# rt1060.net
KiCad netlist of a schematic drawn in EAGLE
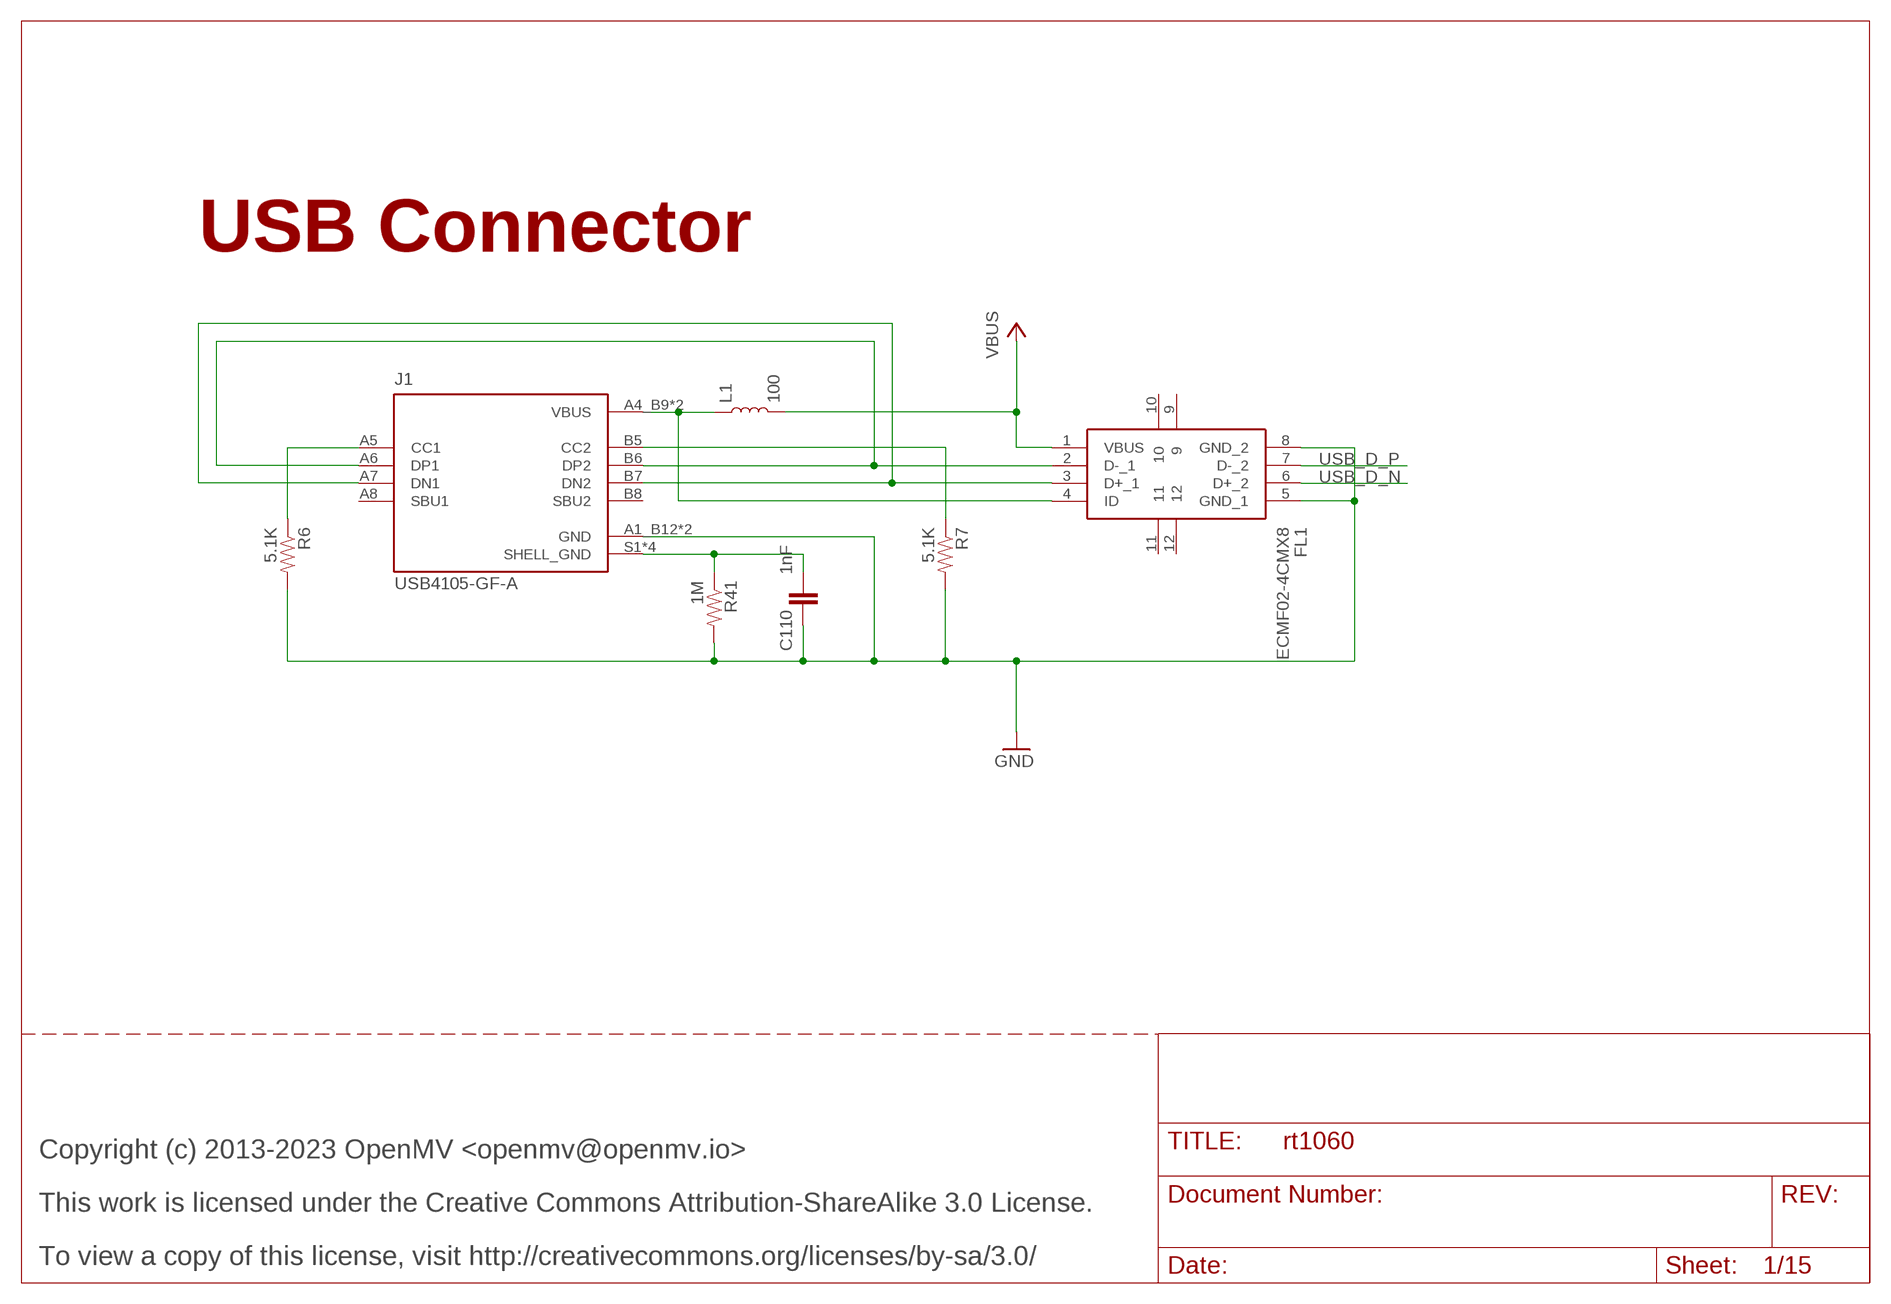
[diagram p0: schematic, sheet 1]
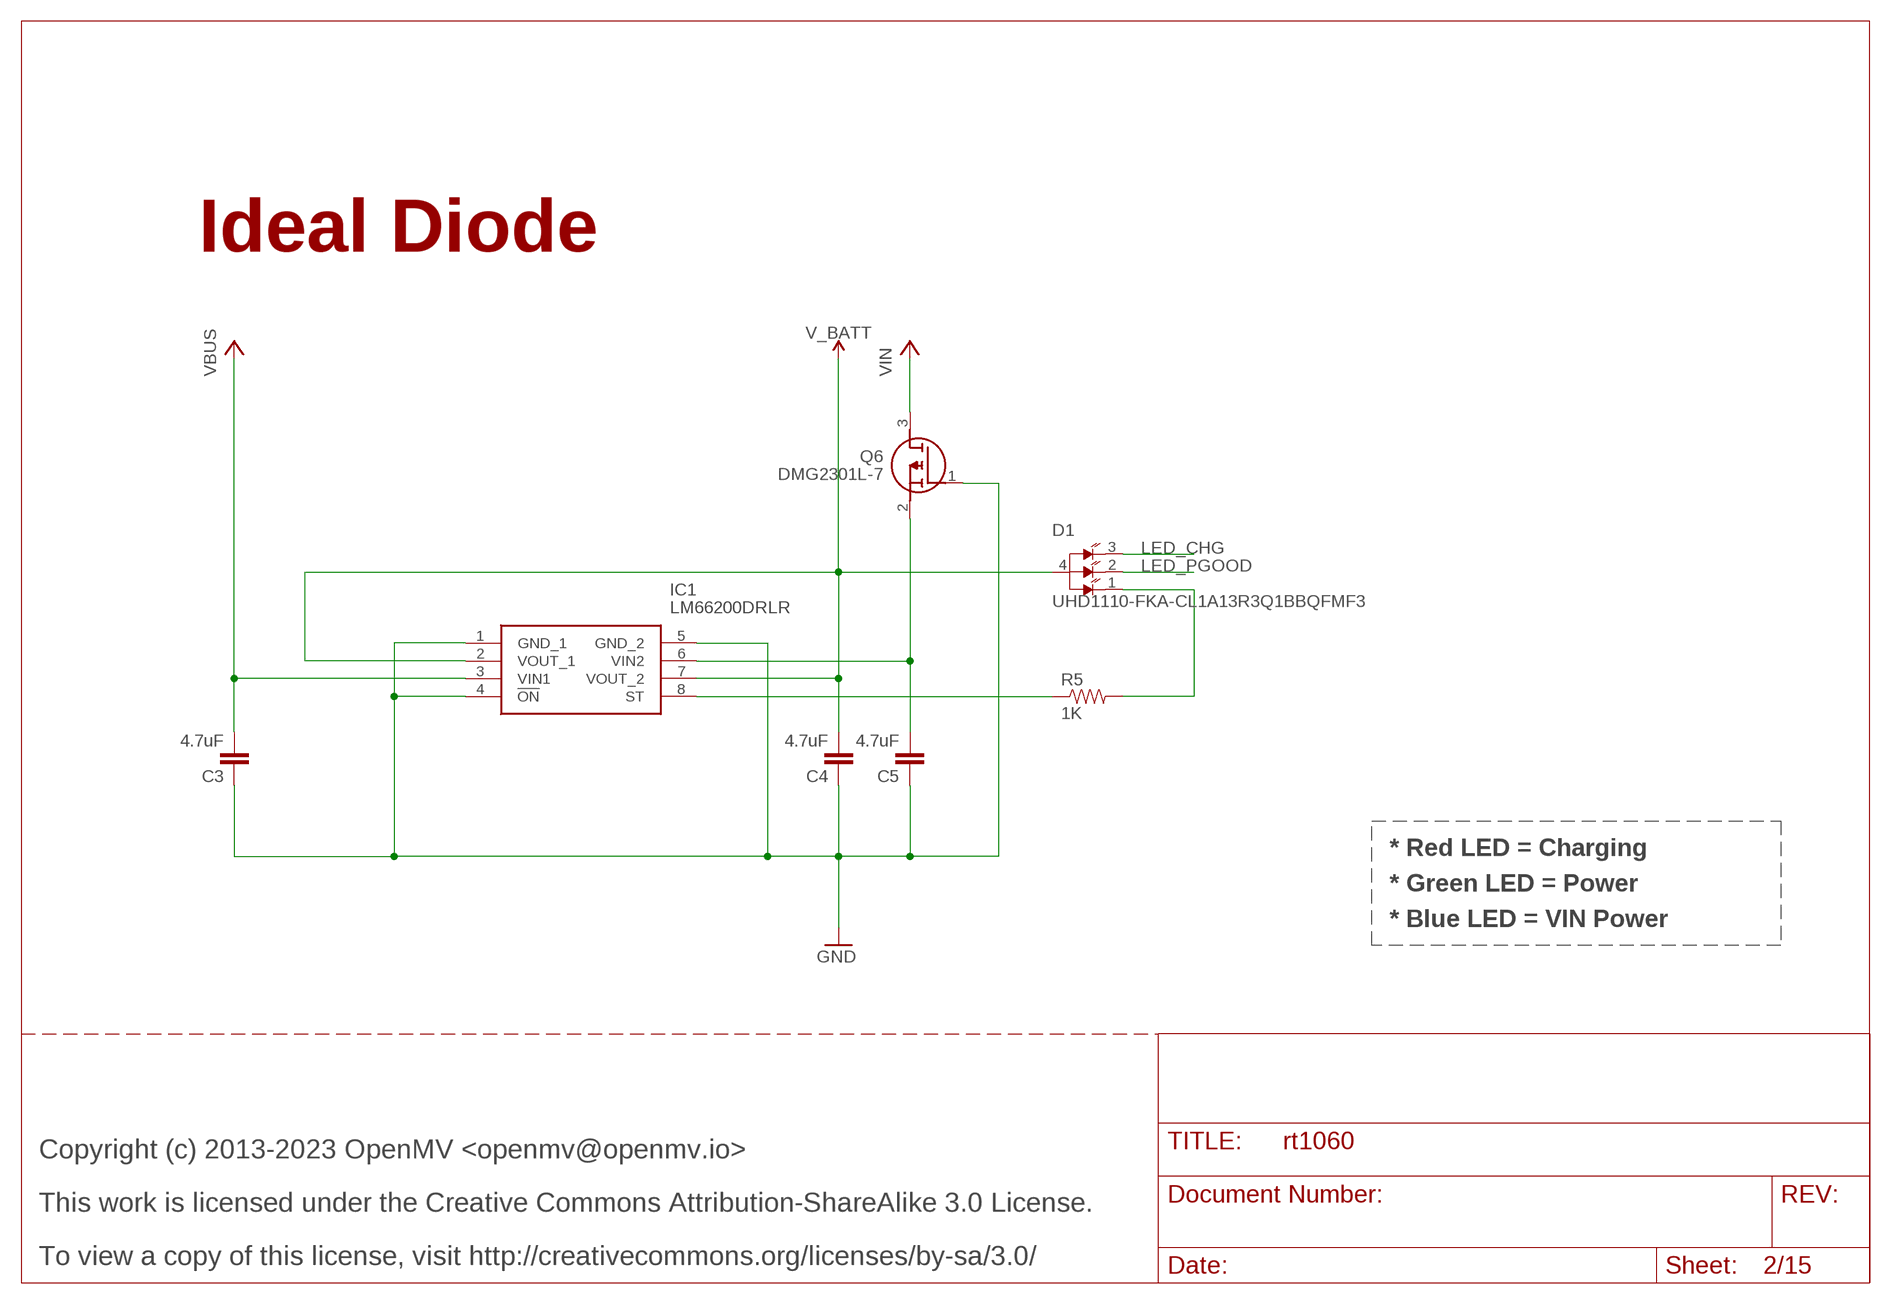
[diagram p1: schematic, sheet 2]
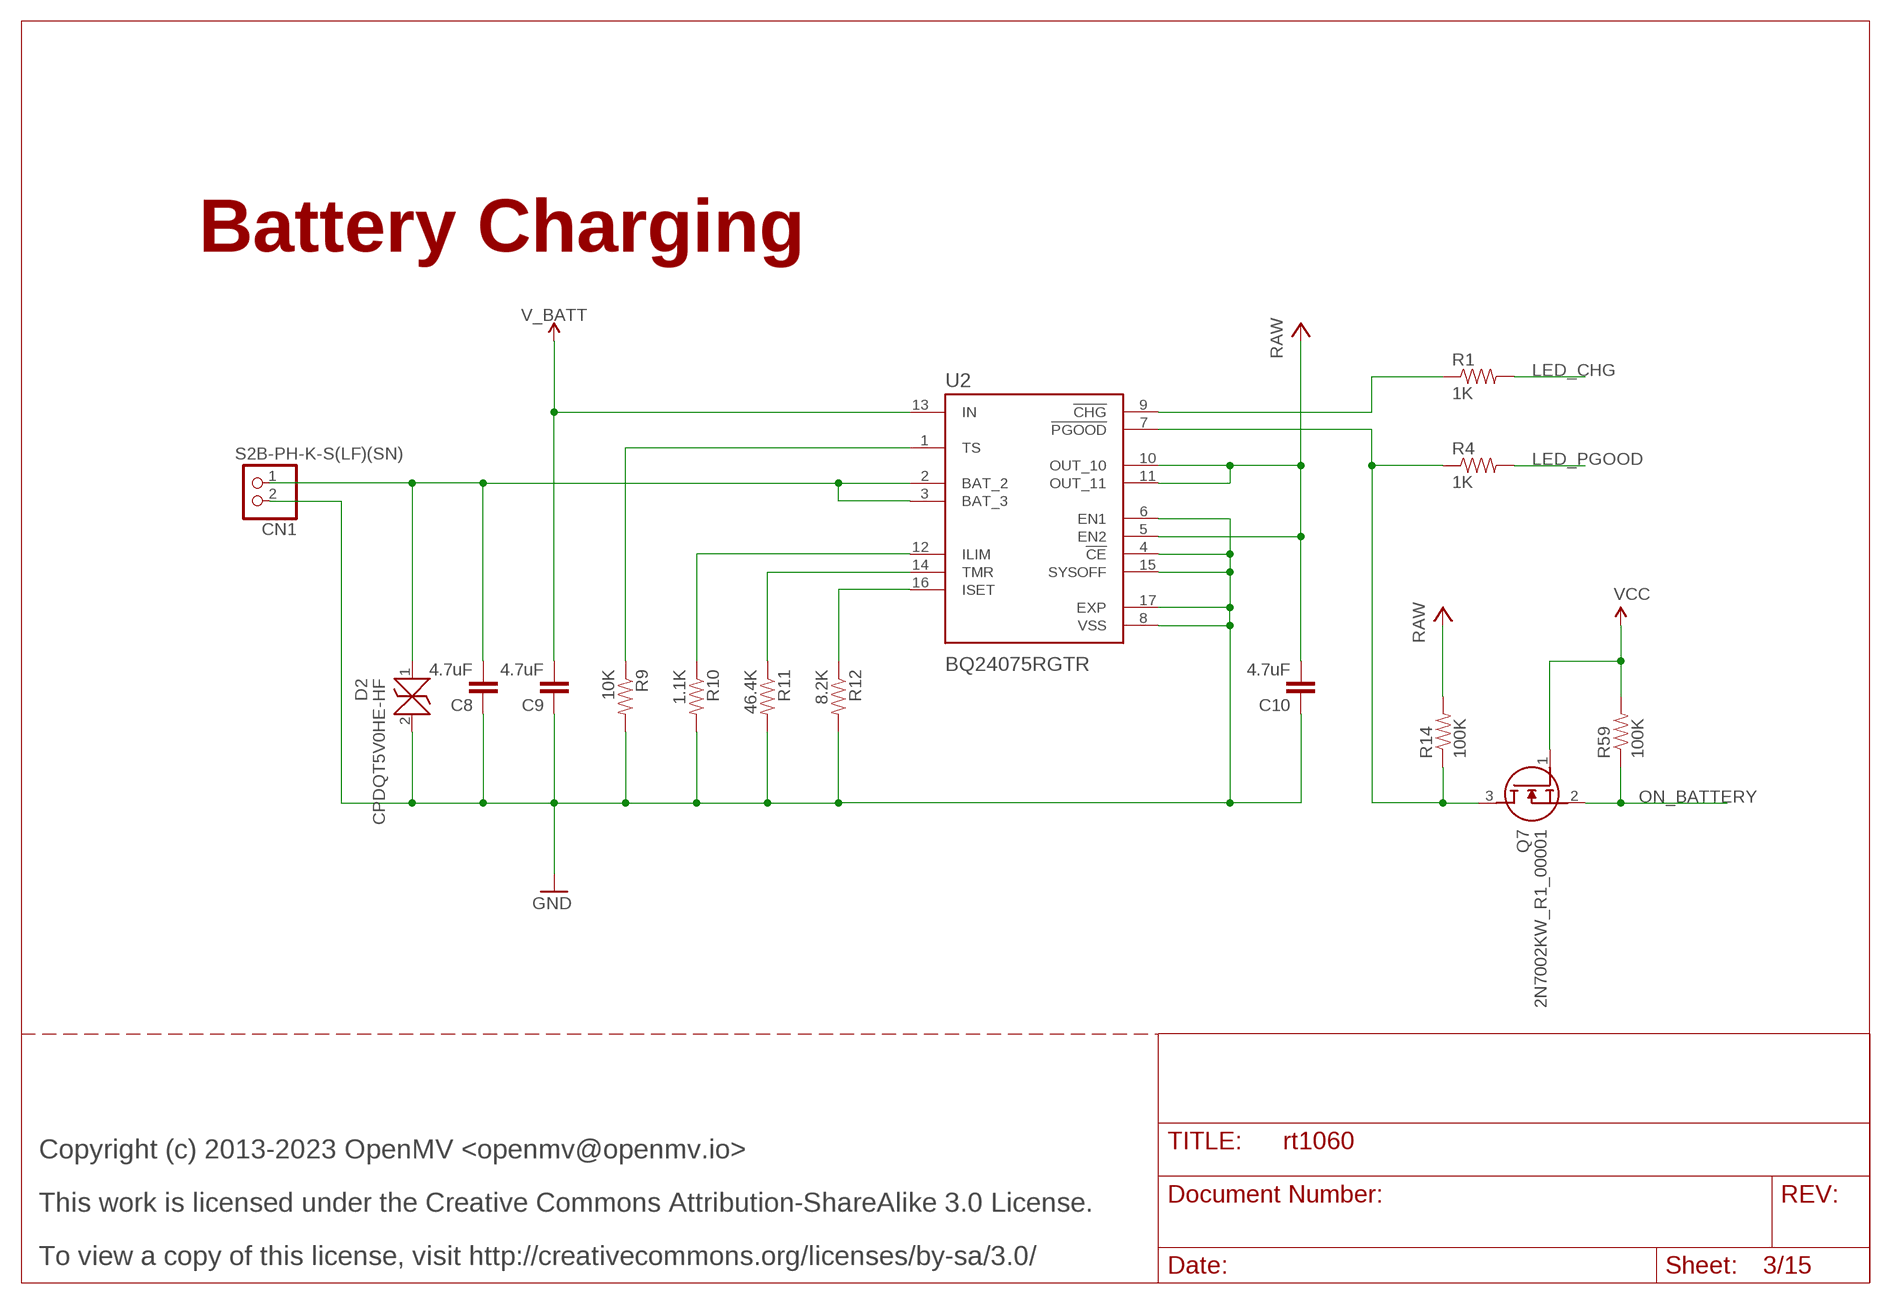
[diagram p2: schematic, sheet 3]
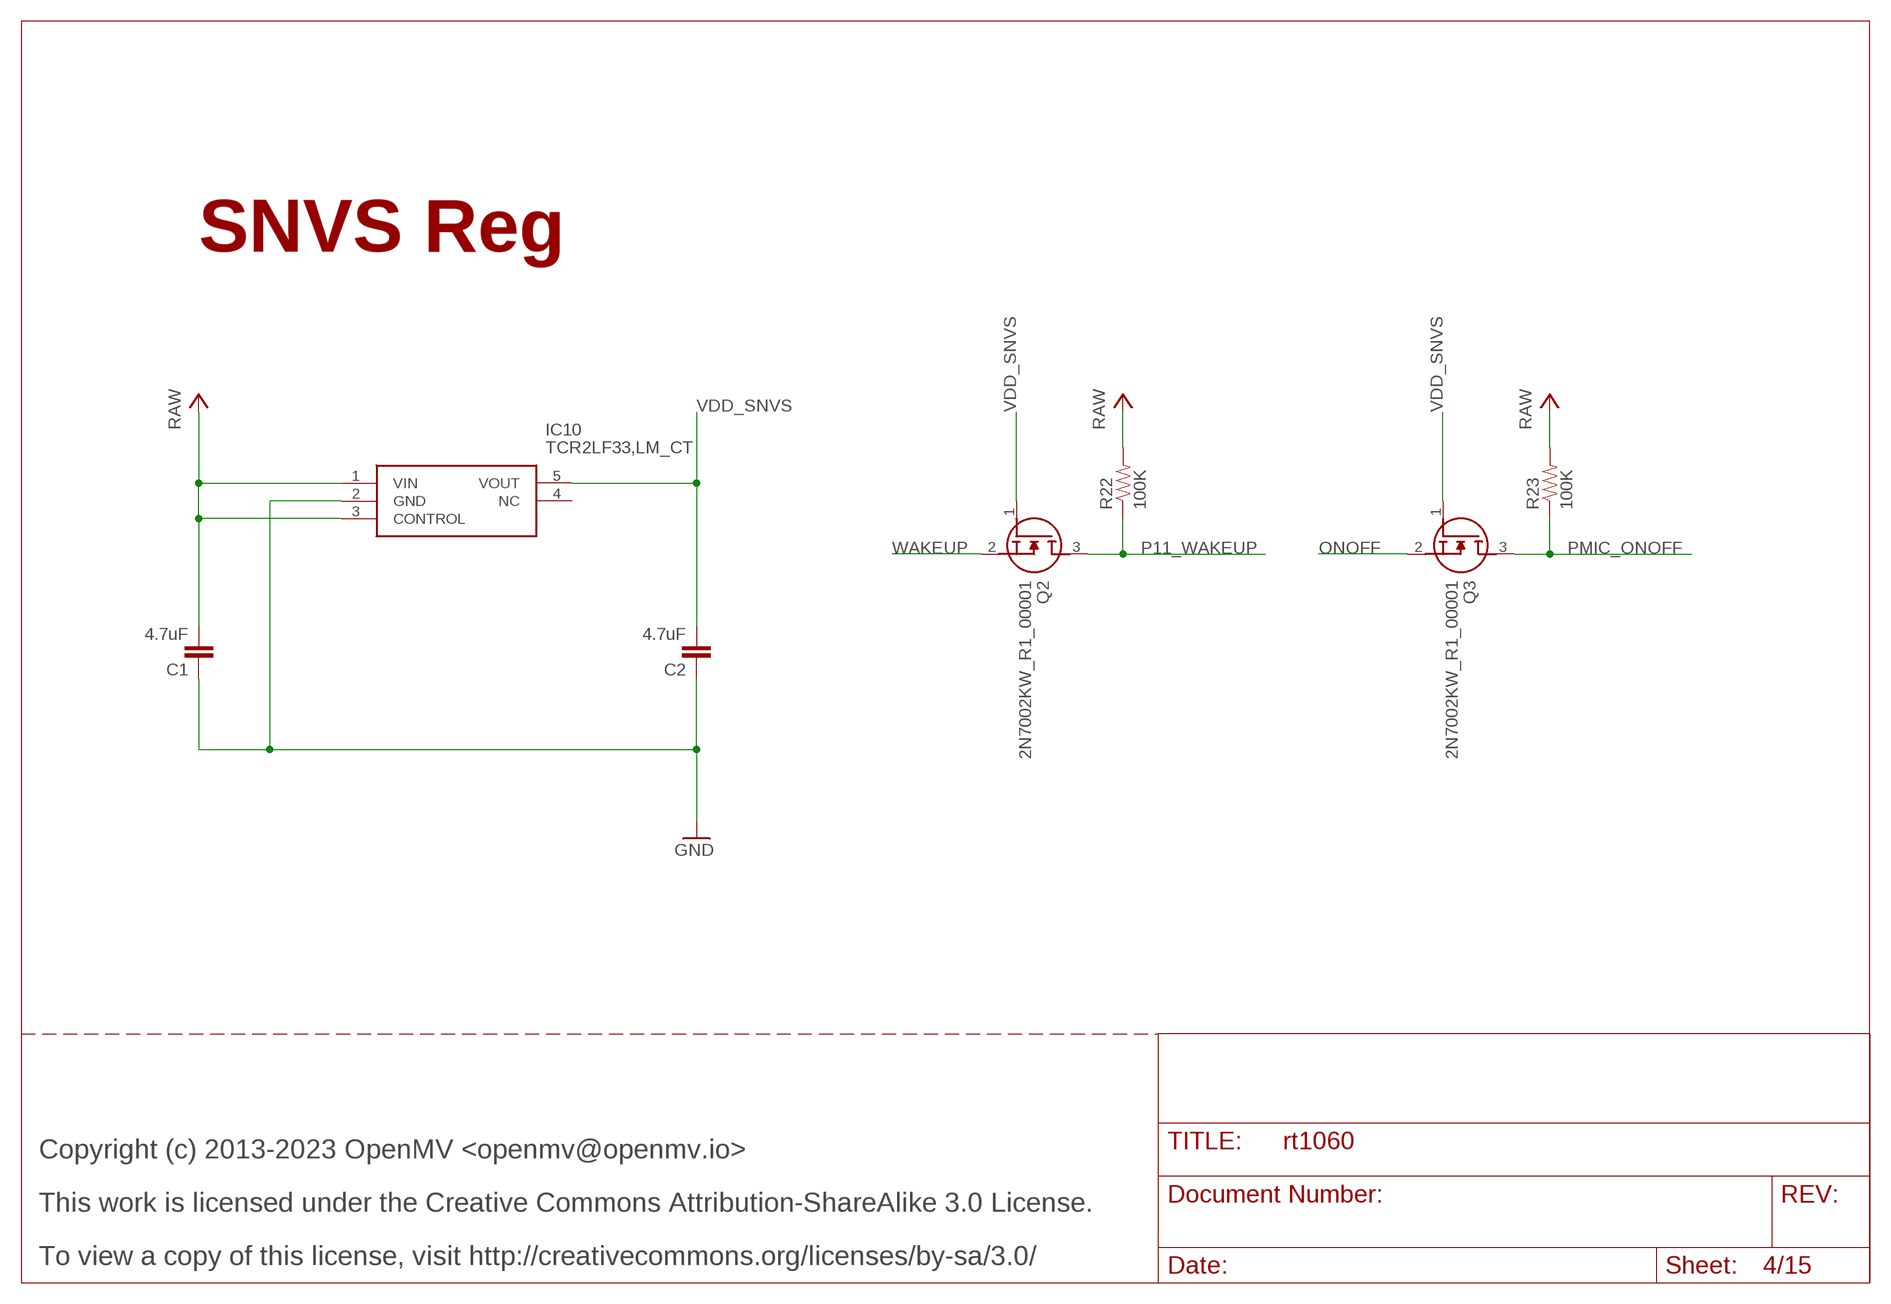
[diagram p3: schematic, sheet 4]
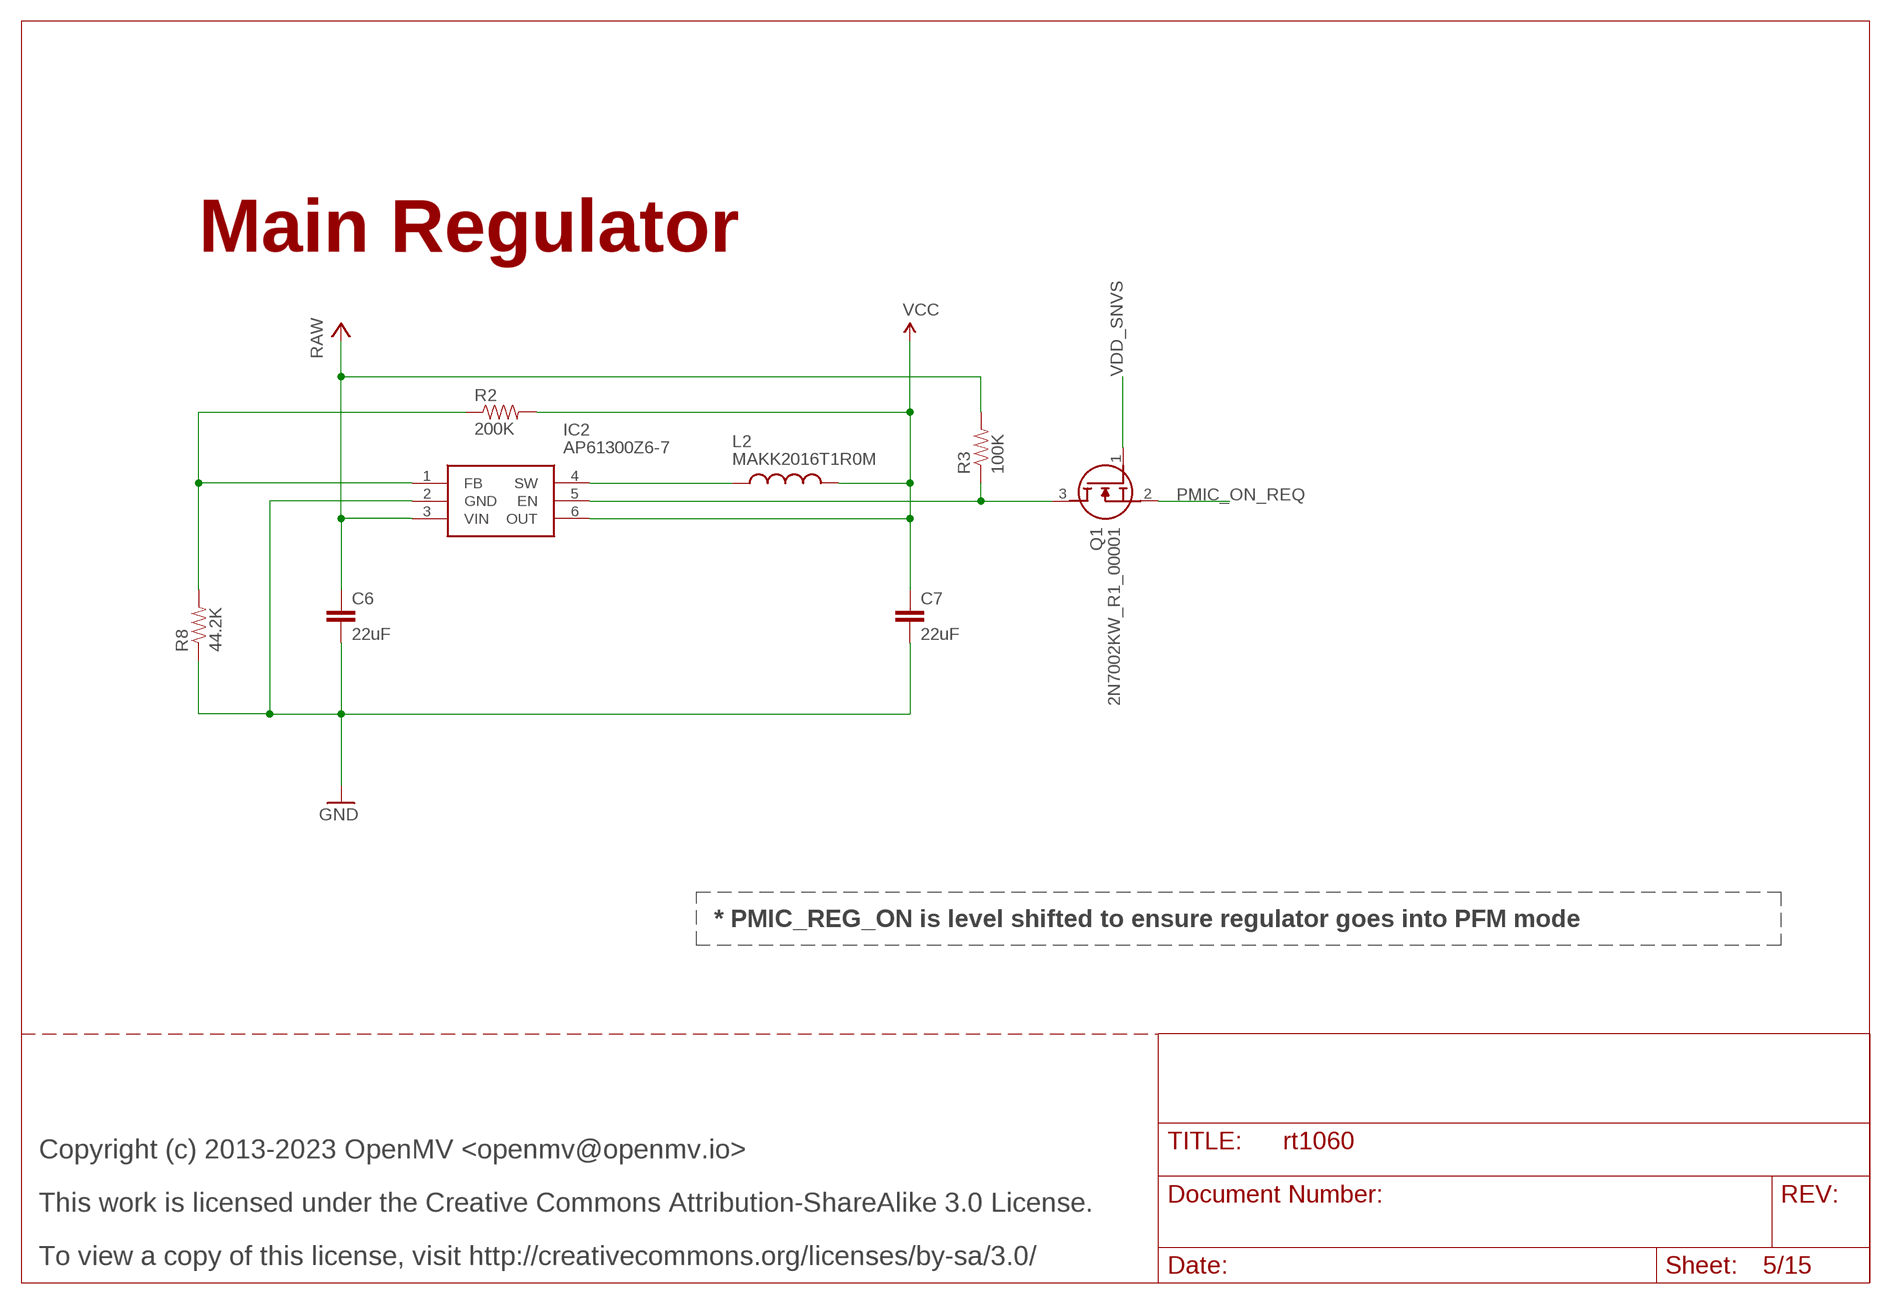
[diagram p4: schematic, sheet 5]
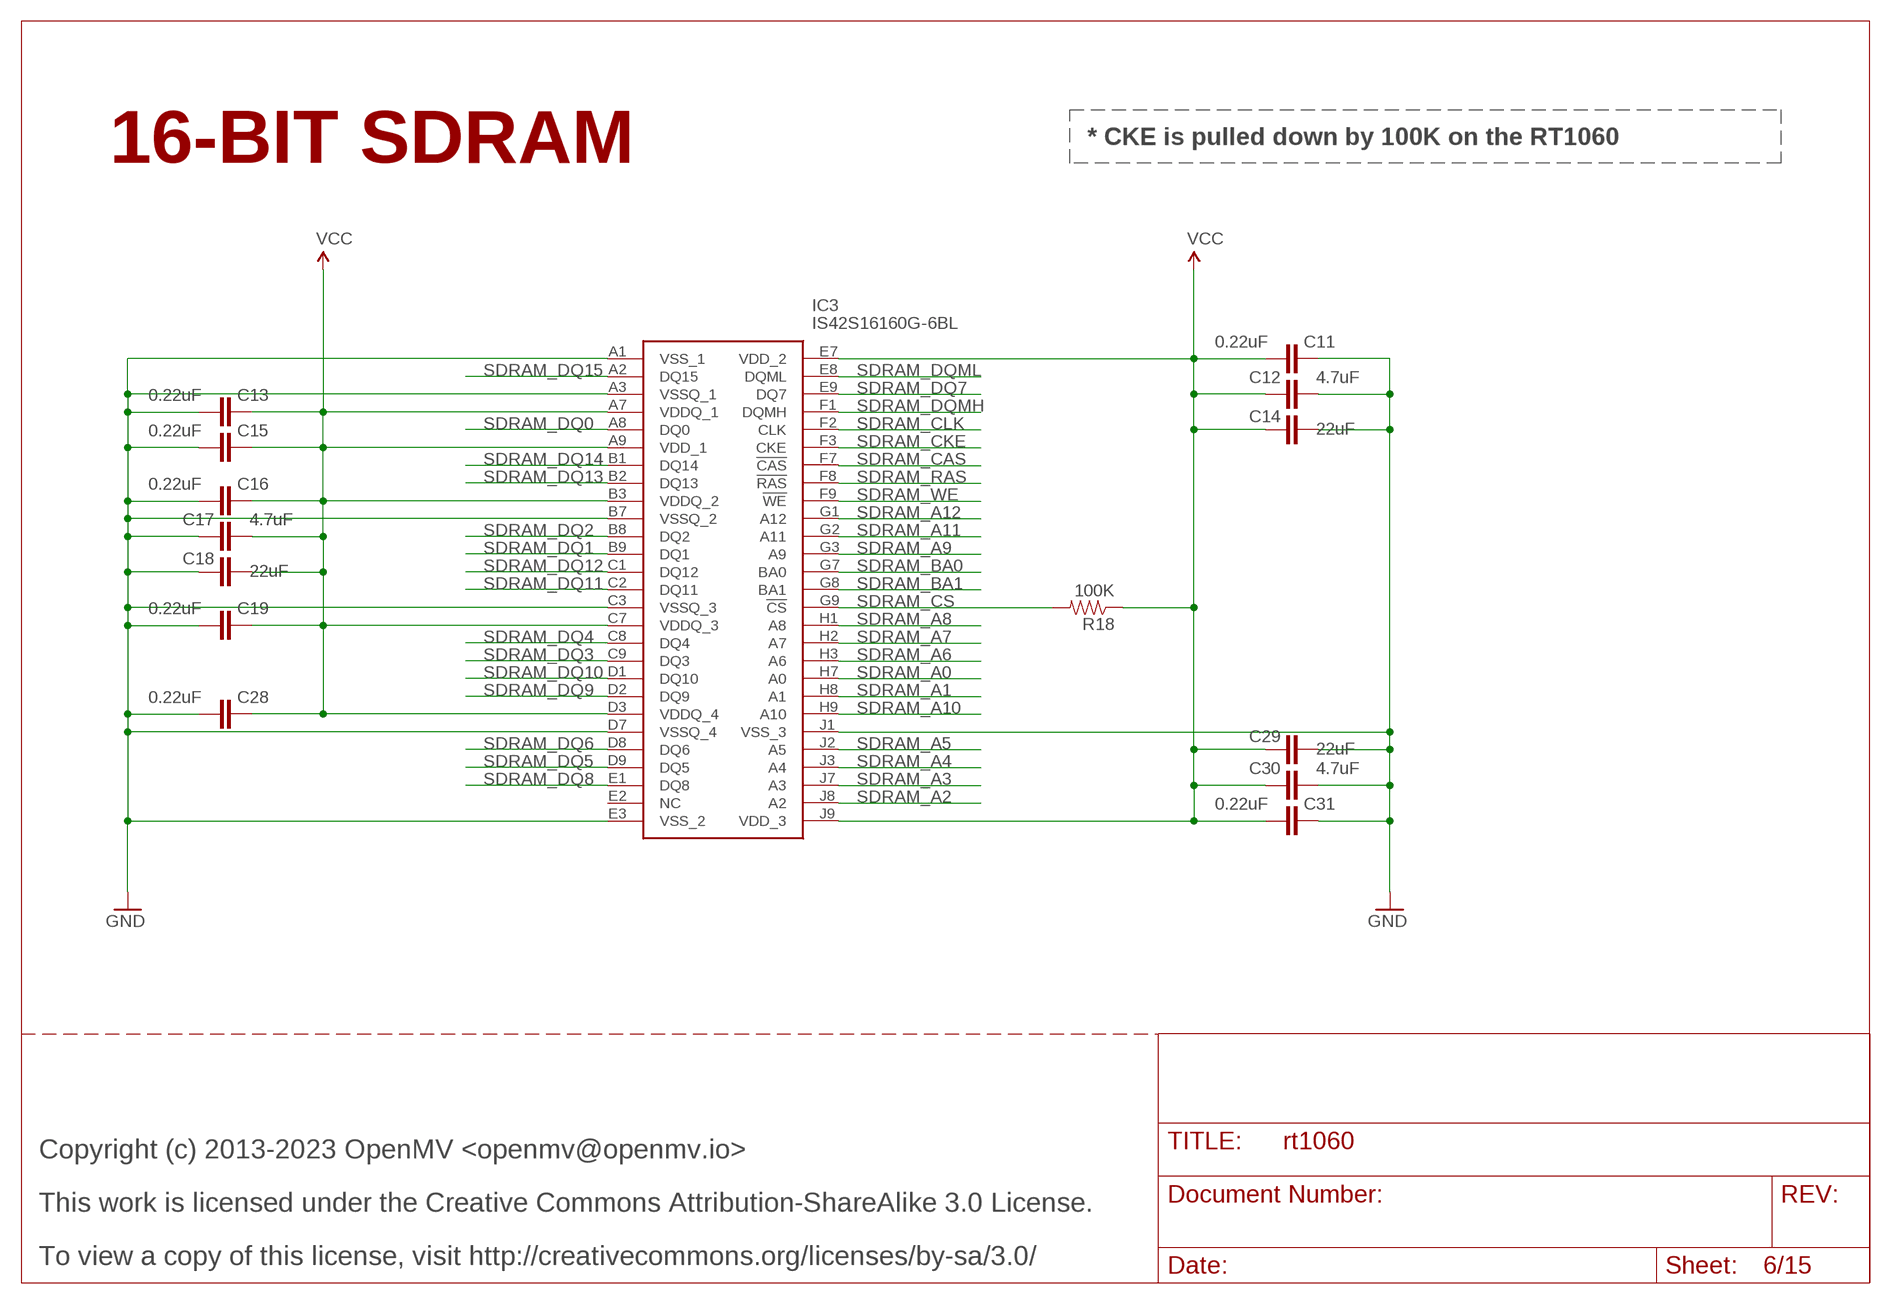
[diagram p5: schematic, sheet 6]
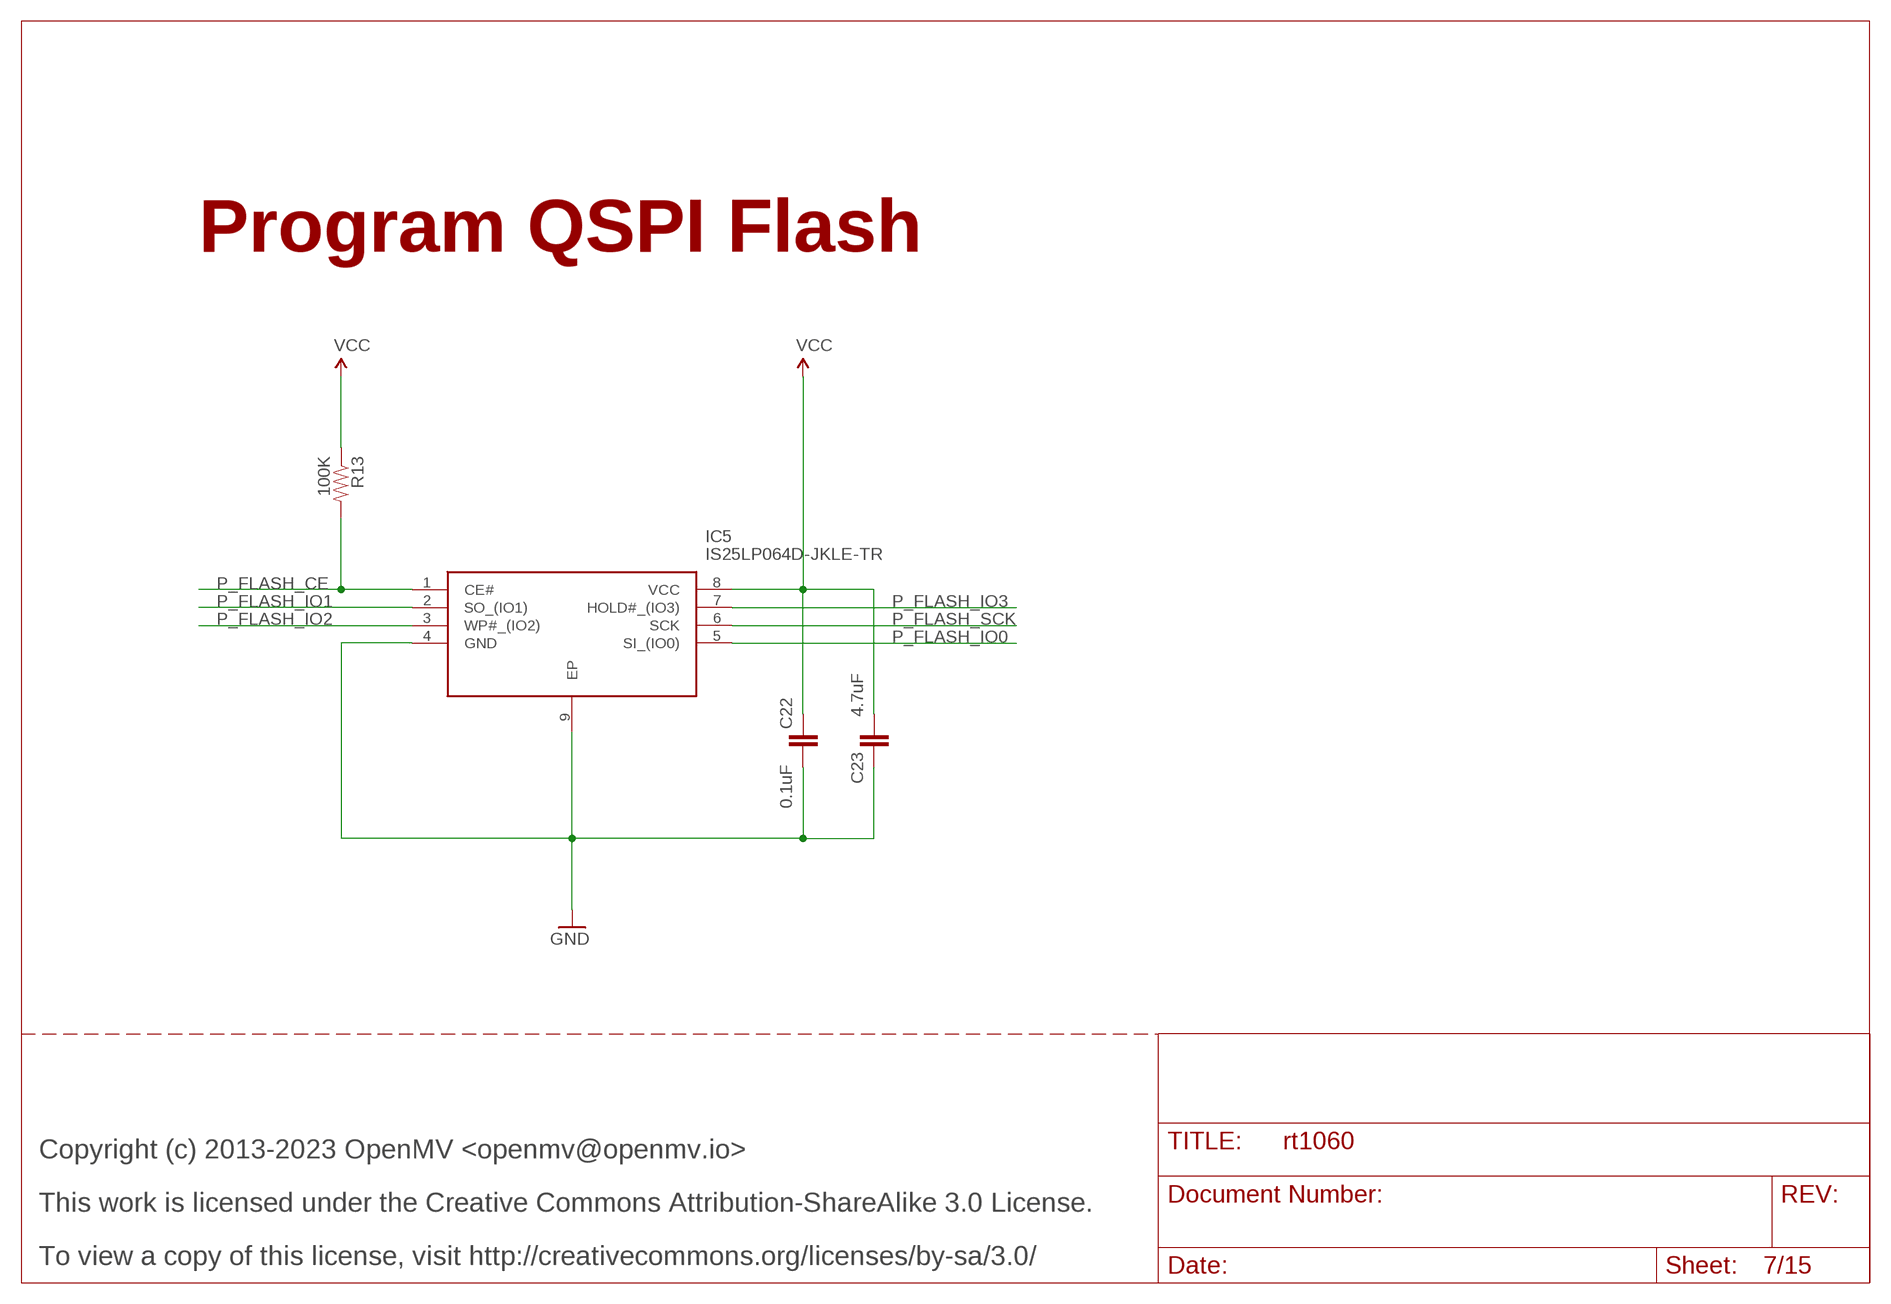
[diagram p6: schematic, sheet 7]
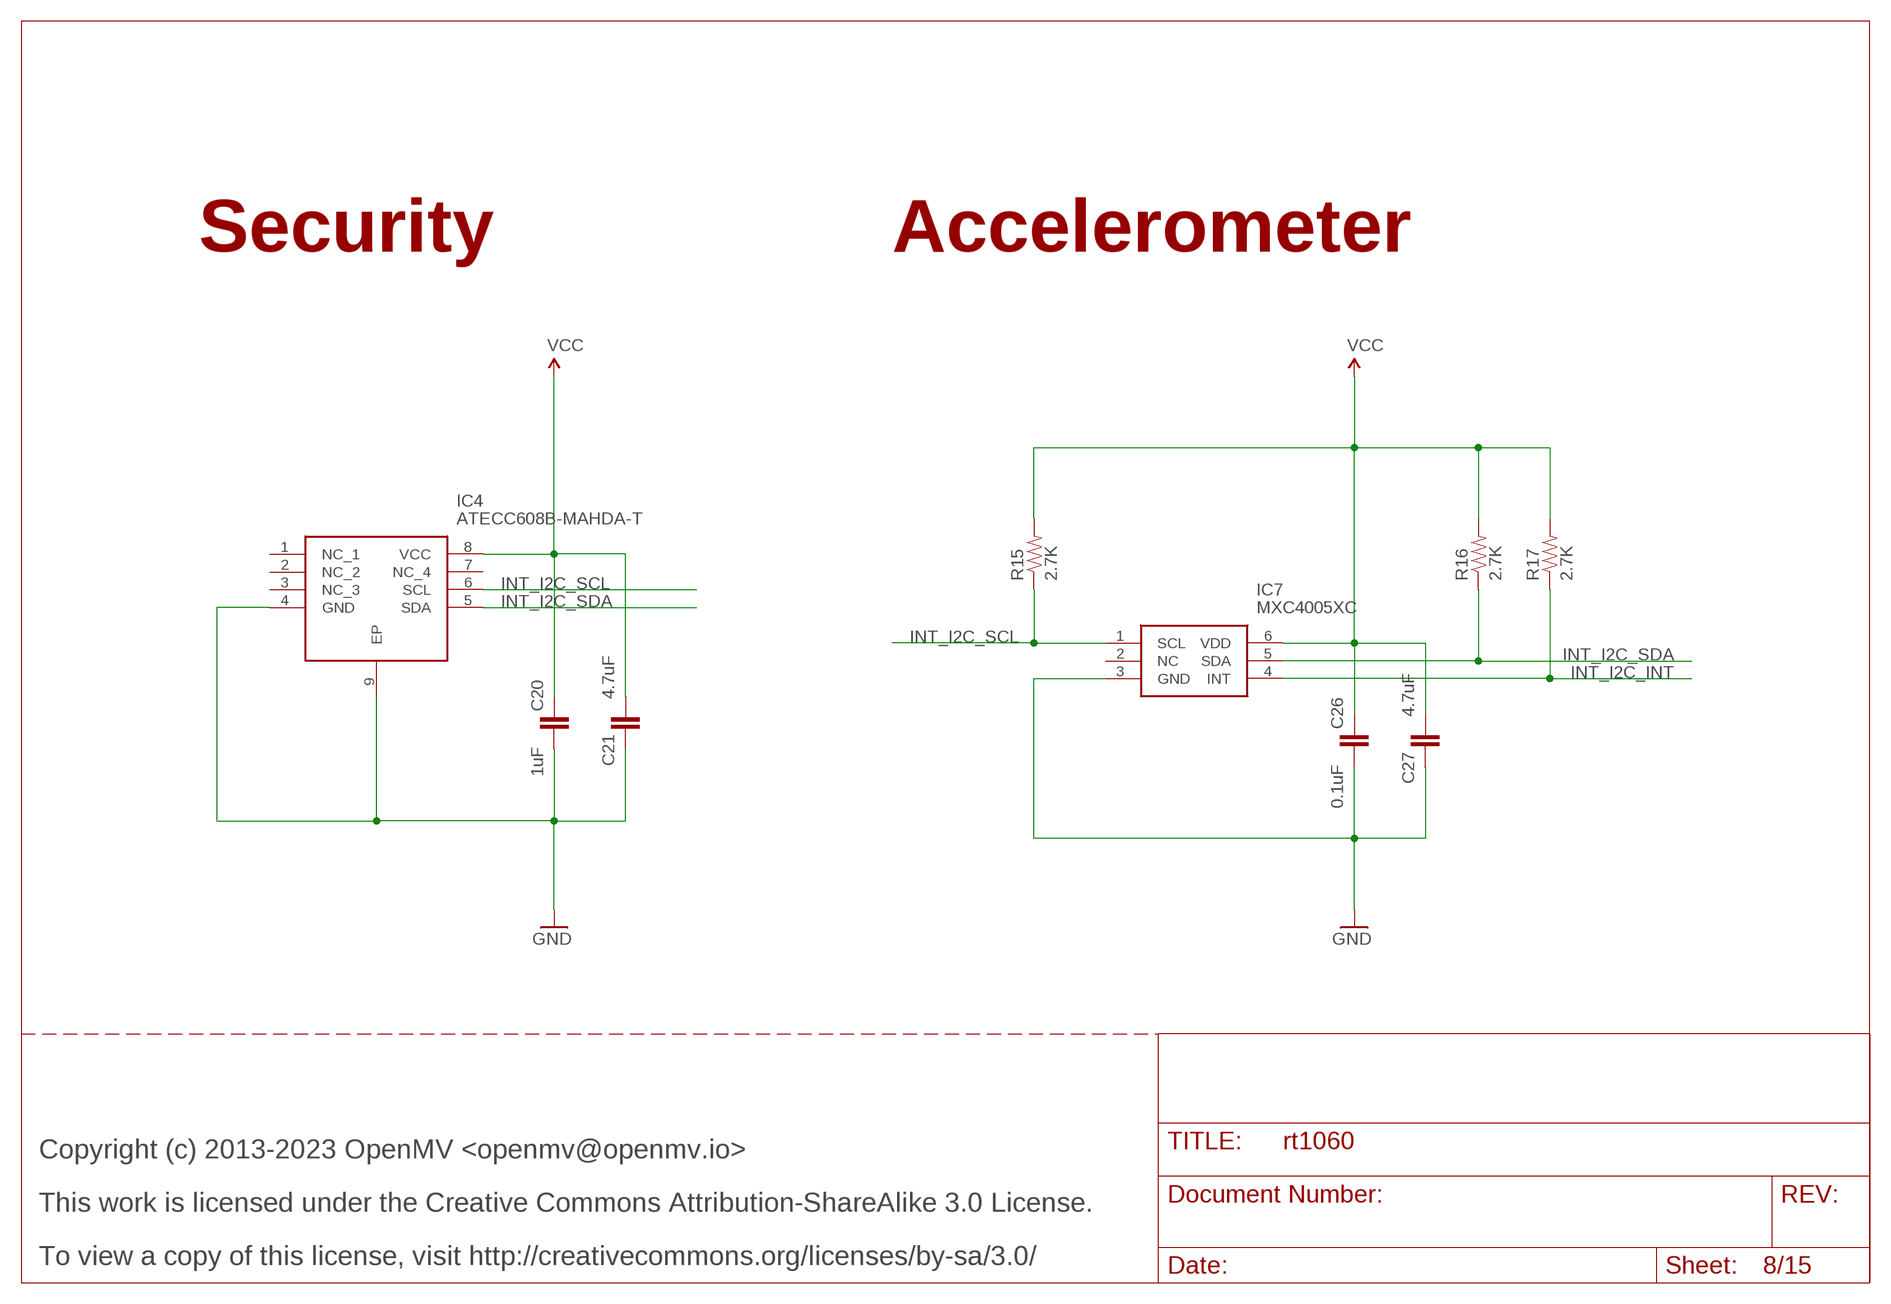
[diagram p7: schematic, sheet 8]
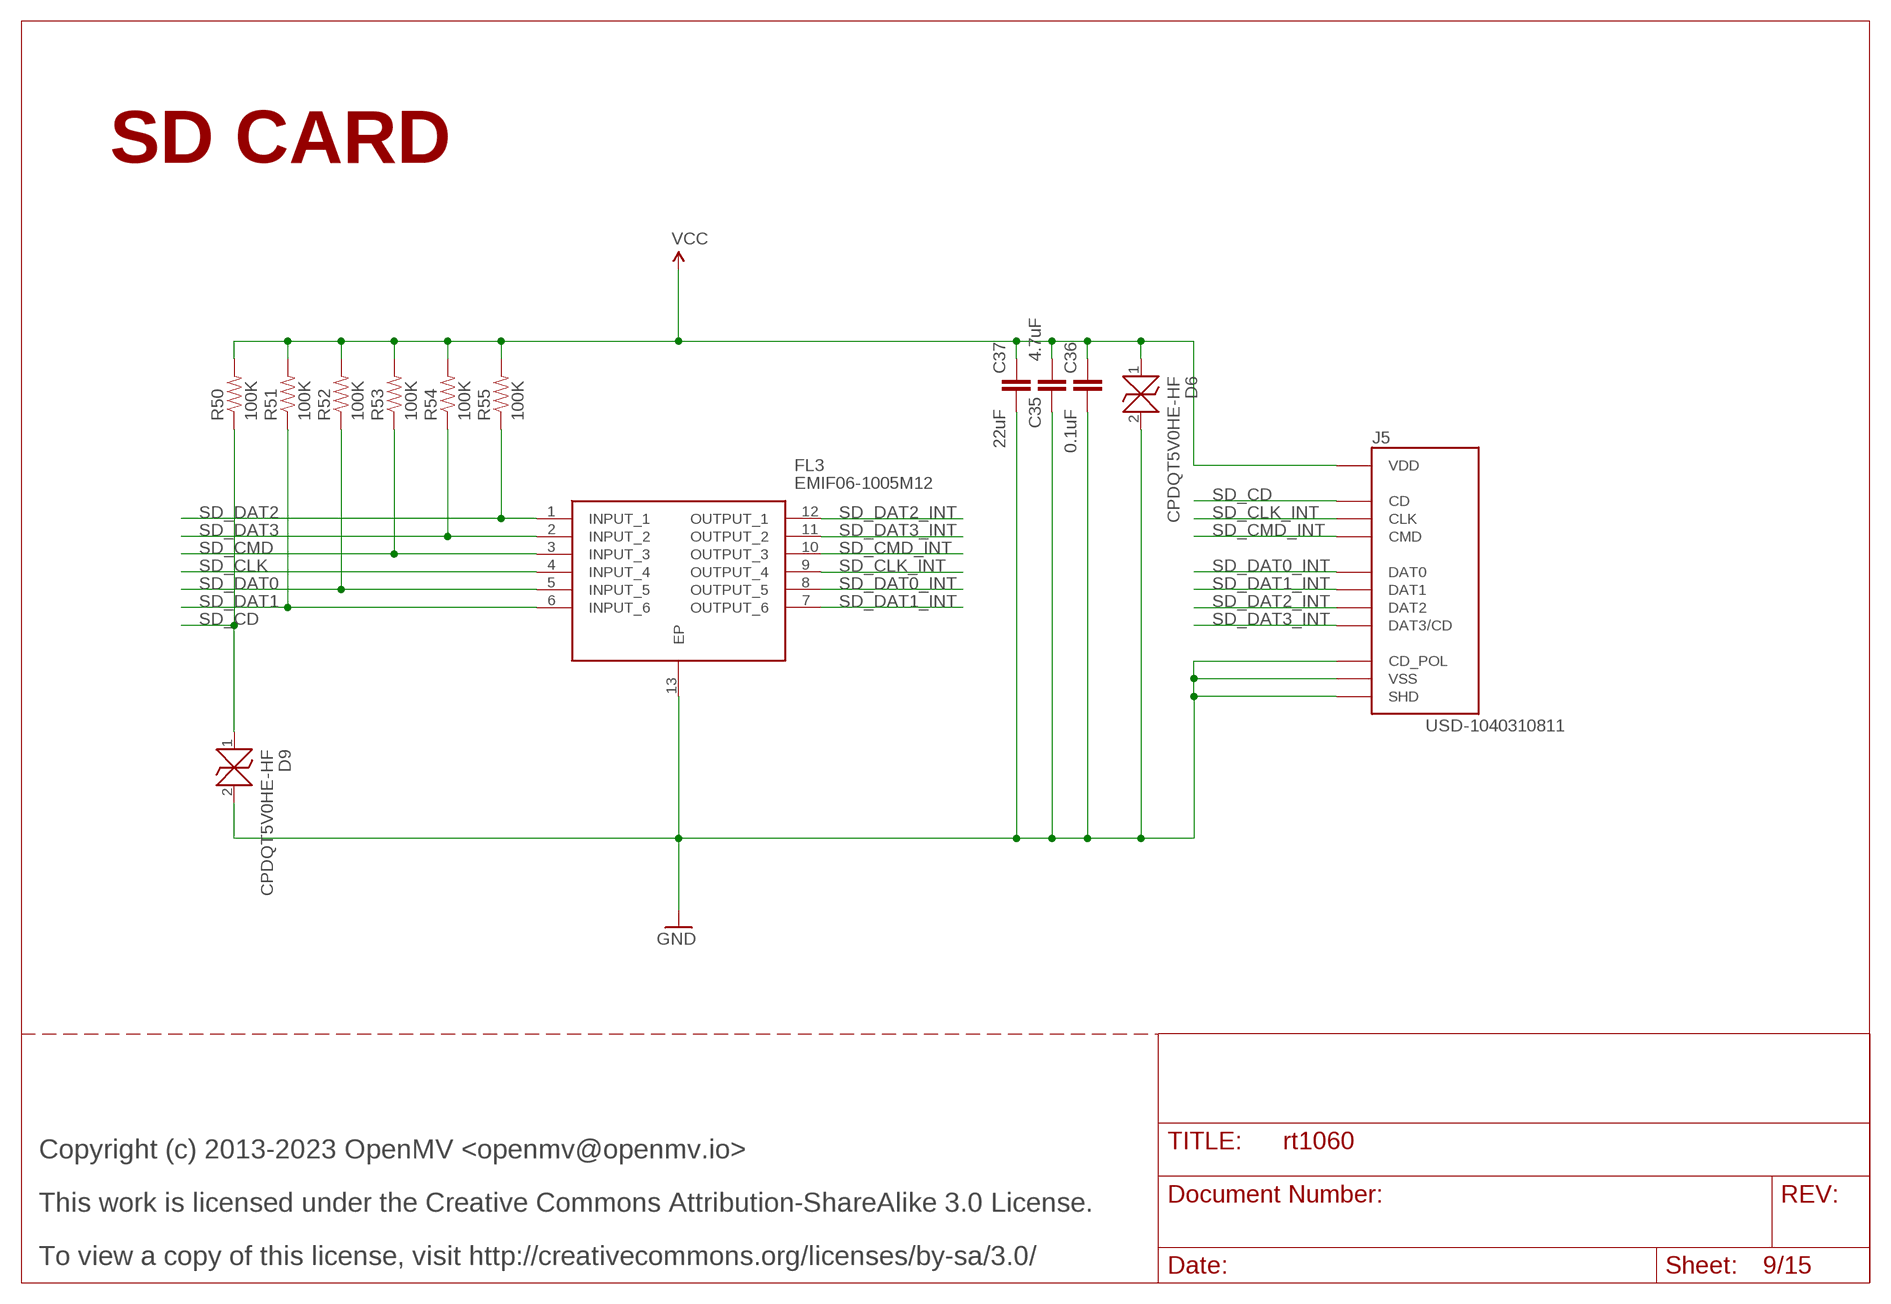
[diagram p8: schematic, sheet 9]
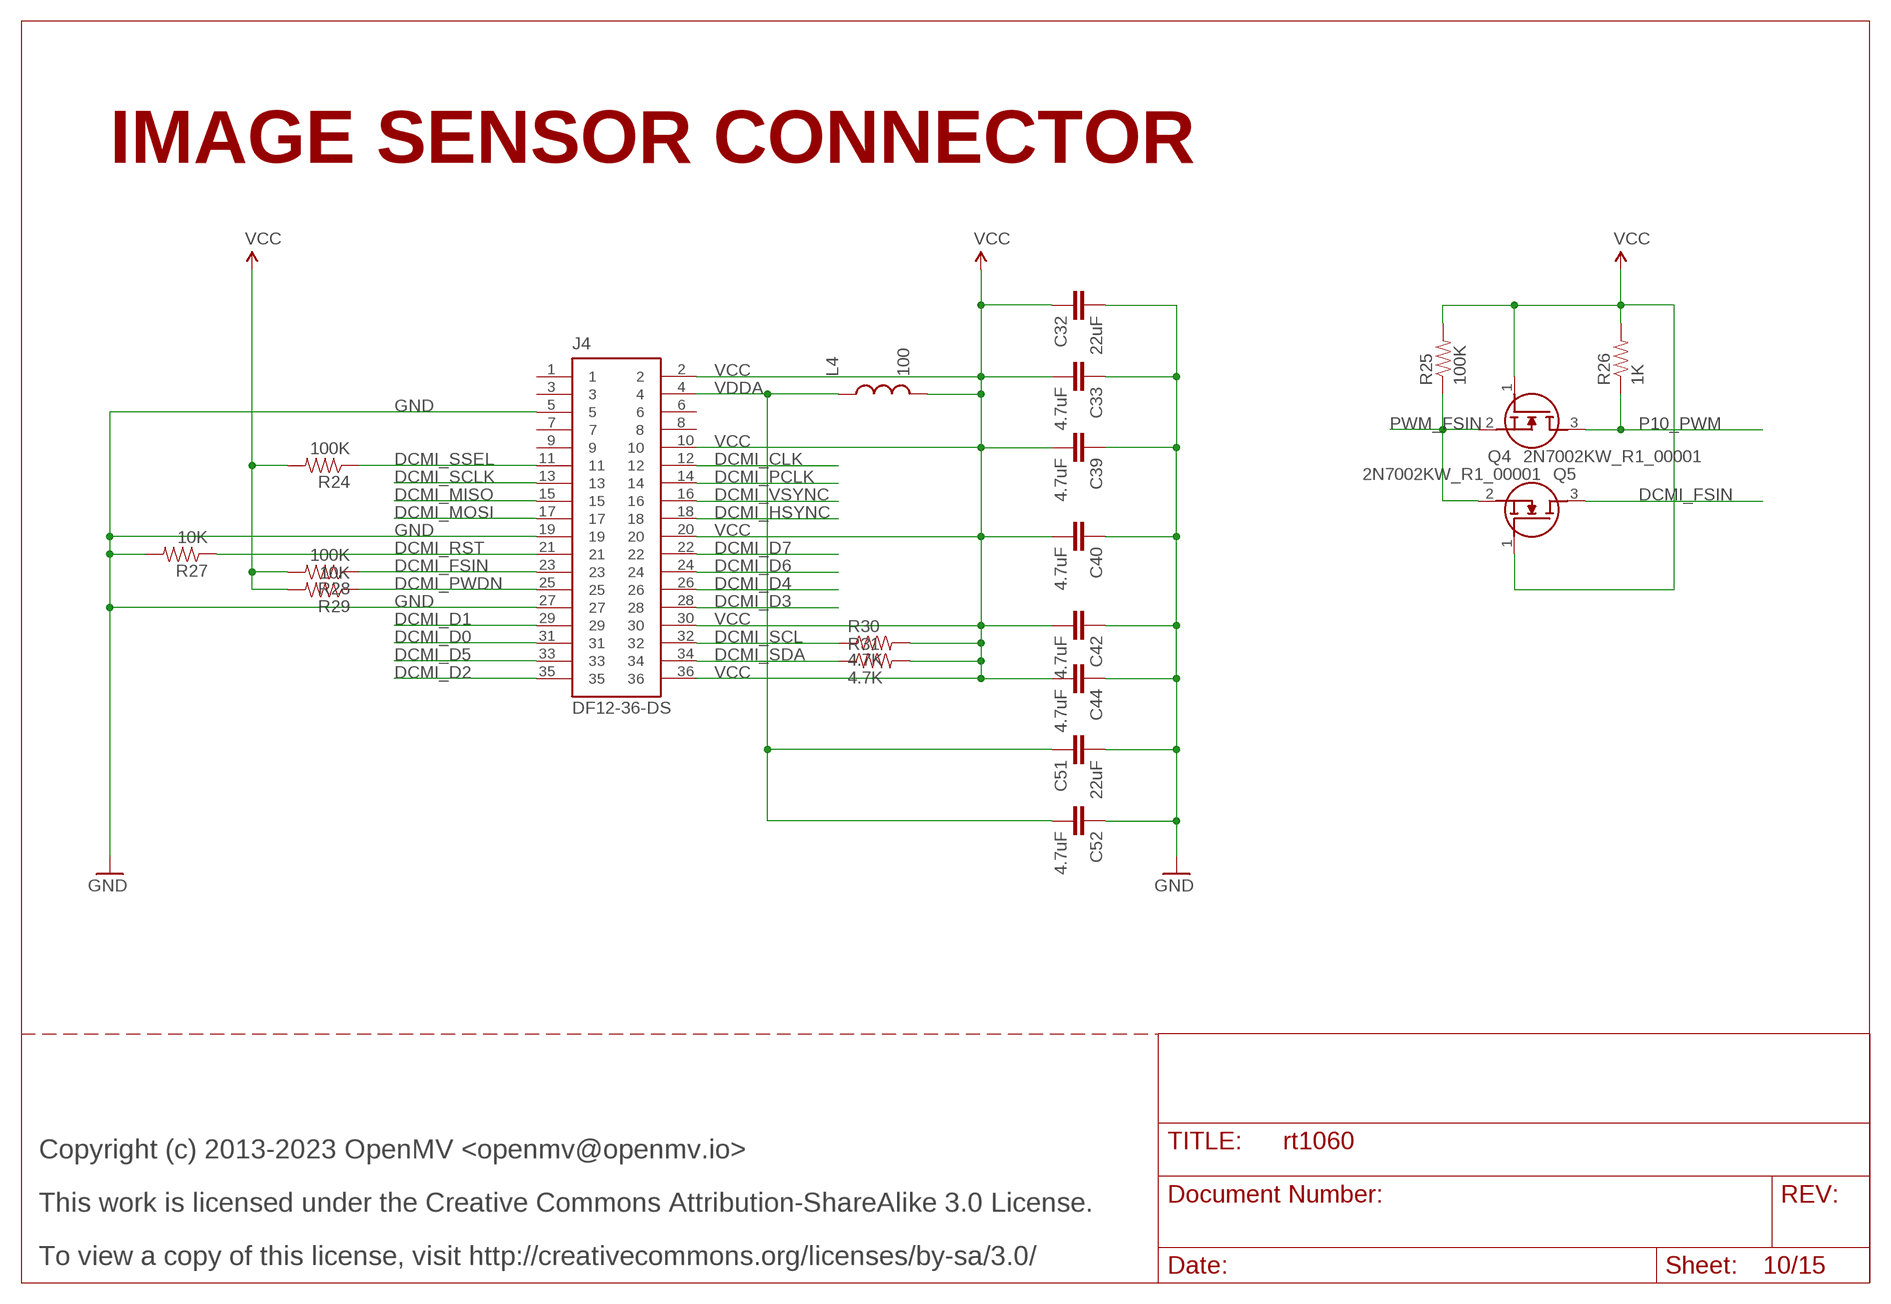
[diagram p9: schematic, sheet 10]
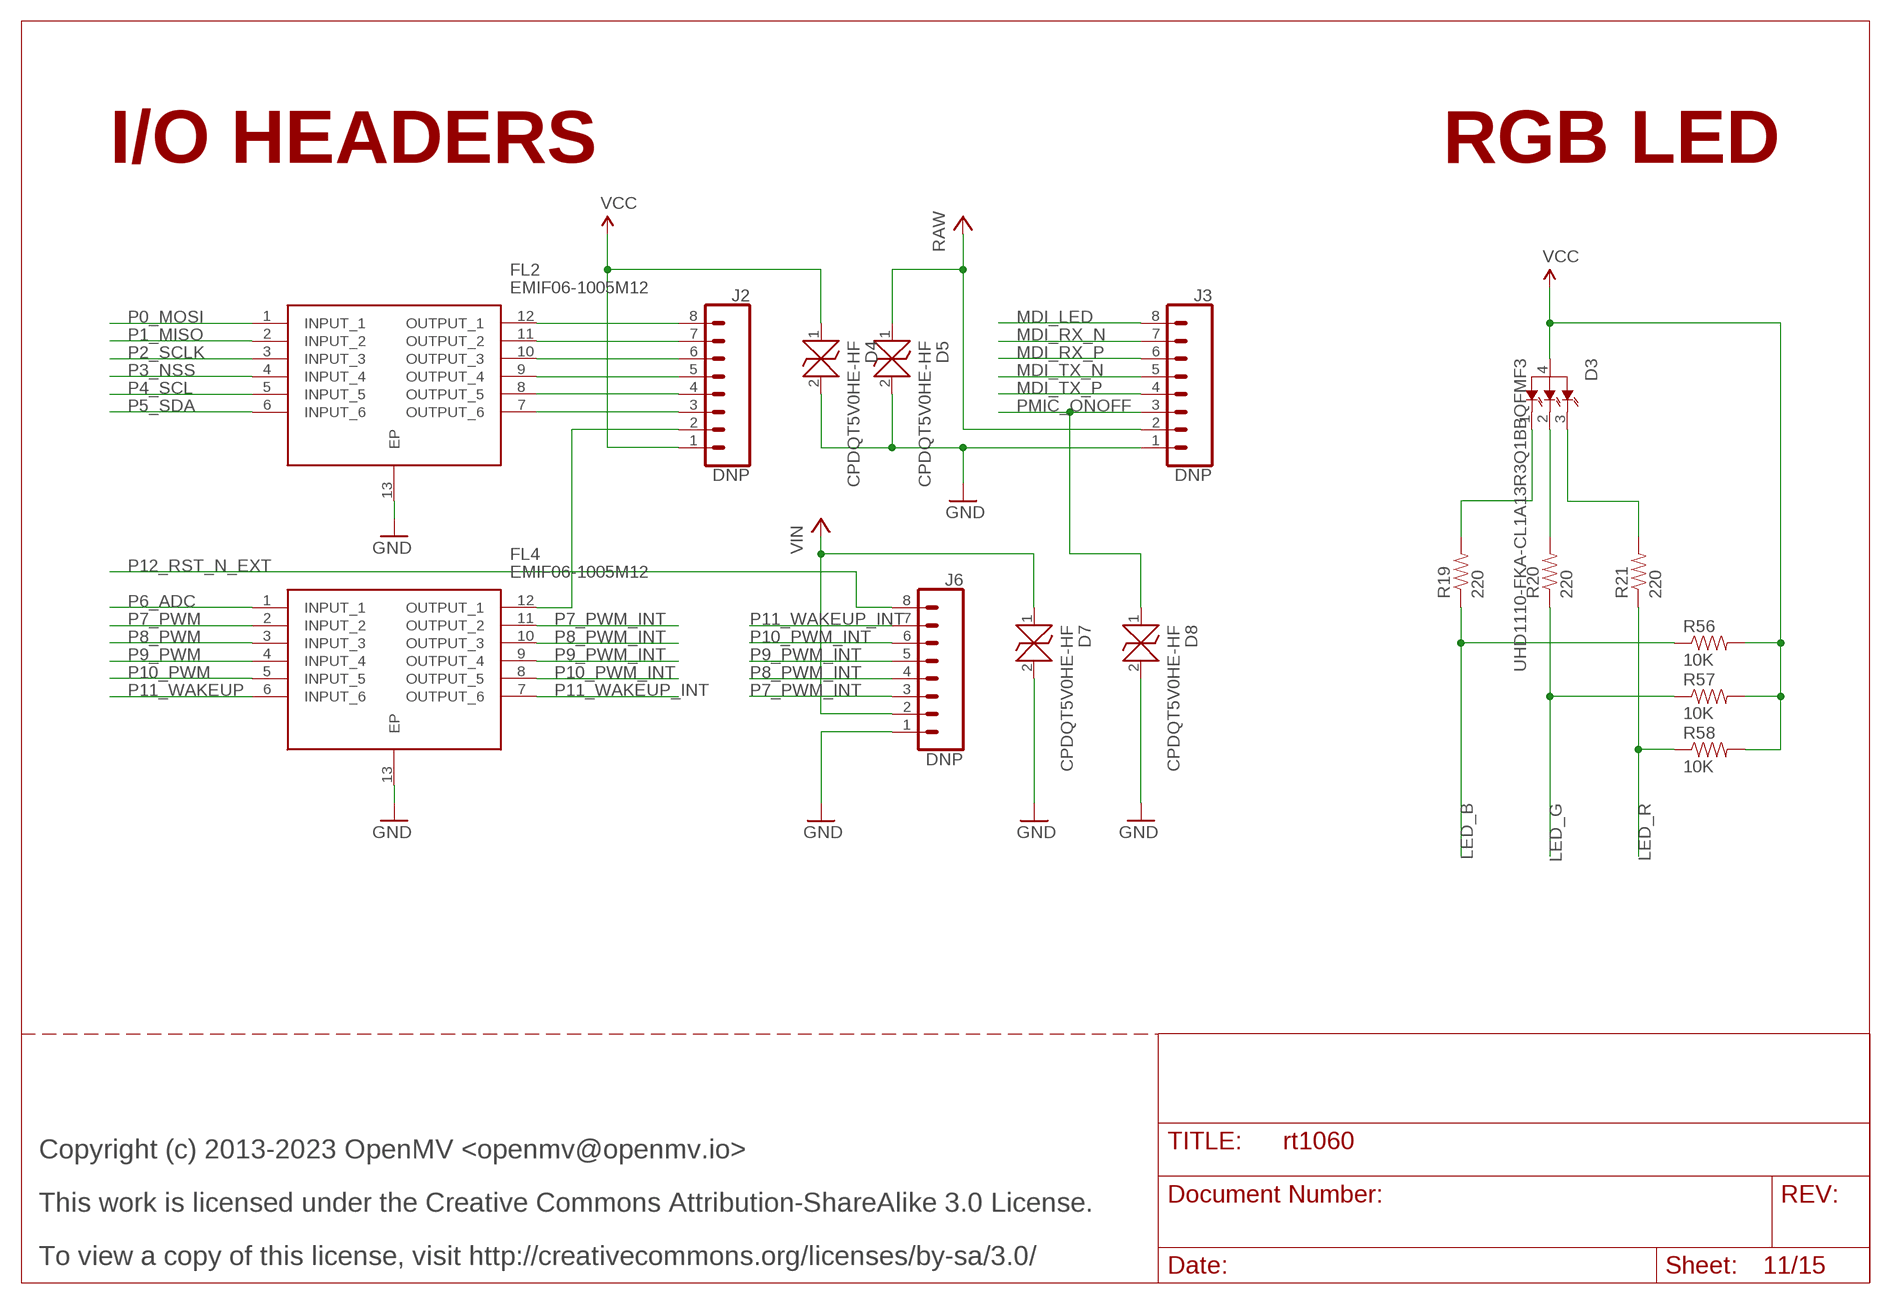
[diagram p10: schematic, sheet 11]
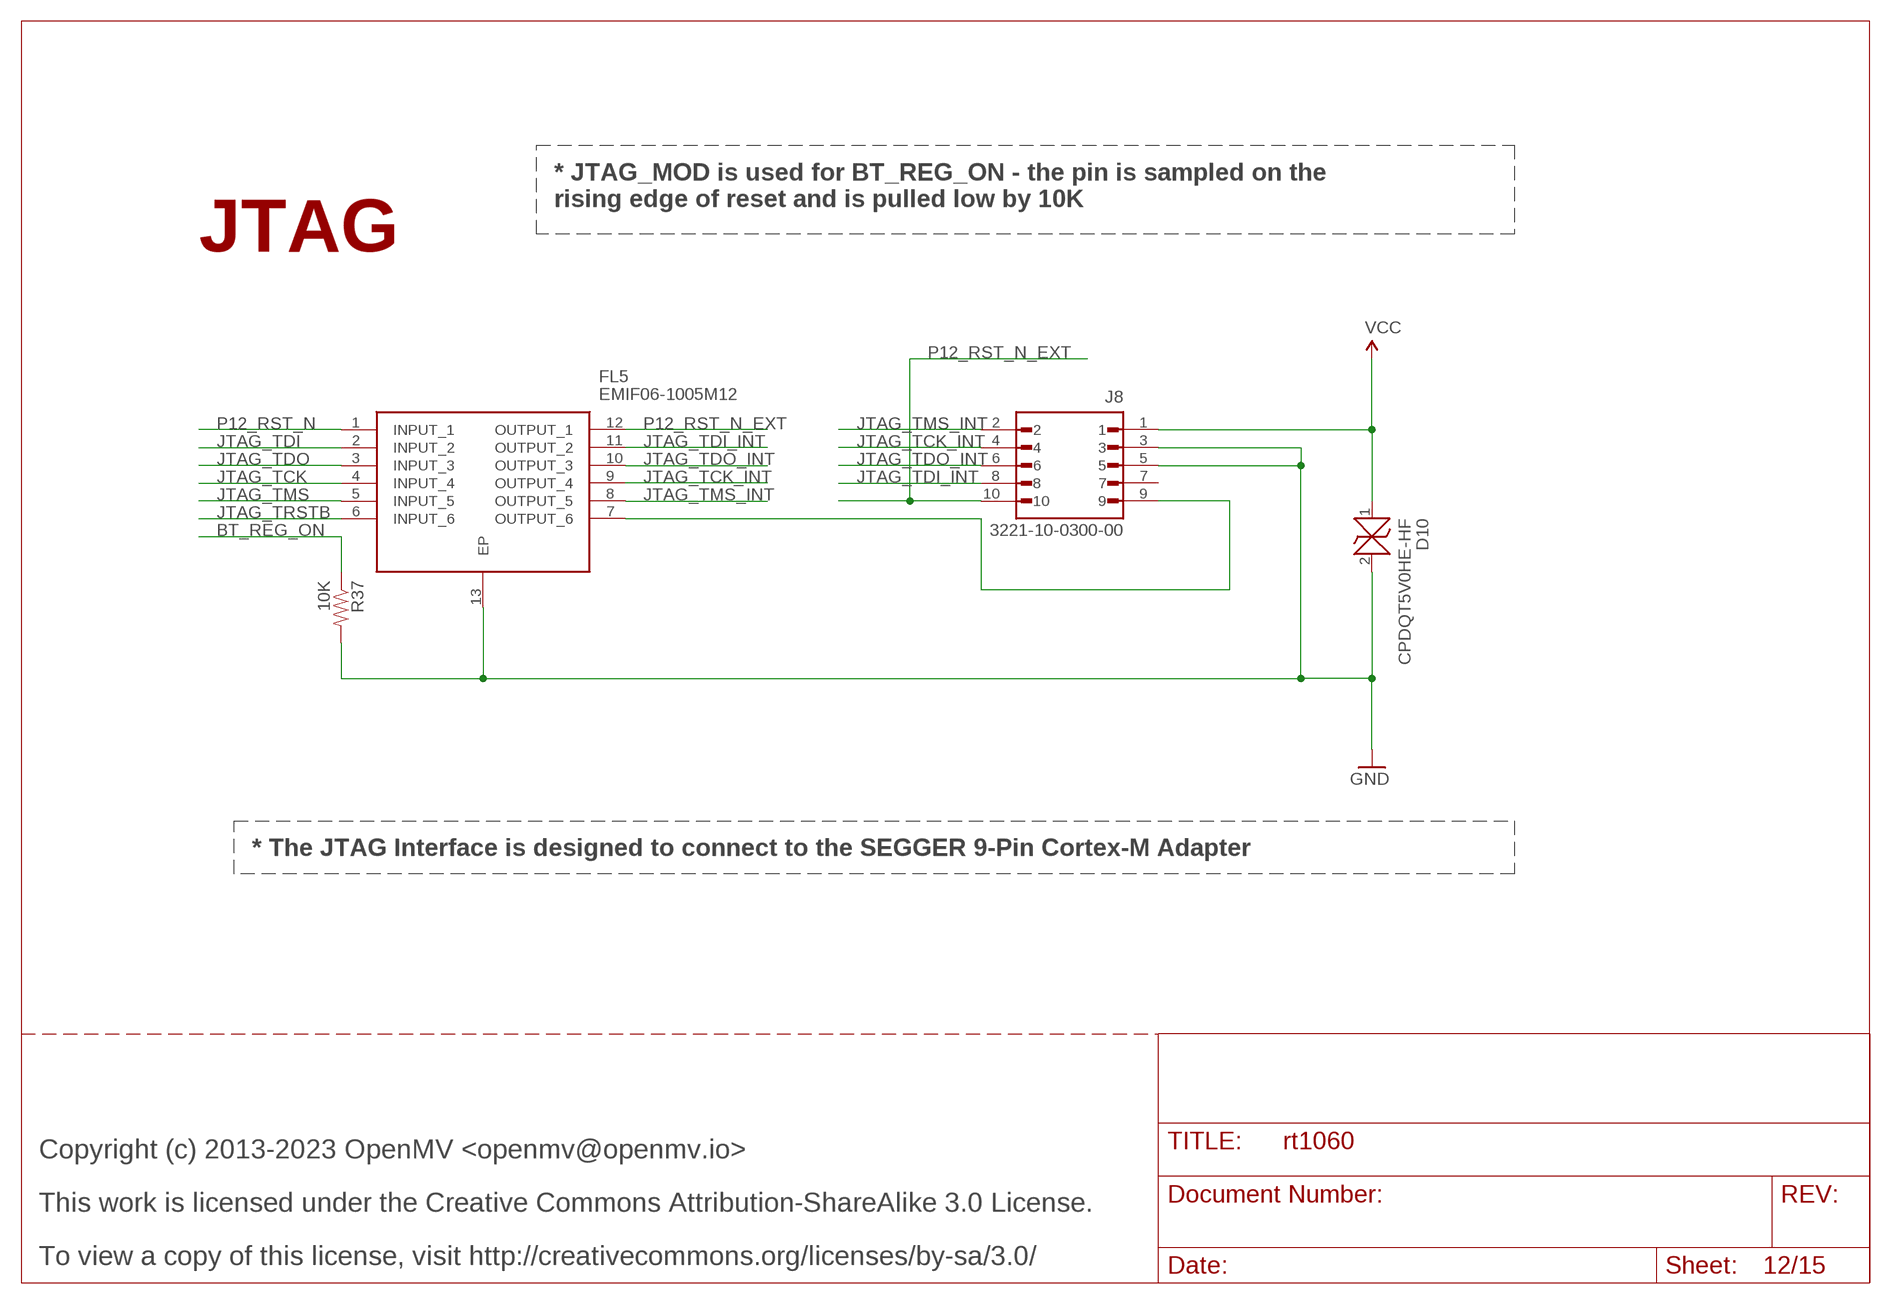
[diagram p11: schematic, sheet 12]
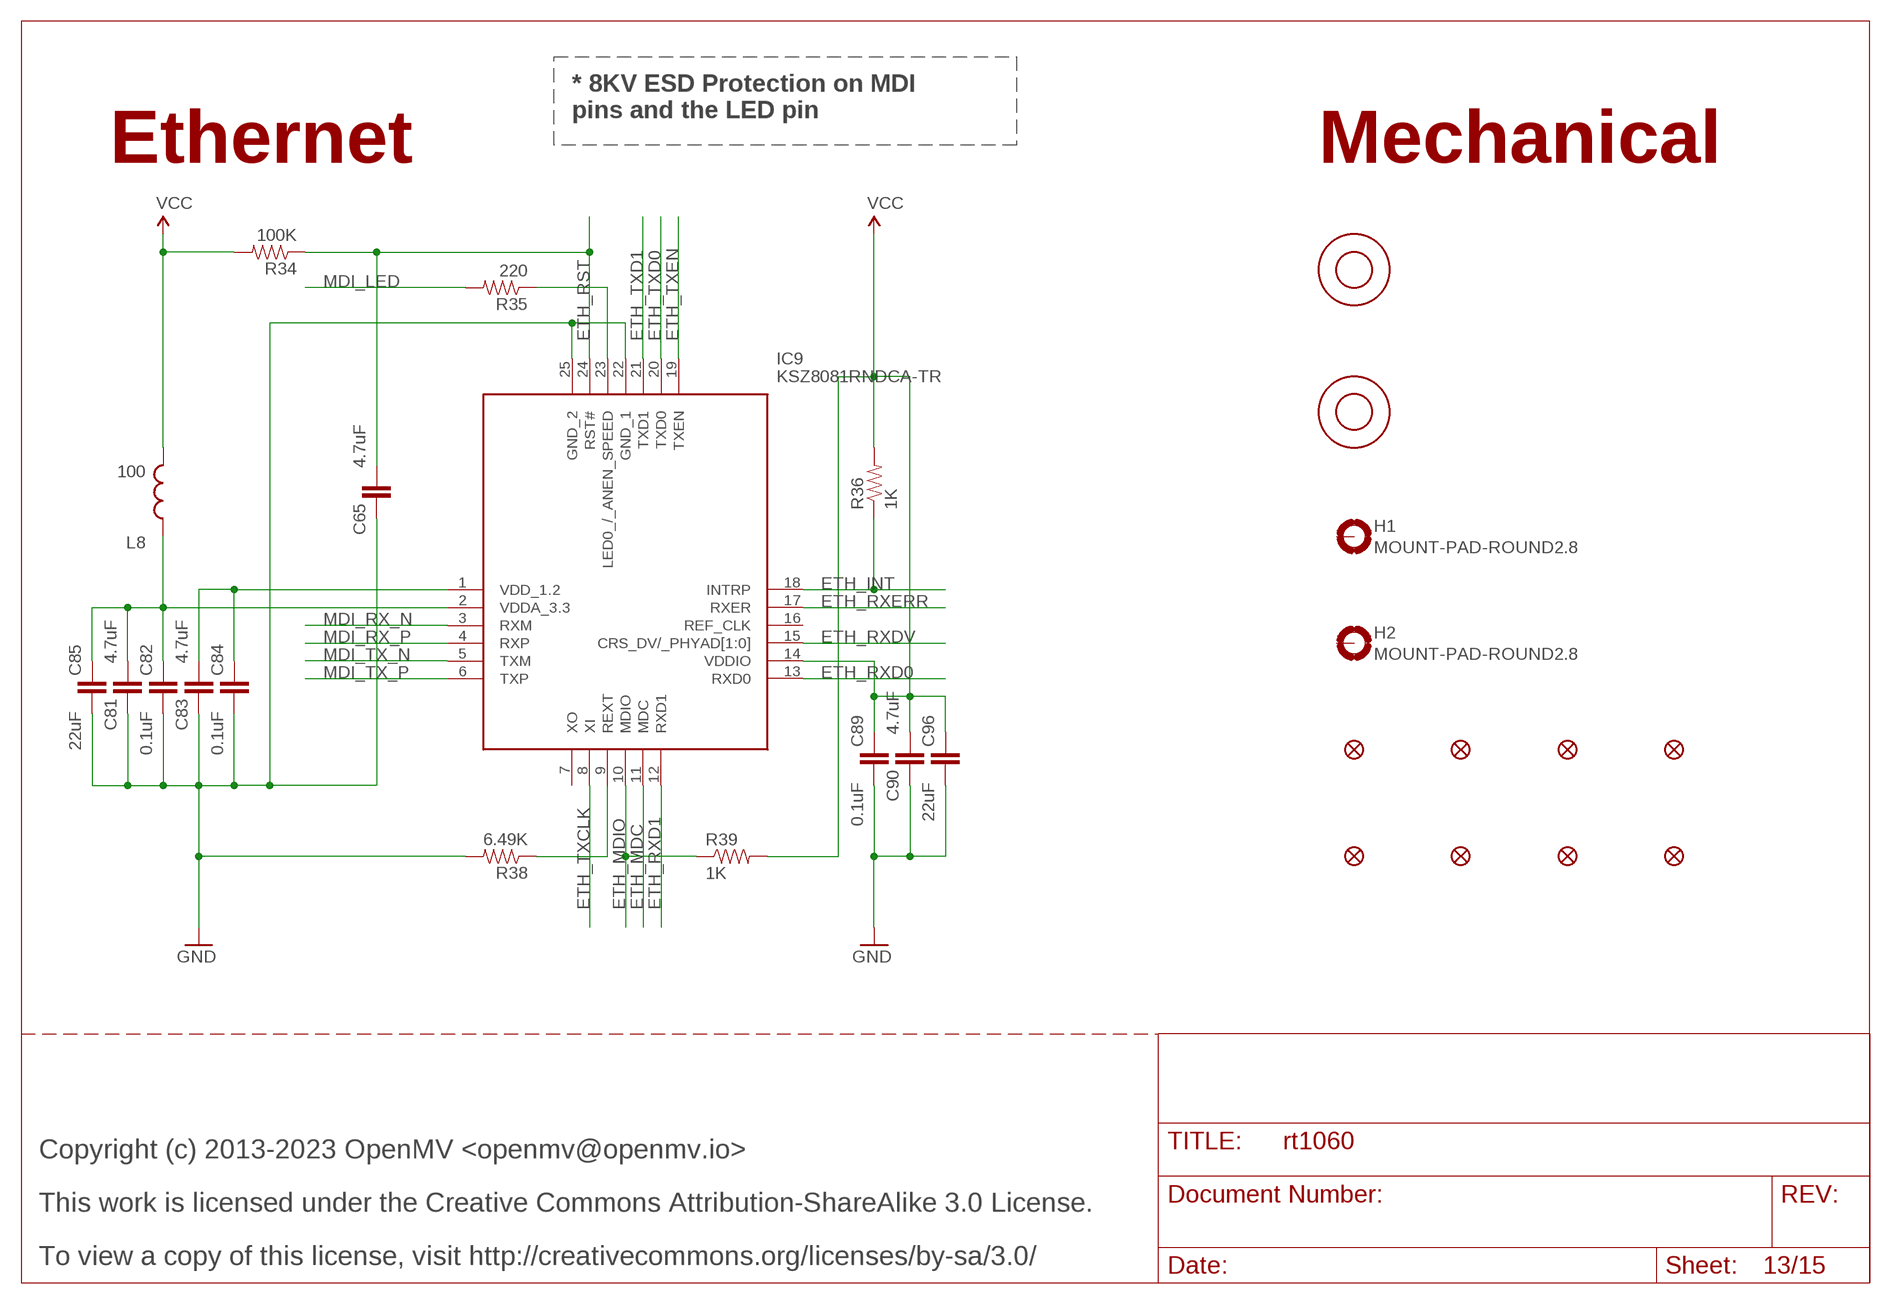
[diagram p12: schematic, sheet 13]
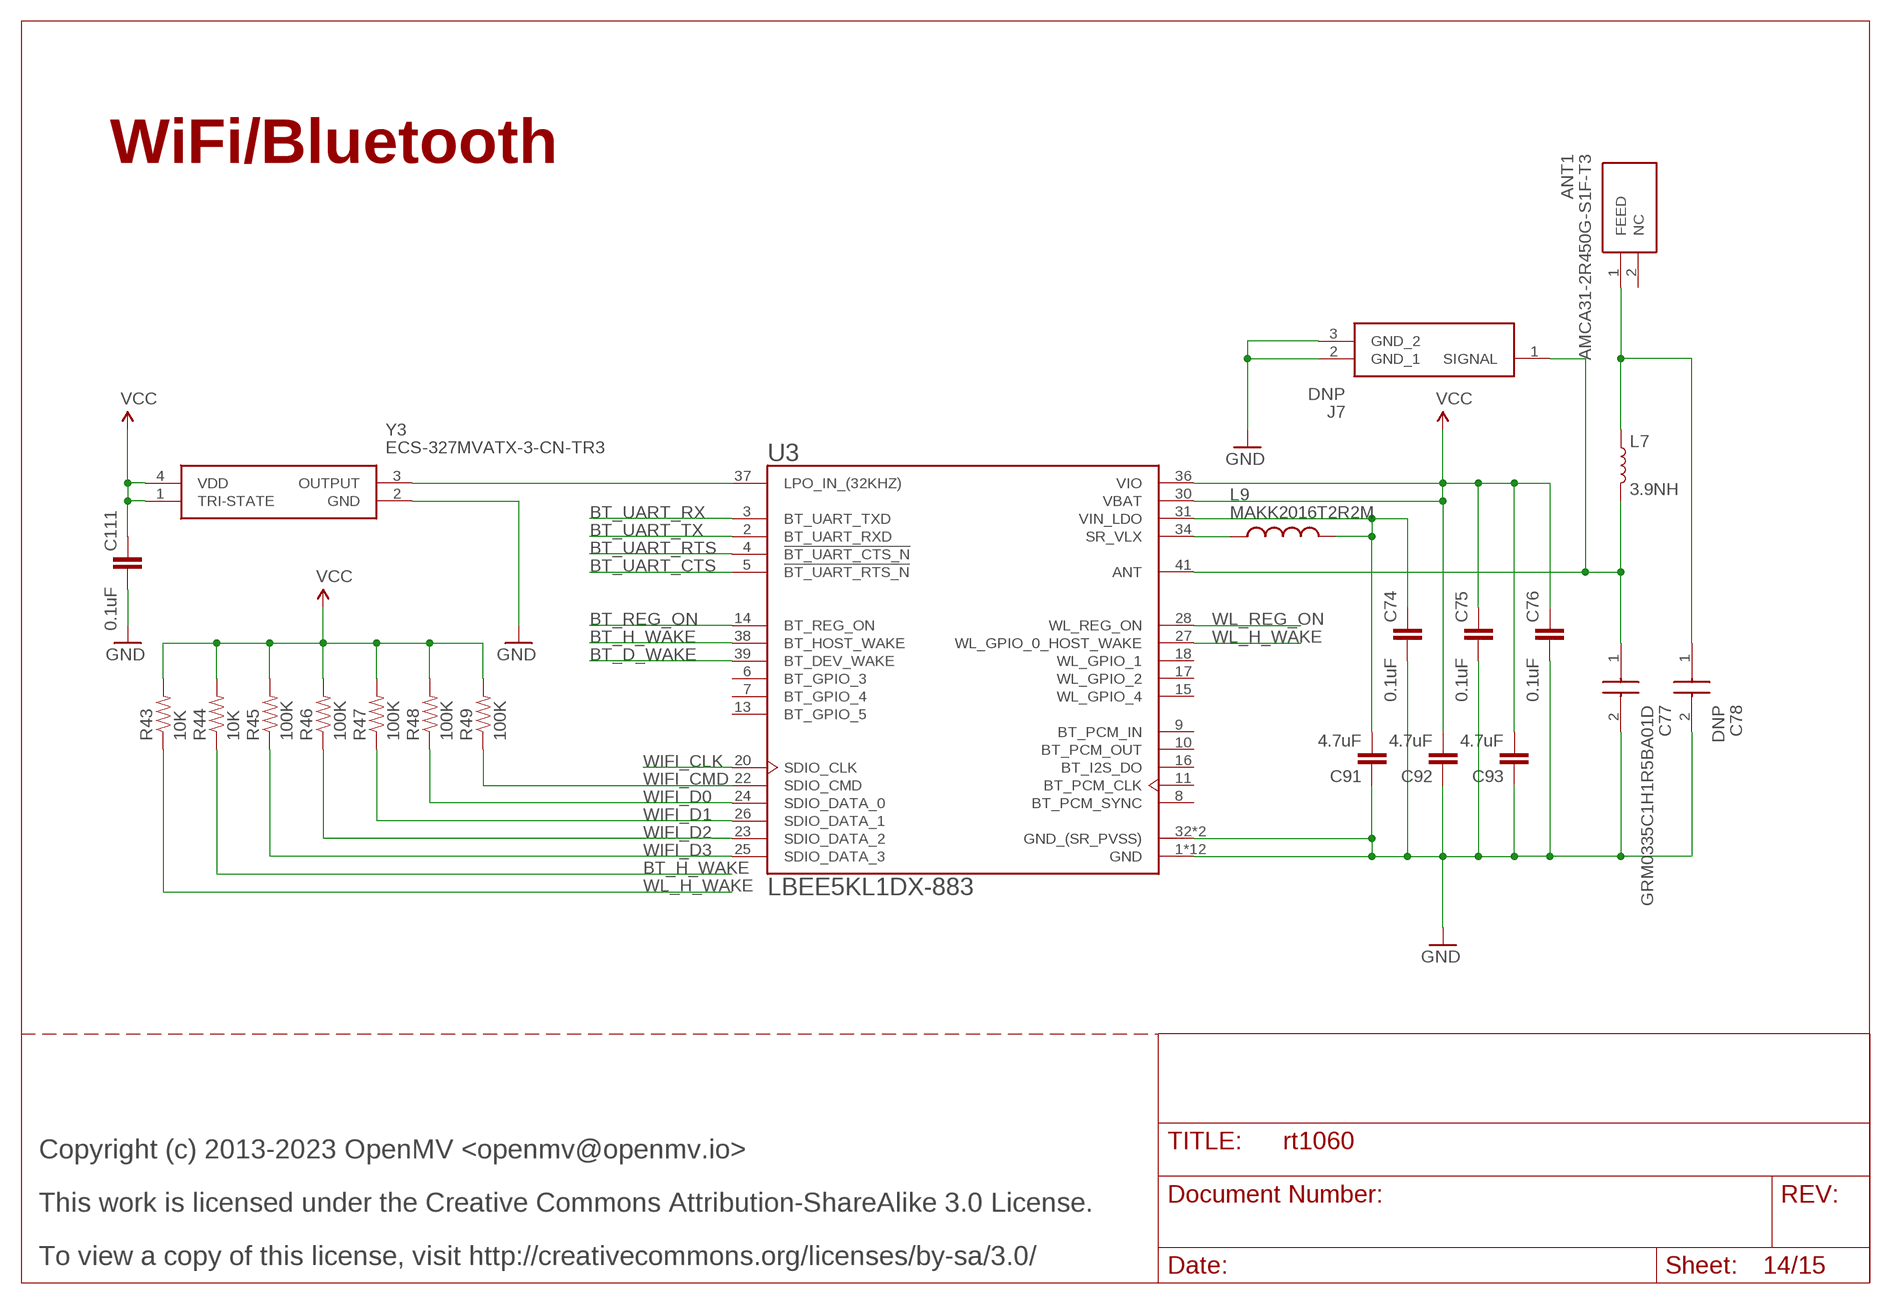
[diagram p13: schematic, sheet 14]
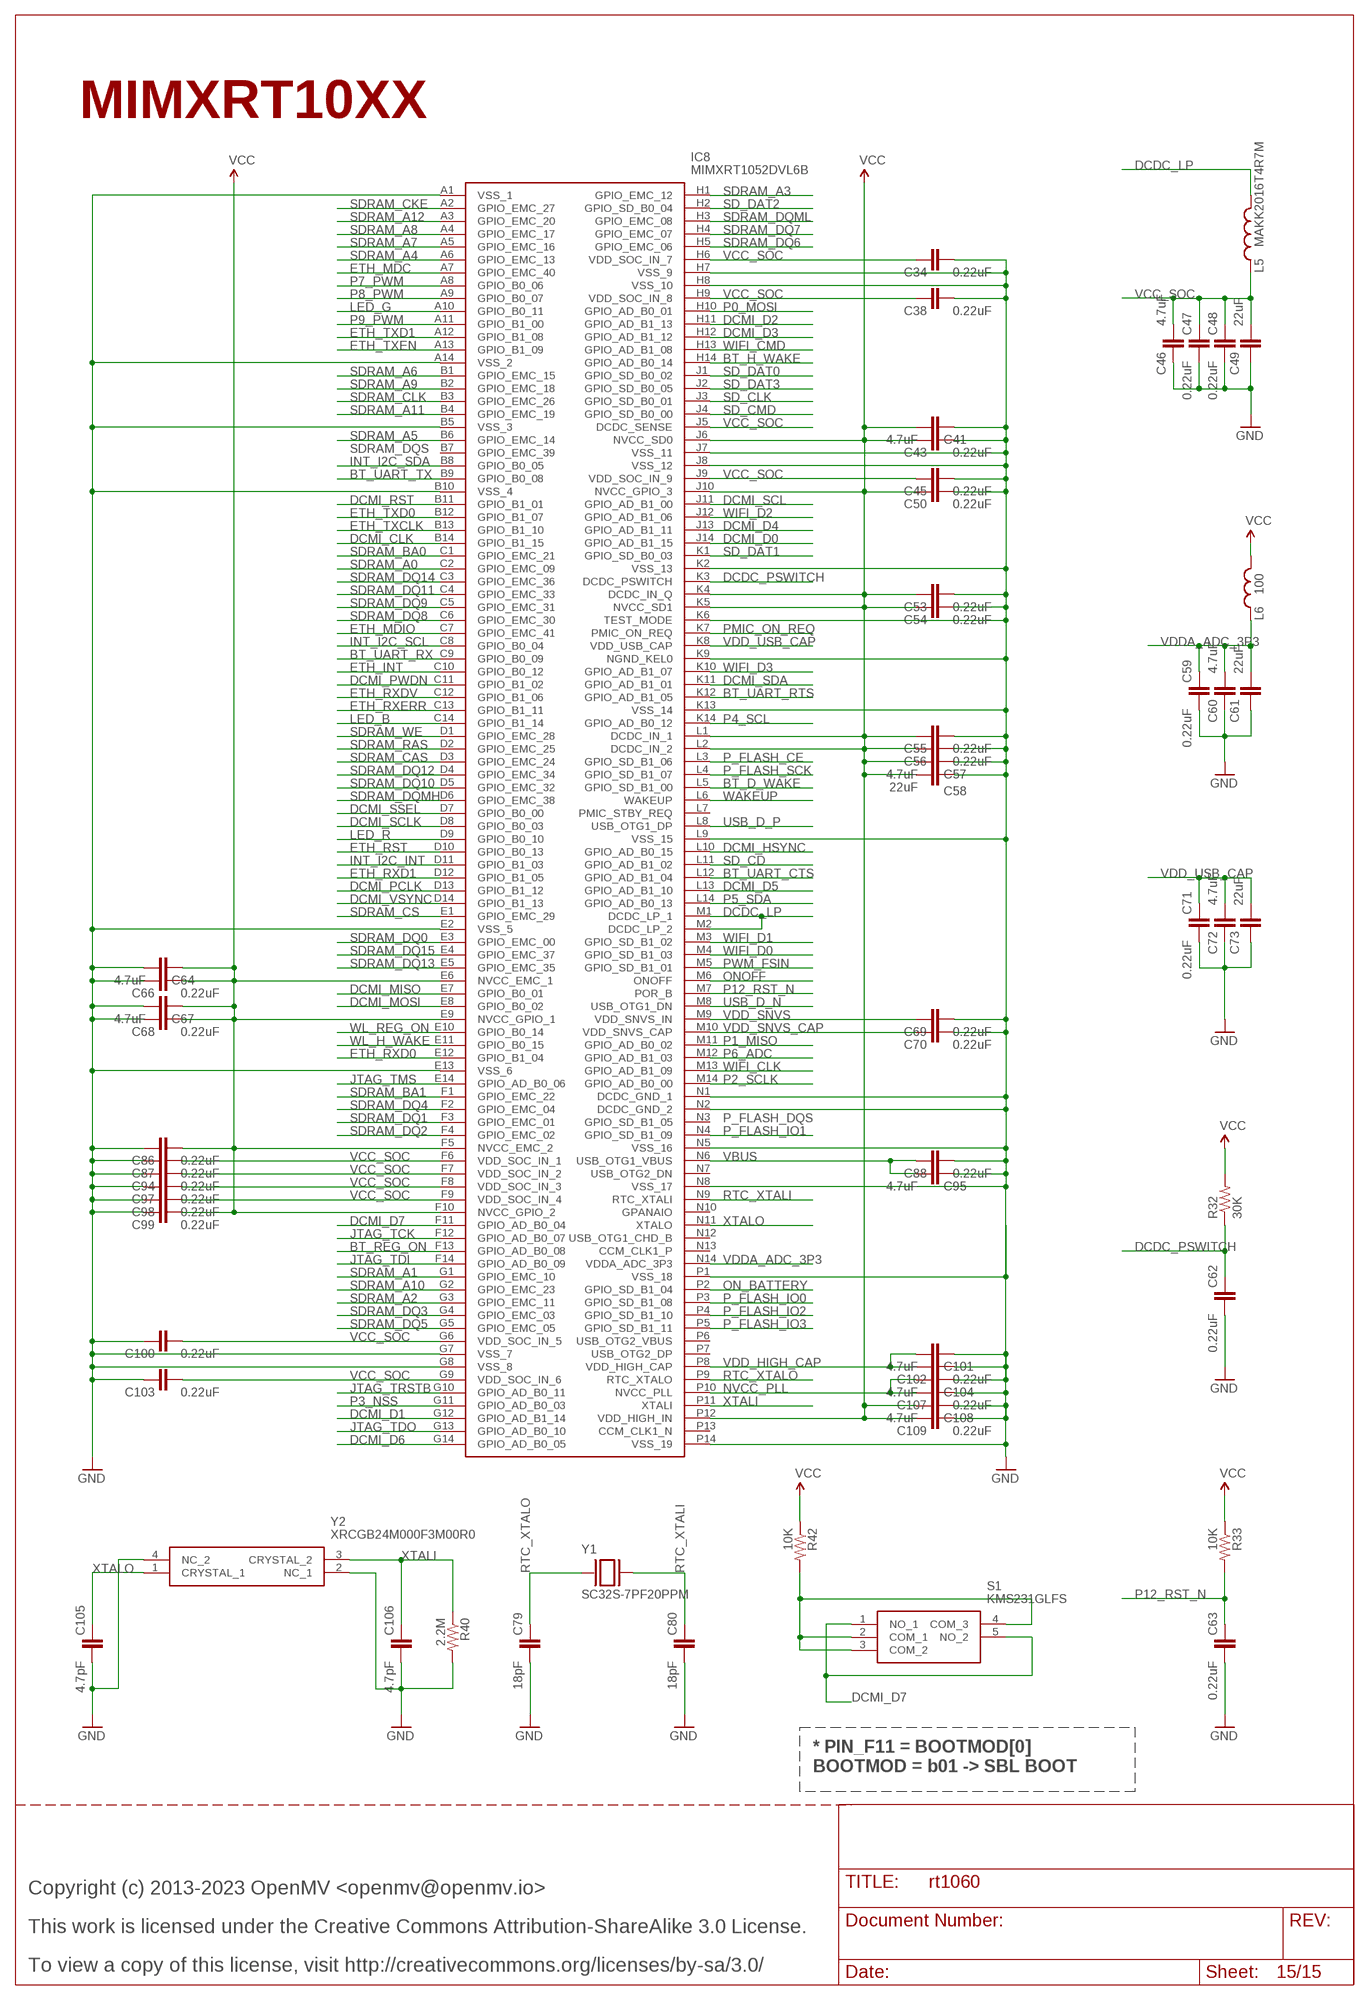
[diagram p14: schematic, sheet 15]

(export (version "E")
  (design (tool "Eeschema 10.0.6"))
  (components
    (comp (ref "D10")
      (value "CPDQT5V0HE-HF")
      (footprint "eagle-import:CPDQT5V0HEHF")
      (libsource (lib "eagle-import") (part "CPDQT5V0HE-HF"))
    )
    (comp (ref "FL5")
      (value "EMIF06-1005M12")
      (footprint "eagle-import:SON40P150X250X65-13N")
      (fields (field (name "MOUSER_PART_NUMBER") "511-EMIF06-1005M12"))
      (libsource (lib "eagle-import") (part "EMIF06-1005M12"))
    )
    (comp (ref "J8")
      (value "3221-10-0300-00")
      (footprint "eagle-import:CNC_3221-10-0300-00")
      (fields (field (name "MF") "CNC Tech"))
      (libsource (lib "eagle-import") (part "3221-10-0300-00"))
    )
    (comp (ref "R37")
      (value "10K")
      (footprint "eagle-import:0402-RES")
      (fields (field (name "MPN") "AC0402FR-1310KL"))
      (libsource (lib "eagle-import") (part "RESISTOR0402-RES"))
    )
    (comp (ref "C65")
      (value "4.7uF")
      (footprint "eagle-import:0402-CAP")
      (fields (field (name "MPN") "JMK105BBJ475MV-F"))
      (libsource (lib "eagle-import") (part "CAP0402-CAP"))
    )
    (comp (ref "C81")
      (value "4.7uF")
      (footprint "eagle-import:0402-CAP")
      (fields (field (name "MPN") "JMK105BBJ475MV-F"))
      (libsource (lib "eagle-import") (part "CAP0402-CAP"))
    )
    (comp (ref "C82")
      (value "0.1uF")
      (footprint "eagle-import:0402")
      (fields (field (name "MPN") "C0402C104Z4VAC"))
      (libsource (lib "eagle-import") (part "CAP_0402"))
    )
    (comp (ref "C83")
      (value "4.7uF")
      (footprint "eagle-import:0402-CAP")
      (fields (field (name "MPN") "JMK105BBJ475MV-F"))
      (libsource (lib "eagle-import") (part "CAP0402-CAP"))
    )
    (comp (ref "C84")
      (value "0.1uF")
      (footprint "eagle-import:0402")
      (fields (field (name "MPN") "C0402C104Z4VAC"))
      (libsource (lib "eagle-import") (part "CAP_0402"))
    )
    (comp (ref "C85")
      (value "22uF")
      (footprint "eagle-import:0805")
      (fields (field (name "MPN") "CL21A226MQQNNNE"))
      (libsource (lib "eagle-import") (part "22UF-0805-6.3V-20%"))
    )
    (comp (ref "C89")
      (value "0.1uF")
      (footprint "eagle-import:0402")
      (fields (field (name "MPN") "C0402C104Z4VAC"))
      (libsource (lib "eagle-import") (part "CAP_0402"))
    )
    (comp (ref "C90")
      (value "4.7uF")
      (footprint "eagle-import:0402-CAP")
      (fields (field (name "MPN") "JMK105BBJ475MV-F"))
      (libsource (lib "eagle-import") (part "CAP0402-CAP"))
    )
    (comp (ref "C96")
      (value "22uF")
      (footprint "eagle-import:0805")
      (fields (field (name "MPN") "CL21A226MQQNNNE"))
      (libsource (lib "eagle-import") (part "22UF-0805-6.3V-20%"))
    )
    (comp (ref "FD1")
      (value "FIDUCIAL1X2")
      (footprint "eagle-import:FIDUCIAL-1X2")
      (libsource (lib "eagle-import") (part "FIDUCIAL1X2"))
    )
    (comp (ref "FD2")
      (value "FIDUCIAL1X2")
      (footprint "eagle-import:FIDUCIAL-1X2")
      (libsource (lib "eagle-import") (part "FIDUCIAL1X2"))
    )
    (comp (ref "FD3")
      (value "FIDUCIAL1X2")
      (footprint "eagle-import:FIDUCIAL-1X2")
      (libsource (lib "eagle-import") (part "FIDUCIAL1X2"))
    )
    (comp (ref "FD4")
      (value "FIDUCIAL1X2")
      (footprint "eagle-import:FIDUCIAL-1X2")
      (libsource (lib "eagle-import") (part "FIDUCIAL1X2"))
    )
    (comp (ref "FD5")
      (value "FIDUCIAL1X2")
      (footprint "eagle-import:FIDUCIAL-1X2")
      (libsource (lib "eagle-import") (part "FIDUCIAL1X2"))
    )
    (comp (ref "FD6")
      (value "FIDUCIAL1X2")
      (footprint "eagle-import:FIDUCIAL-1X2")
      (libsource (lib "eagle-import") (part "FIDUCIAL1X2"))
    )
    (comp (ref "FD7")
      (value "FIDUCIAL1X2")
      (footprint "eagle-import:FIDUCIAL-1X2")
      (libsource (lib "eagle-import") (part "FIDUCIAL1X2"))
    )
    (comp (ref "FD8")
      (value "FIDUCIAL1X2")
      (footprint "eagle-import:FIDUCIAL-1X2")
      (libsource (lib "eagle-import") (part "FIDUCIAL1X2"))
    )
    (comp (ref "H1")
      (value "MOUNT-PAD-ROUND2.8")
      (footprint "eagle-import:2,8-PAD")
      (libsource (lib "eagle-import") (part "MOUNT-PAD-ROUND2.8"))
    )
    (comp (ref "H2")
      (value "MOUNT-PAD-ROUND2.8")
      (footprint "eagle-import:2,8-PAD")
      (libsource (lib "eagle-import") (part "MOUNT-PAD-ROUND2.8"))
    )
    (comp (ref "IC9")
      (value "KSZ8081RNDCA-TR")
      (footprint "eagle-import:QFN50P400X400X90-25N")
      (fields (field (name "MOUSER_PART_NUMBER") "998-KSZ8081RNDCATR"))
      (libsource (lib "eagle-import") (part "KSZ8081RNDCA-TR"))
    )
    (comp (ref "L8")
      (value "100")
      (footprint "eagle-import:C0402")
      (fields (field (name "MPN") "MFBM1V1005-101-R"))
      (libsource (lib "eagle-import") (part "INDUCTOR0402"))
    )
    (comp (ref "M1")
      (value "9774030151R")
      (footprint "eagle-import:9774030151R")
      (libsource (lib "eagle-import") (part "9774030151R"))
    )
    (comp (ref "M2")
      (value "9774030151R")
      (footprint "eagle-import:9774030151R")
      (libsource (lib "eagle-import") (part "9774030151R"))
    )
    (comp (ref "R34")
      (value "100K")
      (footprint "eagle-import:0402-RES")
      (fields (field (name "MPN") "AC0402FR-07100KL"))
      (libsource (lib "eagle-import") (part "RESISTOR0402-RES"))
    )
    (comp (ref "R35")
      (value "220")
      (footprint "eagle-import:0402-RES")
      (fields (field (name "MPN") "CRGCQ0402F220R"))
      (libsource (lib "eagle-import") (part "RESISTOR0402-RES"))
    )
    (comp (ref "R36")
      (value "1K")
      (footprint "eagle-import:0402-RES")
      (fields (field (name "MPN") "CRCW04021K00FKEDC"))
      (libsource (lib "eagle-import") (part "RESISTOR0402-RES"))
    )
    (comp (ref "R38")
      (value "6.49K")
      (footprint "eagle-import:0402-RES")
      (fields (field (name "MPN") "CR0402-FX-6491GLF"))
      (libsource (lib "eagle-import") (part "RESISTOR0402-RES"))
    )
    (comp (ref "R39")
      (value "1K")
      (footprint "eagle-import:0402-RES")
      (fields (field (name "MPN") "CRCW04021K00FKEDC"))
      (libsource (lib "eagle-import") (part "RESISTOR0402-RES"))
    )
    (comp (ref "C34")
      (value "0.22uF")
      (footprint "eagle-import:C0201")
      (fields (field (name "MPN") "GRM033R60J224ME15D"))
      (libsource (lib "eagle-import") (part "C-EUC0201"))
    )
    (comp (ref "C38")
      (value "0.22uF")
      (footprint "eagle-import:C0201")
      (fields (field (name "MPN") "GRM033R60J224ME15D"))
      (libsource (lib "eagle-import") (part "C-EUC0201"))
    )
    (comp (ref "C41")
      (value "4.7uF")
      (footprint "eagle-import:0402-CAP")
      (fields (field (name "MPN") "JMK105BBJ475MV-F"))
      (libsource (lib "eagle-import") (part "CAP0402-CAP"))
    )
    (comp (ref "C43")
      (value "0.22uF")
      (footprint "eagle-import:C0201")
      (fields (field (name "MPN") "GRM033R60J224ME15D"))
      (libsource (lib "eagle-import") (part "C-EUC0201"))
    )
    (comp (ref "C45")
      (value "0.22uF")
      (footprint "eagle-import:C0201")
      (fields (field (name "MPN") "GRM033R60J224ME15D"))
      (libsource (lib "eagle-import") (part "C-EUC0201"))
    )
    (comp (ref "C46")
      (value "4.7uF")
      (footprint "eagle-import:0402-CAP")
      (fields (field (name "MPN") "JMK105BBJ475MV-F"))
      (libsource (lib "eagle-import") (part "CAP0402-CAP"))
    )
    (comp (ref "C47")
      (value "0.22uF")
      (footprint "eagle-import:C0201")
      (fields (field (name "MPN") "GRM033R60J224ME15D"))
      (libsource (lib "eagle-import") (part "C-EUC0201"))
    )
    (comp (ref "C48")
      (value "0.22uF")
      (footprint "eagle-import:C0201")
      (fields (field (name "MPN") "GRM033R60J224ME15D"))
      (libsource (lib "eagle-import") (part "C-EUC0201"))
    )
    (comp (ref "C49")
      (value "22uF")
      (footprint "eagle-import:0805")
      (fields (field (name "MPN") "CL21A226MQQNNNE"))
      (libsource (lib "eagle-import") (part "22UF-0805-6.3V-20%"))
    )
    (comp (ref "C50")
      (value "0.22uF")
      (footprint "eagle-import:C0201")
      (fields (field (name "MPN") "GRM033R60J224ME15D"))
      (libsource (lib "eagle-import") (part "C-EUC0201"))
    )
    (comp (ref "C53")
      (value "0.22uF")
      (footprint "eagle-import:C0201")
      (fields (field (name "MPN") "GRM033R60J224ME15D"))
      (libsource (lib "eagle-import") (part "C-EUC0201"))
    )
    (comp (ref "C54")
      (value "0.22uF")
      (footprint "eagle-import:C0201")
      (fields (field (name "MPN") "GRM033R60J224ME15D"))
      (libsource (lib "eagle-import") (part "C-EUC0201"))
    )
    (comp (ref "C55")
      (value "0.22uF")
      (footprint "eagle-import:C0201")
      (fields (field (name "MPN") "GRM033R60J224ME15D"))
      (libsource (lib "eagle-import") (part "C-EUC0201"))
    )
    (comp (ref "C56")
      (value "0.22uF")
      (footprint "eagle-import:C0201")
      (fields (field (name "MPN") "GRM033R60J224ME15D"))
      (libsource (lib "eagle-import") (part "C-EUC0201"))
    )
    (comp (ref "C57")
      (value "4.7uF")
      (footprint "eagle-import:0402-CAP")
      (fields (field (name "MPN") "JMK105BBJ475MV-F"))
      (libsource (lib "eagle-import") (part "CAP0402-CAP"))
    )
    (comp (ref "C58")
      (value "22uF")
      (footprint "eagle-import:0805")
      (fields (field (name "MPN") "CL21A226MQQNNNE"))
      (libsource (lib "eagle-import") (part "22UF-0805-6.3V-20%"))
    )
    (comp (ref "C59")
      (value "0.22uF")
      (footprint "eagle-import:C0201")
      (fields (field (name "MPN") "GRM033R60J224ME15D"))
      (libsource (lib "eagle-import") (part "C-EUC0201"))
    )
    (comp (ref "C60")
      (value "4.7uF")
      (footprint "eagle-import:0402-CAP")
      (fields (field (name "MPN") "JMK105BBJ475MV-F"))
      (libsource (lib "eagle-import") (part "CAP0402-CAP"))
    )
    (comp (ref "C61")
      (value "22uF")
      (footprint "eagle-import:0805")
      (fields (field (name "MPN") "CL21A226MQQNNNE"))
      (libsource (lib "eagle-import") (part "22UF-0805-6.3V-20%"))
    )
    (comp (ref "C62")
      (value "0.22uF")
      (footprint "eagle-import:C0201")
      (fields (field (name "MPN") "GRM033R60J224ME15D"))
      (libsource (lib "eagle-import") (part "C-EUC0201"))
    )
    (comp (ref "C63")
      (value "0.22uF")
      (footprint "eagle-import:C0201")
      (fields (field (name "MPN") "GRM033R60J224ME15D"))
      (libsource (lib "eagle-import") (part "C-EUC0201"))
    )
    (comp (ref "C64")
      (value "4.7uF")
      (footprint "eagle-import:0402-CAP")
      (fields (field (name "MPN") "JMK105BBJ475MV-F"))
      (libsource (lib "eagle-import") (part "CAP0402-CAP"))
    )
    (comp (ref "C66")
      (value "0.22uF")
      (footprint "eagle-import:C0201")
      (fields (field (name "MPN") "GRM033R60J224ME15D"))
      (libsource (lib "eagle-import") (part "C-EUC0201"))
    )
    (comp (ref "C67")
      (value "4.7uF")
      (footprint "eagle-import:0402-CAP")
      (fields (field (name "MPN") "JMK105BBJ475MV-F"))
      (libsource (lib "eagle-import") (part "CAP0402-CAP"))
    )
    (comp (ref "C68")
      (value "0.22uF")
      (footprint "eagle-import:C0201")
      (fields (field (name "MPN") "GRM033R60J224ME15D"))
      (libsource (lib "eagle-import") (part "C-EUC0201"))
    )
    (comp (ref "C69")
      (value "0.22uF")
      (footprint "eagle-import:C0201")
      (fields (field (name "MPN") "GRM033R60J224ME15D"))
      (libsource (lib "eagle-import") (part "C-EUC0201"))
    )
    (comp (ref "C70")
      (value "0.22uF")
      (footprint "eagle-import:C0201")
      (fields (field (name "MPN") "GRM033R60J224ME15D"))
      (libsource (lib "eagle-import") (part "C-EUC0201"))
    )
    (comp (ref "C71")
      (value "0.22uF")
      (footprint "eagle-import:C0201")
      (fields (field (name "MPN") "GRM033R60J224ME15D"))
      (libsource (lib "eagle-import") (part "C-EUC0201"))
    )
    (comp (ref "C72")
      (value "4.7uF")
      (footprint "eagle-import:0402-CAP")
      (fields (field (name "MPN") "JMK105BBJ475MV-F"))
      (libsource (lib "eagle-import") (part "CAP0402-CAP"))
    )
    (comp (ref "C73")
      (value "22uF")
      (footprint "eagle-import:0805")
      (fields (field (name "MPN") "CL21A226MQQNNNE"))
      (libsource (lib "eagle-import") (part "22UF-0805-6.3V-20%"))
    )
    (comp (ref "C79")
      (value "18pF")
      (footprint "eagle-import:C0201")
      (fields (field (name "MPN") "GRM0335C1E180JA01D"))
      (libsource (lib "eagle-import") (part "C-EUC0201"))
    )
    (comp (ref "C80")
      (value "18pF")
      (footprint "eagle-import:C0201")
      (fields (field (name "MPN") "GRM0335C1E180JA01D"))
      (libsource (lib "eagle-import") (part "C-EUC0201"))
    )
    (comp (ref "C86")
      (value "0.22uF")
      (footprint "eagle-import:C0201")
      (fields (field (name "MPN") "GRM033R60J224ME15D"))
      (libsource (lib "eagle-import") (part "C-EUC0201"))
    )
    (comp (ref "C87")
      (value "0.22uF")
      (footprint "eagle-import:C0201")
      (fields (field (name "MPN") "GRM033R60J224ME15D"))
      (libsource (lib "eagle-import") (part "C-EUC0201"))
    )
    (comp (ref "C88")
      (value "0.22uF")
      (footprint "eagle-import:C0201")
      (fields (field (name "MPN") "GRM033R60J224ME15D"))
      (libsource (lib "eagle-import") (part "C-EUC0201"))
    )
    (comp (ref "C94")
      (value "0.22uF")
      (footprint "eagle-import:C0201")
      (fields (field (name "MPN") "GRM033R60J224ME15D"))
      (libsource (lib "eagle-import") (part "C-EUC0201"))
    )
    (comp (ref "C95")
      (value "4.7uF")
      (footprint "eagle-import:0402-CAP")
      (fields (field (name "MPN") "JMK105BBJ475MV-F"))
      (libsource (lib "eagle-import") (part "CAP0402-CAP"))
    )
    (comp (ref "C97")
      (value "0.22uF")
      (footprint "eagle-import:C0201")
      (fields (field (name "MPN") "GRM033R60J224ME15D"))
      (libsource (lib "eagle-import") (part "C-EUC0201"))
    )
    (comp (ref "C98")
      (value "0.22uF")
      (footprint "eagle-import:C0201")
      (fields (field (name "MPN") "GRM033R60J224ME15D"))
      (libsource (lib "eagle-import") (part "C-EUC0201"))
    )
    (comp (ref "C99")
      (value "0.22uF")
      (footprint "eagle-import:C0201")
      (fields (field (name "MPN") "GRM033R60J224ME15D"))
      (libsource (lib "eagle-import") (part "C-EUC0201"))
    )
    (comp (ref "C100")
      (value "0.22uF")
      (footprint "eagle-import:C0201")
      (fields (field (name "MPN") "GRM033R60J224ME15D"))
      (libsource (lib "eagle-import") (part "C-EUC0201"))
    )
    (comp (ref "C101")
      (value "4.7uF")
      (footprint "eagle-import:0402-CAP")
      (fields (field (name "MPN") "JMK105BBJ475MV-F"))
      (libsource (lib "eagle-import") (part "CAP0402-CAP"))
    )
    (comp (ref "C102")
      (value "0.22uF")
      (footprint "eagle-import:C0201")
      (fields (field (name "MPN") "GRM033R60J224ME15D"))
      (libsource (lib "eagle-import") (part "C-EUC0201"))
    )
    (comp (ref "C103")
      (value "0.22uF")
      (footprint "eagle-import:C0201")
      (fields (field (name "MPN") "GRM033R60J224ME15D"))
      (libsource (lib "eagle-import") (part "C-EUC0201"))
    )
    (comp (ref "C104")
      (value "4.7uF")
      (footprint "eagle-import:0402-CAP")
      (fields (field (name "MPN") "JMK105BBJ475MV-F"))
      (libsource (lib "eagle-import") (part "CAP0402-CAP"))
    )
    (comp (ref "C105")
      (value "4.7pF")
      (footprint "eagle-import:C0201")
      (fields (field (name "MPN") "GRM0335C1E4R7CA01D"))
      (libsource (lib "eagle-import") (part "C-EUC0201"))
    )
    (comp (ref "C106")
      (value "4.7pF")
      (footprint "eagle-import:C0201")
      (fields (field (name "MPN") "GRM0335C1E4R7CA01D"))
      (libsource (lib "eagle-import") (part "C-EUC0201"))
    )
    (comp (ref "C107")
      (value "0.22uF")
      (footprint "eagle-import:C0201")
      (fields (field (name "MPN") "GRM033R60J224ME15D"))
      (libsource (lib "eagle-import") (part "C-EUC0201"))
    )
    (comp (ref "C108")
      (value "4.7uF")
      (footprint "eagle-import:0402-CAP")
      (fields (field (name "MPN") "JMK105BBJ475MV-F"))
      (libsource (lib "eagle-import") (part "CAP0402-CAP"))
    )
    (comp (ref "C109")
      (value "0.22uF")
      (footprint "eagle-import:C0201")
      (fields (field (name "MPN") "GRM033R60J224ME15D"))
      (libsource (lib "eagle-import") (part "C-EUC0201"))
    )
    (comp (ref "IC8")
      (value "MIMXRT1052DVL6B")
      (footprint "eagle-import:BGA196C65P14X14_1000X1000X143")
      (fields (field (name "MOUSER_PART_NUMBER") "771-MIMXRT1052DVL6B"))
      (libsource (lib "eagle-import") (part "MIMXRT1052DVL6B"))
    )
    (comp (ref "L5")
      (value "MAKK2016T4R7M")
      (footprint "eagle-import:INDC2016X100N")
      (fields (field (name "MF") "Taiyo Yuden"))
      (libsource (lib "eagle-import") (part "MAKK2016T4R7M"))
    )
    (comp (ref "L6")
      (value "100")
      (footprint "eagle-import:C0402")
      (fields (field (name "MPN") "MFBM1V1005-101-R"))
      (libsource (lib "eagle-import") (part "INDUCTOR0402"))
    )
    (comp (ref "R32")
      (value "30K")
      (footprint "eagle-import:0402-RES")
      (fields (field (name "MPN") "0402WGF3002TCE"))
      (libsource (lib "eagle-import") (part "RESISTOR0402-RES"))
    )
    (comp (ref "R33")
      (value "10K")
      (footprint "eagle-import:0402-RES")
      (fields (field (name "MPN") "AC0402FR-1310KL"))
      (libsource (lib "eagle-import") (part "RESISTOR0402-RES"))
    )
    (comp (ref "R40")
      (value "2.2M")
      (footprint "eagle-import:0402-RES")
      (fields (field (name "MPN") "RC0402FR-072M2L"))
      (libsource (lib "eagle-import") (part "RESISTOR0402-RES"))
    )
    (comp (ref "R42")
      (value "10K")
      (footprint "eagle-import:0402-RES")
      (fields (field (name "MPN") "AC0402FR-1310KL"))
      (libsource (lib "eagle-import") (part "RESISTOR0402-RES"))
    )
    (comp (ref "S1")
      (value "KMS231GLFS")
      (footprint "eagle-import:KMS231GLFS")
      (fields (field (name "MOUSER_PART_NUMBER") "611-KMS231GLFS"))
      (libsource (lib "eagle-import") (part "KMS231GLFS"))
    )
    (comp (ref "Y1")
      (value "SC32S-7PF20PPM")
      (footprint "eagle-import:XTAL_ABS07-32.768KHZ-7-T")
      (fields (field (name "MF") "Abracon") (field (name "MP") "ABS07-32.768KHZ-7-T"))
      (libsource (lib "eagle-import") (part "ABS07-32.768KHZ-7-T"))
    )
    (comp (ref "Y2")
      (value "XRCGB24M000F3M00R0")
      (footprint "eagle-import:XRCGB24M000F3M00R0")
      (fields (field (name "MOUSER_PART_NUMBER") "81-XRCGB24M000F3M0R0"))
      (libsource (lib "eagle-import") (part "XRCGB24M000F3M00R0"))
    )
    (comp (ref "C110")
      (value "1nF")
      (footprint "eagle-import:0402-CAP")
      (fields (field (name "MPN") "VJ0402Y102JXACW1BC"))
      (libsource (lib "eagle-import") (part "CAP0402-CAP"))
    )
    (comp (ref "FL1")
      (value "ECMF02-4CMX8")
      (footprint "eagle-import:ECMF024CMX8")
      (fields (field (name "MOUSER_PART_NUMBER") "511-ECMF02-4CMX8"))
      (libsource (lib "eagle-import") (part "ECMF02-4CMX8"))
    )
    (comp (ref "J1")
      (value "USB4105-GF-A")
      (footprint "eagle-import:GCT_USB4105-GF-A")
      (fields (field (name "MF") "GCT"))
      (libsource (lib "eagle-import") (part "USB4105-GF-A"))
    )
    (comp (ref "L1")
      (value "100")
      (footprint "eagle-import:0603")
      (fields (field (name "MPN") "MFBM1V1608-101-R"))
      (libsource (lib "eagle-import") (part "INDUCTOR-0603-33NH"))
    )
    (comp (ref "R6")
      (value "5.1K")
      (footprint "eagle-import:0402-RES")
      (fields (field (name "MPN") "RC0402JR-075K1L"))
      (libsource (lib "eagle-import") (part "RESISTOR0402-RES"))
    )
    (comp (ref "R7")
      (value "5.1K")
      (footprint "eagle-import:0402-RES")
      (fields (field (name "MPN") "RC0402JR-075K1L"))
      (libsource (lib "eagle-import") (part "RESISTOR0402-RES"))
    )
    (comp (ref "R41")
      (value "1M")
      (footprint "eagle-import:0402-RES")
      (fields (field (name "MPN") "CRCW04021M00FKEDC"))
      (libsource (lib "eagle-import") (part "RESISTOR0402-RES"))
    )
    (comp (ref "C11")
      (value "0.22uF")
      (footprint "eagle-import:C0201")
      (fields (field (name "MPN") "GRM033R60J224ME15D"))
      (libsource (lib "eagle-import") (part "C-EUC0201"))
    )
    (comp (ref "C12")
      (value "4.7uF")
      (footprint "eagle-import:0402-CAP")
      (fields (field (name "MPN") "JMK105BBJ475MV-F"))
      (libsource (lib "eagle-import") (part "CAP0402-CAP"))
    )
    (comp (ref "C13")
      (value "0.22uF")
      (footprint "eagle-import:C0201")
      (fields (field (name "MPN") "GRM033R60J224ME15D"))
      (libsource (lib "eagle-import") (part "C-EUC0201"))
    )
    (comp (ref "C14")
      (value "22uF")
      (footprint "eagle-import:0805")
      (fields (field (name "MPN") "CL21A226MQQNNNE"))
      (libsource (lib "eagle-import") (part "22UF-0805-6.3V-20%"))
    )
    (comp (ref "C15")
      (value "0.22uF")
      (footprint "eagle-import:C0201")
      (fields (field (name "MPN") "GRM033R60J224ME15D"))
      (libsource (lib "eagle-import") (part "C-EUC0201"))
    )
    (comp (ref "C16")
      (value "0.22uF")
      (footprint "eagle-import:C0201")
      (fields (field (name "MPN") "GRM033R60J224ME15D"))
      (libsource (lib "eagle-import") (part "C-EUC0201"))
    )
    (comp (ref "C17")
      (value "4.7uF")
      (footprint "eagle-import:0402-CAP")
      (fields (field (name "MPN") "JMK105BBJ475MV-F"))
      (libsource (lib "eagle-import") (part "CAP0402-CAP"))
    )
    (comp (ref "C18")
      (value "22uF")
      (footprint "eagle-import:0805")
      (fields (field (name "MPN") "CL21A226MQQNNNE"))
      (libsource (lib "eagle-import") (part "22UF-0805-6.3V-20%"))
    )
    (comp (ref "C19")
      (value "0.22uF")
      (footprint "eagle-import:C0201")
      (fields (field (name "MPN") "GRM033R60J224ME15D"))
      (libsource (lib "eagle-import") (part "C-EUC0201"))
    )
    (comp (ref "C28")
      (value "0.22uF")
      (footprint "eagle-import:C0201")
      (fields (field (name "MPN") "GRM033R60J224ME15D"))
      (libsource (lib "eagle-import") (part "C-EUC0201"))
    )
    (comp (ref "C29")
      (value "22uF")
      (footprint "eagle-import:0805")
      (fields (field (name "MPN") "CL21A226MQQNNNE"))
      (libsource (lib "eagle-import") (part "22UF-0805-6.3V-20%"))
    )
    (comp (ref "C30")
      (value "4.7uF")
      (footprint "eagle-import:0402-CAP")
      (fields (field (name "MPN") "JMK105BBJ475MV-F"))
      (libsource (lib "eagle-import") (part "CAP0402-CAP"))
    )
    (comp (ref "C31")
      (value "0.22uF")
      (footprint "eagle-import:C0201")
      (fields (field (name "MPN") "GRM033R60J224ME15D"))
      (libsource (lib "eagle-import") (part "C-EUC0201"))
    )
    (comp (ref "IC3")
      (value "IS42S16160G-6BL")
      (footprint "eagle-import:BGA54C80P9X9_800X800X120")
      (fields (field (name "MOUSER_PART_NUMBER") "870-IS42S16160G-6BL"))
      (libsource (lib "eagle-import") (part "IS42S16160G-6BL"))
    )
    (comp (ref "R18")
      (value "100K")
      (footprint "eagle-import:0402-RES")
      (fields (field (name "MPN") "AC0402FR-07100KL"))
      (libsource (lib "eagle-import") (part "RESISTOR0402-RES"))
    )
    (comp (ref "ANT1")
      (value "AMCA31-2R450G-S1F-T3")
      (footprint "eagle-import:ANTC3216X140N")
      (fields (field (name "MOUSER_PART_NUMBER") "815-CA312R450GS1FT3"))
      (libsource (lib "eagle-import") (part "AMCA31-2R450G-S1F-T3"))
    )
    (comp (ref "C74")
      (value "0.1uF")
      (footprint "eagle-import:0402")
      (fields (field (name "MPN") "C0402C104Z4VAC"))
      (libsource (lib "eagle-import") (part "CAP_0402"))
    )
    (comp (ref "C75")
      (value "0.1uF")
      (footprint "eagle-import:0402")
      (fields (field (name "MPN") "C0402C104Z4VAC"))
      (libsource (lib "eagle-import") (part "CAP_0402"))
    )
    (comp (ref "C76")
      (value "0.1uF")
      (footprint "eagle-import:0402")
      (fields (field (name "MPN") "C0402C104Z4VAC"))
      (libsource (lib "eagle-import") (part "CAP_0402"))
    )
    (comp (ref "C77")
      (value "GRM0335C1H1R5BA01D")
      (footprint "eagle-import:CAPC0603X33N")
      (fields (field (name "MOUSER_PART_NUMBER") "81-GRM0335C1H1R5BA1D"))
      (libsource (lib "eagle-import") (part "GRM0335C1H1R5BA01D"))
    )
    (comp (ref "C78")
      (value "DNP")
      (footprint "eagle-import:CAPC0603X33N")
      (fields
        (field (name "MANUFACTURER_PART_NUMBER") "GRM0335C1H1R5BA01D")
        (field (name "MOUSER_PART_NUMBER") "81-GRM0335C1H1R5BA1D")
      )
      (libsource (lib "eagle-import") (part "GRM0335C1H1R5BA01D"))
    )
    (comp (ref "C91")
      (value "4.7uF")
      (footprint "eagle-import:0402-CAP")
      (fields (field (name "MPN") "JMK105BBJ475MV-F"))
      (libsource (lib "eagle-import") (part "CAP0402-CAP"))
    )
    (comp (ref "C92")
      (value "4.7uF")
      (footprint "eagle-import:0402-CAP")
      (fields (field (name "MPN") "JMK105BBJ475MV-F"))
      (libsource (lib "eagle-import") (part "CAP0402-CAP"))
    )
    (comp (ref "C93")
      (value "4.7uF")
      (footprint "eagle-import:0402-CAP")
      (fields (field (name "MPN") "JMK105BBJ475MV-F"))
      (libsource (lib "eagle-import") (part "CAP0402-CAP"))
    )
    (comp (ref "C111")
      (value "0.1uF")
      (footprint "eagle-import:0402")
      (fields (field (name "MPN") "C0402C104Z4VAC"))
      (libsource (lib "eagle-import") (part "CAP_0402"))
    )
    (comp (ref "J7")
      (value "DNP")
      (footprint "eagle-import:23370191")
      (fields
        (field (name "MANUFACTURER_PART_NUMBER") "2337019-1")
        (field (name "MOUSER_PART_NUMBER") "571-2337019-1")
      )
      (libsource (lib "eagle-import") (part "2337019-1"))
    )
    (comp (ref "L7")
      (value "3.9NH")
      (footprint "eagle-import:0402")
      (fields (field (name "MPN") "L-07C3N9SV6T"))
      (libsource (lib "eagle-import") (part "INDUCTOR-0402-3.9NH"))
    )
    (comp (ref "L9")
      (value "MAKK2016T2R2M")
      (footprint "eagle-import:INDC2016X100N")
      (fields (field (name "MF") "Taiyo Yuden"))
      (libsource (lib "eagle-import") (part "MAKK2016T2R2M"))
    )
    (comp (ref "R43")
      (value "10K")
      (footprint "eagle-import:0402")
      (fields (field (name "MPN") "AC0402FR-1310KL"))
      (libsource (lib "eagle-import") (part "RES_0402"))
    )
    (comp (ref "R44")
      (value "10K")
      (footprint "eagle-import:0402")
      (fields (field (name "MPN") "AC0402FR-1310KL"))
      (libsource (lib "eagle-import") (part "RES_0402"))
    )
    (comp (ref "R45")
      (value "100K")
      (footprint "eagle-import:0402")
      (fields (field (name "MPN") "AC0402FR-07100KL"))
      (libsource (lib "eagle-import") (part "RES_0402"))
    )
    (comp (ref "R46")
      (value "100K")
      (footprint "eagle-import:0402")
      (fields (field (name "MPN") "AC0402FR-07100KL"))
      (libsource (lib "eagle-import") (part "RES_0402"))
    )
    (comp (ref "R47")
      (value "100K")
      (footprint "eagle-import:0402")
      (fields (field (name "MPN") "AC0402FR-07100KL"))
      (libsource (lib "eagle-import") (part "RES_0402"))
    )
    (comp (ref "R48")
      (value "100K")
      (footprint "eagle-import:0402")
      (fields (field (name "MPN") "AC0402FR-07100KL"))
      (libsource (lib "eagle-import") (part "RES_0402"))
    )
    (comp (ref "R49")
      (value "100K")
      (footprint "eagle-import:0402")
      (fields (field (name "MPN") "AC0402FR-07100KL"))
      (libsource (lib "eagle-import") (part "RES_0402"))
    )
    (comp (ref "U3")
      (value "LBEE5KL1DX-883")
      (footprint "eagle-import:XCVR_LBEE5KL1DX-TEMP")
      (fields (field (name "MF") "Murata Electronics") (field (name "MP") "LBEE5KL1DX-TEMP"))
      (libsource (lib "eagle-import") (part "LBEE5KL1DX-TEMP"))
    )
    (comp (ref "Y3")
      (value "ECS-327MVATX-3-CN-TR3")
      (footprint "eagle-import:ECS327MVATX3CNTR3")
      (fields (field (name "MOUSER_PART_NUMBER") "520-327MVATX-3-CNTR3"))
      (libsource (lib "eagle-import") (part "ECS-327MVATX-3-CN-TR3"))
    )
    (comp (ref "C3")
      (value "4.7uF")
      (footprint "eagle-import:0402-CAP")
      (fields (field (name "MPN") "JMK105BBJ475MV-F"))
      (libsource (lib "eagle-import") (part "CAP0402-CAP"))
    )
    (comp (ref "C4")
      (value "4.7uF")
      (footprint "eagle-import:0402-CAP")
      (fields (field (name "MPN") "JMK105BBJ475MV-F"))
      (libsource (lib "eagle-import") (part "CAP0402-CAP"))
    )
    (comp (ref "C5")
      (value "4.7uF")
      (footprint "eagle-import:0402-CAP")
      (fields (field (name "MPN") "JMK105BBJ475MV-F"))
      (libsource (lib "eagle-import") (part "CAP0402-CAP"))
    )
    (comp (ref "D1")
      (value "UHD1110-FKA-CL1A13R3Q1BBQFMF3")
      (footprint "eagle-import:LED_UHD1110-FKA-CL1A13R3Q1BBQFMF3")
      (fields (field (name "MF") "Cree Inc.") (field (name "MPN") "UHD1110-FKA-CL1A13r3q1BBQFMF3"))
      (libsource (lib "eagle-import") (part "UHD1110-FKA-CL1A13R3Q1BBQFMF3"))
    )
    (comp (ref "IC1")
      (value "LM66200DRLR")
      (footprint "eagle-import:SOTFL50P160X60-8N")
      (fields (field (name "MOUSER_PART_NUMBER") "595-LM66200DRLR"))
      (libsource (lib "eagle-import") (part "LM66200DRLR"))
    )
    (comp (ref "Q6")
      (value "DMG2301L-7")
      (footprint "eagle-import:SOT96P240X110-3N")
      (fields (field (name "MOUSER_PART_NUMBER") "621-DMG2301L-7"))
      (libsource (lib "eagle-import") (part "DMG2301L-7"))
    )
    (comp (ref "R5")
      (value "1K")
      (footprint "eagle-import:0402-RES")
      (fields (field (name "MPN") "CRCW04021K00FKEDC"))
      (libsource (lib "eagle-import") (part "RESISTOR0402-RES"))
    )
    (comp (ref "C20")
      (value "1uF")
      (footprint "eagle-import:0402")
      (fields (field (name "MPN") "C0402C104Z4VAC"))
      (libsource (lib "eagle-import") (part "CAP_0402"))
    )
    (comp (ref "C21")
      (value "4.7uF")
      (footprint "eagle-import:0402-CAP")
      (fields (field (name "MPN") "JMK105BBJ475MV-F"))
      (libsource (lib "eagle-import") (part "CAP0402-CAP"))
    )
    (comp (ref "C26")
      (value "0.1uF")
      (footprint "eagle-import:0402")
      (fields (field (name "MPN") "C0402C104Z4VAC"))
      (libsource (lib "eagle-import") (part "CAP_0402"))
    )
    (comp (ref "C27")
      (value "4.7uF")
      (footprint "eagle-import:0402-CAP")
      (fields (field (name "MPN") "JMK105BBJ475MV-F"))
      (libsource (lib "eagle-import") (part "CAP0402-CAP"))
    )
    (comp (ref "IC4")
      (value "ATECC608B-MAHDA-T")
      (footprint "eagle-import:SON50P300X200X60-9N")
      (fields (field (name "MOUSER_PART_NUMBER") "579-TECC608B-MAHDA-T"))
      (libsource (lib "eagle-import") (part "ATECC608B-MAHDA-T"))
    )
    (comp (ref "IC7")
      (value "MXC4005XC")
      (footprint "eagle-import:MXC4005XC")
      (fields (field (name "MOUSER_PART_NUMBER") "438-MXC4005XC"))
      (libsource (lib "eagle-import") (part "MXC4005XC"))
    )
    (comp (ref "R15")
      (value "2.7K")
      (footprint "eagle-import:0402-RES")
      (fields (field (name "MPN") "AC0402JR-072K7L"))
      (libsource (lib "eagle-import") (part "RESISTOR0402-RES"))
    )
    (comp (ref "R16")
      (value "2.7K")
      (footprint "eagle-import:0402-RES")
      (fields (field (name "MPN") "AC0402JR-072K7L"))
      (libsource (lib "eagle-import") (part "RESISTOR0402-RES"))
    )
    (comp (ref "R17")
      (value "2.7K")
      (footprint "eagle-import:0402-RES")
      (fields (field (name "MPN") "AC0402JR-072K7L"))
      (libsource (lib "eagle-import") (part "RESISTOR0402-RES"))
    )
    (comp (ref "C22")
      (value "0.1uF")
      (footprint "eagle-import:0402")
      (fields (field (name "MPN") "C0402C104Z4VAC"))
      (libsource (lib "eagle-import") (part "CAP_0402"))
    )
    (comp (ref "C23")
      (value "4.7uF")
      (footprint "eagle-import:0402-CAP")
      (fields (field (name "MPN") "JMK105BBJ475MV-F"))
      (libsource (lib "eagle-import") (part "CAP0402-CAP"))
    )
    (comp (ref "IC5")
      (value "IS25LP064D-JKLE-TR")
      (footprint "eagle-import:SON127P500X595X80-9N")
      (fields (field (name "MOUSER_PART_NUMBER") "870-5LP064D-JKLE-TR"))
      (libsource (lib "eagle-import") (part "IS25LP064D-JKLE-TR"))
    )
    (comp (ref "R13")
      (value "100K")
      (footprint "eagle-import:0402-RES")
      (fields (field (name "MPN") "AC0402FR-07100KL"))
      (libsource (lib "eagle-import") (part "RESISTOR0402-RES"))
    )
    (comp (ref "C8")
      (value "4.7uF")
      (footprint "eagle-import:0402-CAP")
      (fields (field (name "MPN") "JMK105BBJ475MV-F"))
      (libsource (lib "eagle-import") (part "CAP0402-CAP"))
    )
    (comp (ref "C9")
      (value "4.7uF")
      (footprint "eagle-import:0402-CAP")
      (fields (field (name "MPN") "JMK105BBJ475MV-F"))
      (libsource (lib "eagle-import") (part "CAP0402-CAP"))
    )
    (comp (ref "C10")
      (value "4.7uF")
      (footprint "eagle-import:0402-CAP")
      (fields (field (name "MPN") "JMK105BBJ475MV-F"))
      (libsource (lib "eagle-import") (part "CAP0402-CAP"))
    )
    (comp (ref "CN1")
      (value "S2B-PH-K-S(LF)(SN)")
      (footprint "eagle-import:JST-PH-2-THM-RA")
      (libsource (lib "eagle-import") (part "JST_2PIN-THM-RA"))
    )
    (comp (ref "D2")
      (value "CPDQT5V0HE-HF")
      (footprint "eagle-import:CPDQT5V0HEHF")
      (libsource (lib "eagle-import") (part "CPDQT5V0HE-HF"))
    )
    (comp (ref "Q7")
      (value "2N7002KW_R1_00001")
      (footprint "eagle-import:SOT65P210X110-3N")
      (fields (field (name "MOUSER_PART_NUMBER") "241-2N7002KWR100001"))
      (libsource (lib "eagle-import") (part "2N7002KW_R1_00001"))
    )
    (comp (ref "R1")
      (value "1K")
      (footprint "eagle-import:0402-RES")
      (fields (field (name "MPN") "CRCW04021K00FKEDC"))
      (libsource (lib "eagle-import") (part "RESISTOR0402-RES"))
    )
    (comp (ref "R4")
      (value "1K")
      (footprint "eagle-import:0402-RES")
      (fields (field (name "MPN") "CRCW04021K00FKEDC"))
      (libsource (lib "eagle-import") (part "RESISTOR0402-RES"))
    )
    (comp (ref "R9")
      (value "10K")
      (footprint "eagle-import:0402-RES")
      (fields (field (name "MPN") "AC0402FR-1310KL"))
      (libsource (lib "eagle-import") (part "RESISTOR0402-RES"))
    )
    (comp (ref "R10")
      (value "1.1K")
      (footprint "eagle-import:0402-RES")
      (fields (field (name "MPN") "RC0402JR-071K1L"))
      (libsource (lib "eagle-import") (part "RESISTOR0402-RES"))
    )
    (comp (ref "R11")
      (value "46.4K")
      (footprint "eagle-import:0402-RES")
      (fields (field (name "MPN") "WR04X4642FTL"))
      (libsource (lib "eagle-import") (part "RESISTOR0402-RES"))
    )
    (comp (ref "R12")
      (value "8.2K")
      (footprint "eagle-import:0402-RES")
      (fields (field (name "MPN") "CR0402-FX-8201GLF"))
      (libsource (lib "eagle-import") (part "RESISTOR0402-RES"))
    )
    (comp (ref "R14")
      (value "100K")
      (footprint "eagle-import:0402")
      (fields (field (name "MPN") "AC0402FR-07100KL"))
      (libsource (lib "eagle-import") (part "RES_0402"))
    )
    (comp (ref "R59")
      (value "100K")
      (footprint "eagle-import:0402")
      (fields (field (name "MPN") "AC0402FR-07100KL"))
      (libsource (lib "eagle-import") (part "RES_0402"))
    )
    (comp (ref "U2")
      (value "BQ24075RGTR")
      (footprint "eagle-import:QFN50P300X300X100-17N")
      (fields (field (name "MF") "Texas Instruments"))
      (libsource (lib "eagle-import") (part "BQ24075RGTR"))
    )
    (comp (ref "C6")
      (value "22uF")
      (footprint "eagle-import:0805")
      (fields (field (name "MPN") "CL21A226MQQNNNE"))
      (libsource (lib "eagle-import") (part "22UF-0805-6.3V-20%"))
    )
    (comp (ref "C7")
      (value "22uF")
      (footprint "eagle-import:0805")
      (fields (field (name "MPN") "CL21A226MQQNNNE"))
      (libsource (lib "eagle-import") (part "22UF-0805-6.3V-20%"))
    )
    (comp (ref "IC2")
      (value "AP61300Z6-7")
      (footprint "eagle-import:SOTFL50P162X60-6N")
      (fields (field (name "MOUSER_PART_NUMBER") "621-AP61300Z6-7"))
      (libsource (lib "eagle-import") (part "AP61300Z6-7"))
    )
    (comp (ref "L2")
      (value "MAKK2016T1R0M")
      (footprint "eagle-import:INDC2016X100N")
      (fields (field (name "MF") "Taiyo Yuden"))
      (libsource (lib "eagle-import") (part "MAKK2016T1R0M"))
    )
    (comp (ref "Q1")
      (value "2N7002KW_R1_00001")
      (footprint "eagle-import:SOT65P210X110-3N")
      (fields (field (name "MOUSER_PART_NUMBER") "241-2N7002KWR100001"))
      (libsource (lib "eagle-import") (part "2N7002KW_R1_00001"))
    )
    (comp (ref "R2")
      (value "200K")
      (footprint "eagle-import:0402-RES")
      (fields (field (name "MPN") "CRCW0402200KFKEDC"))
      (libsource (lib "eagle-import") (part "RESISTOR0402-RES"))
    )
    (comp (ref "R3")
      (value "100K")
      (footprint "eagle-import:0402-RES")
      (fields (field (name "MPN") "AC0402FR-07100KL"))
      (libsource (lib "eagle-import") (part "RESISTOR0402-RES"))
    )
    (comp (ref "R8")
      (value "44.2K")
      (footprint "eagle-import:0402-RES")
      (fields (field (name "MPN") "AC0402FR-0744K2L"))
      (libsource (lib "eagle-import") (part "RESISTOR0402-RES"))
    )
    (comp (ref "C32")
      (value "22uF")
      (footprint "eagle-import:0805")
      (fields (field (name "MPN") "CL21A226MQQNNNE"))
      (libsource (lib "eagle-import") (part "22UF-0805-6.3V-20%"))
    )
    (comp (ref "C33")
      (value "4.7uF")
      (footprint "eagle-import:0402-CAP")
      (fields (field (name "MPN") "JMK105BBJ475MV-F"))
      (libsource (lib "eagle-import") (part "CAP0402-CAP"))
    )
    (comp (ref "C39")
      (value "4.7uF")
      (footprint "eagle-import:0402-CAP")
      (fields (field (name "MPN") "JMK105BBJ475MV-F"))
      (libsource (lib "eagle-import") (part "CAP0402-CAP"))
    )
    (comp (ref "C40")
      (value "4.7uF")
      (footprint "eagle-import:0402-CAP")
      (fields (field (name "MPN") "JMK105BBJ475MV-F"))
      (libsource (lib "eagle-import") (part "CAP0402-CAP"))
    )
    (comp (ref "C42")
      (value "4.7uF")
      (footprint "eagle-import:0402-CAP")
      (fields (field (name "MPN") "JMK105BBJ475MV-F"))
      (libsource (lib "eagle-import") (part "CAP0402-CAP"))
    )
    (comp (ref "C44")
      (value "4.7uF")
      (footprint "eagle-import:0402-CAP")
      (fields (field (name "MPN") "JMK105BBJ475MV-F"))
      (libsource (lib "eagle-import") (part "CAP0402-CAP"))
    )
    (comp (ref "C51")
      (value "22uF")
      (footprint "eagle-import:0805")
      (fields (field (name "MPN") "CL21A226MQQNNNE"))
      (libsource (lib "eagle-import") (part "22UF-0805-6.3V-20%"))
    )
    (comp (ref "C52")
      (value "4.7uF")
      (footprint "eagle-import:0402-CAP")
      (fields (field (name "MPN") "JMK105BBJ475MV-F"))
      (libsource (lib "eagle-import") (part "CAP0402-CAP"))
    )
    (comp (ref "J4")
      (value "DF12-36-DS")
      (footprint "eagle-import:DF12-36-DS")
      (fields (field (name "MPN") "DF12NB(3.0)-36DS-0.5V(51)"))
      (libsource (lib "eagle-import") (part "DF12-36-DS"))
    )
    (comp (ref "L4")
      (value "100")
      (footprint "eagle-import:C0402")
      (fields (field (name "MPN") "MFBM1V1005-101-R"))
      (libsource (lib "eagle-import") (part "INDUCTOR0402"))
    )
    (comp (ref "Q4")
      (value "2N7002KW_R1_00001")
      (footprint "eagle-import:SOT65P210X110-3N")
      (fields (field (name "MOUSER_PART_NUMBER") "241-2N7002KWR100001"))
      (libsource (lib "eagle-import") (part "2N7002KW_R1_00001"))
    )
    (comp (ref "Q5")
      (value "2N7002KW_R1_00001")
      (footprint "eagle-import:SOT65P210X110-3N")
      (fields (field (name "MOUSER_PART_NUMBER") "241-2N7002KWR100001"))
      (libsource (lib "eagle-import") (part "2N7002KW_R1_00001"))
    )
    (comp (ref "R24")
      (value "100K")
      (footprint "eagle-import:0402-RES")
      (fields (field (name "MPN") "AC0402FR-07100KL"))
      (libsource (lib "eagle-import") (part "RESISTOR0402-RES"))
    )
    (comp (ref "R25")
      (value "100K")
      (footprint "eagle-import:0402-RES")
      (fields (field (name "MPN") "AC0402FR-07100KL"))
      (libsource (lib "eagle-import") (part "RESISTOR0402-RES"))
    )
    (comp (ref "R26")
      (value "1K")
      (footprint "eagle-import:0402-RES")
      (fields (field (name "MPN") "CRCW04021K00FKEDC"))
      (libsource (lib "eagle-import") (part "RESISTOR0402-RES"))
    )
    (comp (ref "R27")
      (value "10K")
      (footprint "eagle-import:0402-RES")
      (fields (field (name "MPN") "AC0402FR-1310KL"))
      (libsource (lib "eagle-import") (part "RESISTOR0402-RES"))
    )
    (comp (ref "R28")
      (value "100K")
      (footprint "eagle-import:0402-RES")
      (fields (field (name "MPN") "AC0402FR-07100KL"))
      (libsource (lib "eagle-import") (part "RESISTOR0402-RES"))
    )
    (comp (ref "R29")
      (value "10K")
      (footprint "eagle-import:0402-RES")
      (fields (field (name "MPN") "AC0402FR-1310KL"))
      (libsource (lib "eagle-import") (part "RESISTOR0402-RES"))
    )
    (comp (ref "R30")
      (value "4.7K")
      (footprint "eagle-import:0402-RES")
      (fields (field (name "MPN") "AC0402FR-074K7L"))
      (libsource (lib "eagle-import") (part "RESISTOR0402-RES"))
    )
    (comp (ref "R31")
      (value "4.7K")
      (footprint "eagle-import:0402-RES")
      (fields (field (name "MPN") "AC0402FR-074K7L"))
      (libsource (lib "eagle-import") (part "RESISTOR0402-RES"))
    )
    (comp (ref "C1")
      (value "4.7uF")
      (footprint "eagle-import:0402-CAP")
      (fields (field (name "MPN") "JMK105BBJ475MV-F"))
      (libsource (lib "eagle-import") (part "CAP0402-CAP"))
    )
    (comp (ref "C2")
      (value "4.7uF")
      (footprint "eagle-import:0402-CAP")
      (fields (field (name "MPN") "JMK105BBJ475MV-F"))
      (libsource (lib "eagle-import") (part "CAP0402-CAP"))
    )
    (comp (ref "IC10")
      (value "TCR2LF33,LM_CT")
      (footprint "eagle-import:TCR2LF33LMCT")
      (fields
        (field (name "MANUFACTURER_PART_NUMBER") "TCR2LF33,LM(CT")
        (field (name "MOUSER_PART_NUMBER") "757-TCR2LF33LMCT")
      )
      (libsource (lib "eagle-import") (part "TCR2LF33,LM_CT"))
    )
    (comp (ref "Q2")
      (value "2N7002KW_R1_00001")
      (footprint "eagle-import:SOT65P210X110-3N")
      (fields (field (name "MOUSER_PART_NUMBER") "241-2N7002KWR100001"))
      (libsource (lib "eagle-import") (part "2N7002KW_R1_00001"))
    )
    (comp (ref "Q3")
      (value "2N7002KW_R1_00001")
      (footprint "eagle-import:SOT65P210X110-3N")
      (fields (field (name "MOUSER_PART_NUMBER") "241-2N7002KWR100001"))
      (libsource (lib "eagle-import") (part "2N7002KW_R1_00001"))
    )
    (comp (ref "R22")
      (value "100K")
      (footprint "eagle-import:0402-RES")
      (fields (field (name "MPN") "AC0402FR-07100KL"))
      (libsource (lib "eagle-import") (part "RESISTOR0402-RES"))
    )
    (comp (ref "R23")
      (value "100K")
      (footprint "eagle-import:0402-RES")
      (fields (field (name "MPN") "AC0402FR-07100KL"))
      (libsource (lib "eagle-import") (part "RESISTOR0402-RES"))
    )
    (comp (ref "D3")
      (value "UHD1110-FKA-CL1A13R3Q1BBQFMF3")
      (footprint "eagle-import:LED_UHD1110-FKA-CL1A13R3Q1BBQFMF3")
      (fields (field (name "MF") "Cree Inc.") (field (name "MPN") "UHD1110-FKA-CL1A13r3q1BBQFMF3"))
      (libsource (lib "eagle-import") (part "UHD1110-FKA-CL1A13R3Q1BBQFMF3"))
    )
    (comp (ref "D4")
      (value "CPDQT5V0HE-HF")
      (footprint "eagle-import:CPDQT5V0HEHF")
      (libsource (lib "eagle-import") (part "CPDQT5V0HE-HF"))
    )
    (comp (ref "D5")
      (value "CPDQT5V0HE-HF")
      (footprint "eagle-import:CPDQT5V0HEHF")
      (libsource (lib "eagle-import") (part "CPDQT5V0HE-HF"))
    )
    (comp (ref "D7")
      (value "CPDQT5V0HE-HF")
      (footprint "eagle-import:CPDQT5V0HEHF")
      (libsource (lib "eagle-import") (part "CPDQT5V0HE-HF"))
    )
    (comp (ref "D8")
      (value "CPDQT5V0HE-HF")
      (footprint "eagle-import:CPDQT5V0HEHF")
      (libsource (lib "eagle-import") (part "CPDQT5V0HE-HF"))
    )
    (comp (ref "FL2")
      (value "EMIF06-1005M12")
      (footprint "eagle-import:SON40P150X250X65-13N")
      (fields (field (name "MOUSER_PART_NUMBER") "511-EMIF06-1005M12"))
      (libsource (lib "eagle-import") (part "EMIF06-1005M12"))
    )
    (comp (ref "FL4")
      (value "EMIF06-1005M12")
      (footprint "eagle-import:SON40P150X250X65-13N")
      (fields (field (name "MOUSER_PART_NUMBER") "511-EMIF06-1005M12"))
      (libsource (lib "eagle-import") (part "EMIF06-1005M12"))
    )
    (comp (ref "J2")
      (value "DNP")
      (footprint "eagle-import:1X08")
      (libsource (lib "eagle-import") (part "CONN_08{dblquote}"))
    )
    (comp (ref "J3")
      (value "DNP")
      (footprint "eagle-import:1X08")
      (libsource (lib "eagle-import") (part "CONN_08{dblquote}"))
    )
    (comp (ref "J6")
      (value "DNP")
      (footprint "eagle-import:1X08")
      (libsource (lib "eagle-import") (part "CONN_08{dblquote}"))
    )
    (comp (ref "R19")
      (value "220")
      (footprint "eagle-import:0402-RES")
      (fields (field (name "MPN") "CRGCQ0402F220R"))
      (libsource (lib "eagle-import") (part "RESISTOR0402-RES"))
    )
    (comp (ref "R20")
      (value "220")
      (footprint "eagle-import:0402-RES")
      (fields (field (name "MPN") "CRGCQ0402F220R"))
      (libsource (lib "eagle-import") (part "RESISTOR0402-RES"))
    )
    (comp (ref "R21")
      (value "220")
      (footprint "eagle-import:0402-RES")
      (fields (field (name "MPN") "CRGCQ0402F220R"))
      (libsource (lib "eagle-import") (part "RESISTOR0402-RES"))
    )
    (comp (ref "R56")
      (value "10K")
      (footprint "eagle-import:0402")
      (fields (field (name "MPN") "AC0402FR-1310KL"))
      (libsource (lib "eagle-import") (part "RES_0402"))
    )
    (comp (ref "R57")
      (value "10K")
      (footprint "eagle-import:0402")
      (fields (field (name "MPN") "AC0402FR-1310KL"))
      (libsource (lib "eagle-import") (part "RES_0402"))
    )
    (comp (ref "R58")
      (value "10K")
      (footprint "eagle-import:0402")
      (fields (field (name "MPN") "AC0402FR-1310KL"))
      (libsource (lib "eagle-import") (part "RES_0402"))
    )
    (comp (ref "C35")
      (value "4.7uF")
      (footprint "eagle-import:0402-CAP")
      (fields (field (name "MPN") "JMK105BBJ475MV-F"))
      (libsource (lib "eagle-import") (part "CAP0402-CAP"))
    )
    (comp (ref "C36")
      (value "0.1uF")
      (footprint "eagle-import:0402")
      (fields (field (name "MPN") "C0402C104Z4VAC"))
      (libsource (lib "eagle-import") (part "CAP_0402"))
    )
    (comp (ref "C37")
      (value "22uF")
      (footprint "eagle-import:0805")
      (fields (field (name "MPN") "CL21A226MQQNNNE"))
      (libsource (lib "eagle-import") (part "22UF-0805-6.3V-20%"))
    )
    (comp (ref "D6")
      (value "CPDQT5V0HE-HF")
      (footprint "eagle-import:CPDQT5V0HEHF")
      (libsource (lib "eagle-import") (part "CPDQT5V0HE-HF"))
    )
    (comp (ref "D9")
      (value "CPDQT5V0HE-HF")
      (footprint "eagle-import:CPDQT5V0HEHF")
      (libsource (lib "eagle-import") (part "CPDQT5V0HE-HF"))
    )
    (comp (ref "FL3")
      (value "EMIF06-1005M12")
      (footprint "eagle-import:SON40P150X250X65-13N")
      (fields (field (name "MOUSER_PART_NUMBER") "511-EMIF06-1005M12"))
      (libsource (lib "eagle-import") (part "EMIF06-1005M12"))
    )
    (comp (ref "J5")
      (value "USD-1040310811")
      (footprint "eagle-import:1040310811")
      (fields (field (name "MPN") "104031-0811"))
      (libsource (lib "eagle-import") (part "USD-1040310811"))
    )
    (comp (ref "R50")
      (value "100K")
      (footprint "eagle-import:0402")
      (fields (field (name "MPN") "AC0402FR-07100KL"))
      (libsource (lib "eagle-import") (part "RES_0402"))
    )
    (comp (ref "R51")
      (value "100K")
      (footprint "eagle-import:0402")
      (fields (field (name "MPN") "AC0402FR-07100KL"))
      (libsource (lib "eagle-import") (part "RES_0402"))
    )
    (comp (ref "R52")
      (value "100K")
      (footprint "eagle-import:0402")
      (fields (field (name "MPN") "AC0402FR-07100KL"))
      (libsource (lib "eagle-import") (part "RES_0402"))
    )
    (comp (ref "R53")
      (value "100K")
      (footprint "eagle-import:0402")
      (fields (field (name "MPN") "AC0402FR-07100KL"))
      (libsource (lib "eagle-import") (part "RES_0402"))
    )
    (comp (ref "R54")
      (value "100K")
      (footprint "eagle-import:0402")
      (fields (field (name "MPN") "AC0402FR-07100KL"))
      (libsource (lib "eagle-import") (part "RES_0402"))
    )
    (comp (ref "R55")
      (value "100K")
      (footprint "eagle-import:0402")
      (fields (field (name "MPN") "AC0402FR-07100KL"))
      (libsource (lib "eagle-import") (part "RES_0402"))
    )
  )
  (nets
    (net (code "1") (name "BT_D_WAKE") (class "Default")
      (node (ref "IC8") (pin "L5") (pinfunction "GPIO_SD_B1_00_L5") (pintype "bidirectional"))
      (node (ref "U3") (pin "39") (pinfunction "BT_DEV_WAKE_39") (pintype "bidirectional"))
    )
    (net (code "2") (name "BT_H_WAKE") (class "Default")
      (node (ref "IC8") (pin "H14") (pinfunction "GPIO_AD_B0_14_H14") (pintype "bidirectional"))
      (node (ref "R44") (pin "1") (pinfunction "1_1") (pintype "passive"))
      (node (ref "U3") (pin "38") (pinfunction "BT_HOST_WAKE_38") (pintype "bidirectional"))
    )
    (net (code "3") (name "BT_REG_ON") (class "Default")
      (node (ref "IC8") (pin "F13") (pinfunction "GPIO_AD_B0_08_F13") (pintype "bidirectional"))
      (node (ref "R37") (pin "1") (pinfunction "1_1") (pintype "passive"))
      (node (ref "U3") (pin "14") (pinfunction "BT_REG_ON_14") (pintype "input"))
    )
    (net (code "4") (name "BT_UART_CTS") (class "Default")
      (node (ref "IC8") (pin "L12") (pinfunction "GPIO_AD_B1_04_L12") (pintype "bidirectional"))
      (node (ref "U3") (pin "5") (pinfunction "~{BT_UART_RTS_N}_5") (pintype "output"))
    )
    (net (code "5") (name "BT_UART_RTS") (class "Default")
      (node (ref "IC8") (pin "K12") (pinfunction "GPIO_AD_B1_05_K12") (pintype "bidirectional"))
      (node (ref "U3") (pin "4") (pinfunction "~{BT_UART_CTS_N}_4") (pintype "input"))
    )
    (net (code "6") (name "BT_UART_RX") (class "Default")
      (node (ref "IC8") (pin "C9") (pinfunction "GPIO_B0_09_C9") (pintype "bidirectional"))
      (node (ref "U3") (pin "3") (pinfunction "BT_UART_TXD_3") (pintype "output"))
    )
    (net (code "7") (name "BT_UART_TX") (class "Default")
      (node (ref "IC8") (pin "B9") (pinfunction "GPIO_B0_08_B9") (pintype "bidirectional"))
      (node (ref "U3") (pin "2") (pinfunction "BT_UART_RXD_2") (pintype "input"))
    )
    (net (code "8") (name "DCDC_LP") (class "Default")
      (node (ref "IC8") (pin "M1") (pinfunction "DCDC_LP_1_M1") (pintype "bidirectional"))
      (node (ref "IC8") (pin "M2") (pinfunction "DCDC_LP_2_M2") (pintype "bidirectional"))
      (node (ref "L5") (pin "2") (pinfunction "2_2") (pintype "passive"))
    )
    (net (code "9") (name "DCDC_PSWITCH") (class "Default")
      (node (ref "C62") (pin "1") (pinfunction "1_1") (pintype "passive"))
      (node (ref "IC8") (pin "K3") (pinfunction "DCDC_PSWITCH_K3") (pintype "bidirectional"))
      (node (ref "R32") (pin "1") (pinfunction "1_1") (pintype "passive"))
    )
    (net (code "10") (name "DCMI_CLK") (class "Default")
      (node (ref "IC8") (pin "B14") (pinfunction "GPIO_B1_15_B14") (pintype "bidirectional"))
      (node (ref "J4") (pin "12") (pinfunction "12_12") (pintype "bidirectional"))
    )
    (net (code "11") (name "DCMI_D0") (class "Default")
      (node (ref "IC8") (pin "J14") (pinfunction "GPIO_AD_B1_15_J14") (pintype "bidirectional"))
      (node (ref "J4") (pin "31") (pinfunction "31_31") (pintype "bidirectional"))
    )
    (net (code "12") (name "DCMI_D1") (class "Default")
      (node (ref "IC8") (pin "G12") (pinfunction "GPIO_AD_B1_14_G12") (pintype "bidirectional"))
      (node (ref "J4") (pin "29") (pinfunction "29_29") (pintype "bidirectional"))
    )
    (net (code "13") (name "DCMI_D2") (class "Default")
      (node (ref "IC8") (pin "H11") (pinfunction "GPIO_AD_B1_13_H11") (pintype "bidirectional"))
      (node (ref "J4") (pin "35") (pinfunction "35_35") (pintype "bidirectional"))
    )
    (net (code "14") (name "DCMI_D3") (class "Default")
      (node (ref "IC8") (pin "H12") (pinfunction "GPIO_AD_B1_12_H12") (pintype "bidirectional"))
      (node (ref "J4") (pin "28") (pinfunction "28_28") (pintype "bidirectional"))
    )
    (net (code "15") (name "DCMI_D4") (class "Default")
      (node (ref "IC8") (pin "J13") (pinfunction "GPIO_AD_B1_11_J13") (pintype "bidirectional"))
      (node (ref "J4") (pin "26") (pinfunction "26_26") (pintype "bidirectional"))
    )
    (net (code "16") (name "DCMI_D5") (class "Default")
      (node (ref "IC8") (pin "L13") (pinfunction "GPIO_AD_B1_10_L13") (pintype "bidirectional"))
      (node (ref "J4") (pin "33") (pinfunction "33_33") (pintype "bidirectional"))
    )
    (net (code "17") (name "DCMI_D6") (class "Default")
      (node (ref "IC8") (pin "G14") (pinfunction "GPIO_AD_B0_05_G14") (pintype "bidirectional"))
      (node (ref "J4") (pin "24") (pinfunction "24_24") (pintype "bidirectional"))
    )
    (net (code "18") (name "DCMI_D7") (class "Default")
      (node (ref "IC8") (pin "F11") (pinfunction "GPIO_AD_B0_04_F11") (pintype "bidirectional"))
      (node (ref "J4") (pin "22") (pinfunction "22_22") (pintype "bidirectional"))
      (node (ref "S1") (pin "1") (pinfunction "NO_1_1") (pintype "bidirectional"))
      (node (ref "S1") (pin "5") (pinfunction "NO_2_5") (pintype "bidirectional"))
    )
    (net (code "19") (name "DCMI_FSIN") (class "Default")
      (node (ref "J4") (pin "23") (pinfunction "23_23") (pintype "bidirectional"))
      (node (ref "Q5") (pin "3") (pinfunction "D_3") (pintype "bidirectional"))
      (node (ref "R28") (pin "1") (pinfunction "1_1") (pintype "passive"))
    )
    (net (code "20") (name "DCMI_HSYNC") (class "Default")
      (node (ref "IC8") (pin "L10") (pinfunction "GPIO_AD_B0_15_L10") (pintype "bidirectional"))
      (node (ref "J4") (pin "18") (pinfunction "18_18") (pintype "bidirectional"))
    )
    (net (code "21") (name "DCMI_MISO") (class "Default")
      (node (ref "IC8") (pin "E7") (pinfunction "GPIO_B0_01_E7") (pintype "bidirectional"))
      (node (ref "J4") (pin "15") (pinfunction "15_15") (pintype "bidirectional"))
    )
    (net (code "22") (name "DCMI_MOSI") (class "Default")
      (node (ref "IC8") (pin "E8") (pinfunction "GPIO_B0_02_E8") (pintype "bidirectional"))
      (node (ref "J4") (pin "17") (pinfunction "17_17") (pintype "bidirectional"))
    )
    (net (code "23") (name "DCMI_PCLK") (class "Default")
      (node (ref "IC8") (pin "D13") (pinfunction "GPIO_B1_12_D13") (pintype "bidirectional"))
      (node (ref "J4") (pin "14") (pinfunction "14_14") (pintype "bidirectional"))
    )
    (net (code "24") (name "DCMI_PWDN") (class "Default")
      (node (ref "IC8") (pin "C11") (pinfunction "GPIO_B1_02_C11") (pintype "bidirectional"))
      (node (ref "J4") (pin "25") (pinfunction "25_25") (pintype "bidirectional"))
      (node (ref "R29") (pin "1") (pinfunction "1_1") (pintype "passive"))
    )
    (net (code "25") (name "DCMI_RST") (class "Default")
      (node (ref "IC8") (pin "B11") (pinfunction "GPIO_B1_01_B11") (pintype "bidirectional"))
      (node (ref "J4") (pin "21") (pinfunction "21_21") (pintype "bidirectional"))
      (node (ref "R27") (pin "1") (pinfunction "1_1") (pintype "passive"))
    )
    (net (code "26") (name "DCMI_SCL") (class "Default")
      (node (ref "IC8") (pin "J11") (pinfunction "GPIO_AD_B1_00_J11") (pintype "bidirectional"))
      (node (ref "J4") (pin "32") (pinfunction "32_32") (pintype "bidirectional"))
      (node (ref "R30") (pin "1") (pinfunction "1_1") (pintype "passive"))
    )
    (net (code "27") (name "DCMI_SCLK") (class "Default")
      (node (ref "IC8") (pin "D8") (pinfunction "GPIO_B0_03_D8") (pintype "bidirectional"))
      (node (ref "J4") (pin "13") (pinfunction "13_13") (pintype "bidirectional"))
    )
    (net (code "28") (name "DCMI_SDA") (class "Default")
      (node (ref "IC8") (pin "K11") (pinfunction "GPIO_AD_B1_01_K11") (pintype "bidirectional"))
      (node (ref "J4") (pin "34") (pinfunction "34_34") (pintype "bidirectional"))
      (node (ref "R31") (pin "1") (pinfunction "1_1") (pintype "passive"))
    )
    (net (code "29") (name "DCMI_SSEL") (class "Default")
      (node (ref "IC8") (pin "D7") (pinfunction "GPIO_B0_00_D7") (pintype "bidirectional"))
      (node (ref "J4") (pin "11") (pinfunction "11_11") (pintype "bidirectional"))
      (node (ref "R24") (pin "1") (pinfunction "1_1") (pintype "passive"))
    )
    (net (code "30") (name "DCMI_VSYNC") (class "Default")
      (node (ref "IC8") (pin "D14") (pinfunction "GPIO_B1_13_D14") (pintype "bidirectional"))
      (node (ref "J4") (pin "16") (pinfunction "16_16") (pintype "bidirectional"))
    )
    (net (code "31") (name "ETH_INT") (class "Default")
      (node (ref "IC8") (pin "C10") (pinfunction "GPIO_B0_12_C10") (pintype "bidirectional"))
      (node (ref "IC9") (pin "18") (pinfunction "INTRP_18") (pintype "bidirectional"))
      (node (ref "R36") (pin "1") (pinfunction "1_1") (pintype "passive"))
    )
    (net (code "32") (name "ETH_MDC") (class "Default")
      (node (ref "IC8") (pin "A7") (pinfunction "GPIO_EMC_40_A7") (pintype "bidirectional"))
      (node (ref "IC9") (pin "11") (pinfunction "MDC_11") (pintype "bidirectional"))
    )
    (net (code "33") (name "ETH_MDIO") (class "Default")
      (node (ref "IC8") (pin "C7") (pinfunction "GPIO_EMC_41_C7") (pintype "bidirectional"))
      (node (ref "IC9") (pin "10") (pinfunction "MDIO_10") (pintype "bidirectional"))
      (node (ref "R39") (pin "1") (pinfunction "1_1") (pintype "passive"))
    )
    (net (code "34") (name "ETH_RST") (class "Default")
      (node (ref "C65") (pin "2") (pinfunction "2_2") (pintype "passive"))
      (node (ref "IC8") (pin "D10") (pinfunction "GPIO_B0_13_D10") (pintype "bidirectional"))
      (node (ref "IC9") (pin "24") (pinfunction "RST#_24") (pintype "bidirectional"))
      (node (ref "R34") (pin "1") (pinfunction "1_1") (pintype "passive"))
    )
    (net (code "35") (name "ETH_RXD0") (class "Default")
      (node (ref "IC8") (pin "E12") (pinfunction "GPIO_B1_04_E12") (pintype "bidirectional"))
      (node (ref "IC9") (pin "13") (pinfunction "RXD0_13") (pintype "bidirectional"))
    )
    (net (code "36") (name "ETH_RXD1") (class "Default")
      (node (ref "IC8") (pin "D12") (pinfunction "GPIO_B1_05_D12") (pintype "bidirectional"))
      (node (ref "IC9") (pin "12") (pinfunction "RXD1_12") (pintype "bidirectional"))
    )
    (net (code "37") (name "ETH_RXDV") (class "Default")
      (node (ref "IC8") (pin "C12") (pinfunction "GPIO_B1_06_C12") (pintype "bidirectional"))
      (node (ref "IC9") (pin "15") (pinfunction "CRS_DV/_PHYAD[1:0]_15") (pintype "bidirectional"))
    )
    (net (code "38") (name "ETH_RXERR") (class "Default")
      (node (ref "IC8") (pin "C13") (pinfunction "GPIO_B1_11_C13") (pintype "bidirectional"))
      (node (ref "IC9") (pin "17") (pinfunction "RXER_17") (pintype "bidirectional"))
    )
    (net (code "39") (name "ETH_TXCLK") (class "Default")
      (node (ref "IC8") (pin "B13") (pinfunction "GPIO_B1_10_B13") (pintype "bidirectional"))
      (node (ref "IC9") (pin "8") (pinfunction "XI_8") (pintype "bidirectional"))
    )
    (net (code "40") (name "ETH_TXD0") (class "Default")
      (node (ref "IC8") (pin "B12") (pinfunction "GPIO_B1_07_B12") (pintype "bidirectional"))
      (node (ref "IC9") (pin "20") (pinfunction "TXD0_20") (pintype "bidirectional"))
    )
    (net (code "41") (name "ETH_TXD1") (class "Default")
      (node (ref "IC8") (pin "A12") (pinfunction "GPIO_B1_08_A12") (pintype "bidirectional"))
      (node (ref "IC9") (pin "21") (pinfunction "TXD1_21") (pintype "bidirectional"))
    )
    (net (code "42") (name "ETH_TXEN") (class "Default")
      (node (ref "IC8") (pin "A13") (pinfunction "GPIO_B1_09_A13") (pintype "bidirectional"))
      (node (ref "IC9") (pin "19") (pinfunction "TXEN_19") (pintype "bidirectional"))
    )
    (net (code "43") (name "GND") (class "Default")
      (node (ref "C1") (pin "1") (pinfunction "1_1") (pintype "passive"))
      (node (ref "C10") (pin "1") (pinfunction "1_1") (pintype "passive"))
      (node (ref "C100") (pin "1") (pinfunction "1_1") (pintype "passive"))
      (node (ref "C101") (pin "1") (pinfunction "1_1") (pintype "passive"))
      (node (ref "C102") (pin "2") (pinfunction "2_2") (pintype "passive"))
      (node (ref "C103") (pin "1") (pinfunction "1_1") (pintype "passive"))
      (node (ref "C104") (pin "1") (pinfunction "1_1") (pintype "passive"))
      (node (ref "C105") (pin "2") (pinfunction "2_2") (pintype "passive"))
      (node (ref "C106") (pin "2") (pinfunction "2_2") (pintype "passive"))
      (node (ref "C107") (pin "2") (pinfunction "2_2") (pintype "passive"))
      (node (ref "C108") (pin "1") (pinfunction "1_1") (pintype "passive"))
      (node (ref "C109") (pin "2") (pinfunction "2_2") (pintype "passive"))
      (node (ref "C11") (pin "1") (pinfunction "1_1") (pintype "passive"))
      (node (ref "C110") (pin "1") (pinfunction "1_1") (pintype "passive"))
      (node (ref "C111") (pin "2") (pinfunction "2_2") (pintype "passive"))
      (node (ref "C12") (pin "2") (pinfunction "2_2") (pintype "passive"))
      (node (ref "C13") (pin "2") (pinfunction "2_2") (pintype "passive"))
      (node (ref "C14") (pin "2") (pinfunction "2_2") (pintype "passive"))
      (node (ref "C15") (pin "2") (pinfunction "2_2") (pintype "passive"))
      (node (ref "C16") (pin "2") (pinfunction "2_2") (pintype "passive"))
      (node (ref "C17") (pin "1") (pinfunction "1_1") (pintype "passive"))
      (node (ref "C18") (pin "1") (pinfunction "1_1") (pintype "passive"))
      (node (ref "C19") (pin "2") (pinfunction "2_2") (pintype "passive"))
      (node (ref "C2") (pin "1") (pinfunction "1_1") (pintype "passive"))
      (node (ref "C20") (pin "2") (pinfunction "2_2") (pintype "passive"))
      (node (ref "C21") (pin "1") (pinfunction "1_1") (pintype "passive"))
      (node (ref "C22") (pin "2") (pinfunction "2_2") (pintype "passive"))
      (node (ref "C23") (pin "1") (pinfunction "1_1") (pintype "passive"))
      (node (ref "C26") (pin "2") (pinfunction "2_2") (pintype "passive"))
      (node (ref "C27") (pin "1") (pinfunction "1_1") (pintype "passive"))
      (node (ref "C28") (pin "2") (pinfunction "2_2") (pintype "passive"))
      (node (ref "C29") (pin "2") (pinfunction "2_2") (pintype "passive"))
      (node (ref "C3") (pin "1") (pinfunction "1_1") (pintype "passive"))
      (node (ref "C30") (pin "2") (pinfunction "2_2") (pintype "passive"))
      (node (ref "C31") (pin "1") (pinfunction "1_1") (pintype "passive"))
      (node (ref "C32") (pin "2") (pinfunction "2_2") (pintype "passive"))
      (node (ref "C33") (pin "1") (pinfunction "1_1") (pintype "passive"))
      (node (ref "C34") (pin "2") (pinfunction "2_2") (pintype "passive"))
      (node (ref "C35") (pin "1") (pinfunction "1_1") (pintype "passive"))
      (node (ref "C36") (pin "2") (pinfunction "2_2") (pintype "passive"))
      (node (ref "C37") (pin "2") (pinfunction "2_2") (pintype "passive"))
      (node (ref "C38") (pin "2") (pinfunction "2_2") (pintype "passive"))
      (node (ref "C39") (pin "1") (pinfunction "1_1") (pintype "passive"))
      (node (ref "C4") (pin "1") (pinfunction "1_1") (pintype "passive"))
      (node (ref "C40") (pin "1") (pinfunction "1_1") (pintype "passive"))
      (node (ref "C41") (pin "1") (pinfunction "1_1") (pintype "passive"))
      (node (ref "C42") (pin "1") (pinfunction "1_1") (pintype "passive"))
      (node (ref "C43") (pin "2") (pinfunction "2_2") (pintype "passive"))
      (node (ref "C44") (pin "1") (pinfunction "1_1") (pintype "passive"))
      (node (ref "C45") (pin "2") (pinfunction "2_2") (pintype "passive"))
      (node (ref "C46") (pin "1") (pinfunction "1_1") (pintype "passive"))
      (node (ref "C47") (pin "2") (pinfunction "2_2") (pintype "passive"))
      (node (ref "C48") (pin "2") (pinfunction "2_2") (pintype "passive"))
      (node (ref "C49") (pin "1") (pinfunction "1_1") (pintype "passive"))
      (node (ref "C5") (pin "1") (pinfunction "1_1") (pintype "passive"))
      (node (ref "C50") (pin "2") (pinfunction "2_2") (pintype "passive"))
      (node (ref "C51") (pin "2") (pinfunction "2_2") (pintype "passive"))
      (node (ref "C52") (pin "1") (pinfunction "1_1") (pintype "passive"))
      (node (ref "C53") (pin "2") (pinfunction "2_2") (pintype "passive"))
      (node (ref "C54") (pin "2") (pinfunction "2_2") (pintype "passive"))
      (node (ref "C55") (pin "2") (pinfunction "2_2") (pintype "passive"))
      (node (ref "C56") (pin "2") (pinfunction "2_2") (pintype "passive"))
      (node (ref "C57") (pin "1") (pinfunction "1_1") (pintype "passive"))
      (node (ref "C58") (pin "1") (pinfunction "1_1") (pintype "passive"))
      (node (ref "C59") (pin "2") (pinfunction "2_2") (pintype "passive"))
      (node (ref "C6") (pin "2") (pinfunction "2_2") (pintype "passive"))
      (node (ref "C60") (pin "1") (pinfunction "1_1") (pintype "passive"))
      (node (ref "C61") (pin "1") (pinfunction "1_1") (pintype "passive"))
      (node (ref "C62") (pin "2") (pinfunction "2_2") (pintype "passive"))
      (node (ref "C63") (pin "2") (pinfunction "2_2") (pintype "passive"))
      (node (ref "C64") (pin "2") (pinfunction "2_2") (pintype "passive"))
      (node (ref "C65") (pin "1") (pinfunction "1_1") (pintype "passive"))
      (node (ref "C66") (pin "1") (pinfunction "1_1") (pintype "passive"))
      (node (ref "C67") (pin "2") (pinfunction "2_2") (pintype "passive"))
      (node (ref "C68") (pin "1") (pinfunction "1_1") (pintype "passive"))
      (node (ref "C69") (pin "2") (pinfunction "2_2") (pintype "passive"))
      (node (ref "C7") (pin "2") (pinfunction "2_2") (pintype "passive"))
      (node (ref "C70") (pin "2") (pinfunction "2_2") (pintype "passive"))
      (node (ref "C71") (pin "2") (pinfunction "2_2") (pintype "passive"))
      (node (ref "C72") (pin "1") (pinfunction "1_1") (pintype "passive"))
      (node (ref "C73") (pin "1") (pinfunction "1_1") (pintype "passive"))
      (node (ref "C74") (pin "2") (pinfunction "2_2") (pintype "passive"))
      (node (ref "C75") (pin "2") (pinfunction "2_2") (pintype "passive"))
      (node (ref "C76") (pin "2") (pinfunction "2_2") (pintype "passive"))
      (node (ref "C77") (pin "2") (pinfunction "2_2") (pintype "bidirectional"))
      (node (ref "C78") (pin "2") (pinfunction "2_2") (pintype "bidirectional"))
      (node (ref "C79") (pin "2") (pinfunction "2_2") (pintype "passive"))
      (node (ref "C8") (pin "1") (pinfunction "1_1") (pintype "passive"))
      (node (ref "C80") (pin "2") (pinfunction "2_2") (pintype "passive"))
      (node (ref "C81") (pin "1") (pinfunction "1_1") (pintype "passive"))
      (node (ref "C82") (pin "2") (pinfunction "2_2") (pintype "passive"))
      (node (ref "C83") (pin "1") (pinfunction "1_1") (pintype "passive"))
      (node (ref "C84") (pin "2") (pinfunction "2_2") (pintype "passive"))
      (node (ref "C85") (pin "2") (pinfunction "2_2") (pintype "passive"))
      (node (ref "C86") (pin "1") (pinfunction "1_1") (pintype "passive"))
      (node (ref "C87") (pin "1") (pinfunction "1_1") (pintype "passive"))
      (node (ref "C88") (pin "2") (pinfunction "2_2") (pintype "passive"))
      (node (ref "C89") (pin "2") (pinfunction "2_2") (pintype "passive"))
      (node (ref "C9") (pin "1") (pinfunction "1_1") (pintype "passive"))
      (node (ref "C90") (pin "1") (pinfunction "1_1") (pintype "passive"))
      (node (ref "C91") (pin "1") (pinfunction "1_1") (pintype "passive"))
      (node (ref "C92") (pin "1") (pinfunction "1_1") (pintype "passive"))
      (node (ref "C93") (pin "1") (pinfunction "1_1") (pintype "passive"))
      (node (ref "C94") (pin "1") (pinfunction "1_1") (pintype "passive"))
      (node (ref "C95") (pin "1") (pinfunction "1_1") (pintype "passive"))
      (node (ref "C96") (pin "2") (pinfunction "2_2") (pintype "passive"))
      (node (ref "C97") (pin "1") (pinfunction "1_1") (pintype "passive"))
      (node (ref "C98") (pin "1") (pinfunction "1_1") (pintype "passive"))
      (node (ref "C99") (pin "1") (pinfunction "1_1") (pintype "passive"))
      (node (ref "CN1") (pin "2") (pinfunction "1_2") (pintype "passive"))
      (node (ref "D10") (pin "2") (pinfunction "2_2") (pintype "bidirectional"))
      (node (ref "D2") (pin "2") (pinfunction "2_2") (pintype "bidirectional"))
      (node (ref "D4") (pin "2") (pinfunction "2_2") (pintype "bidirectional"))
      (node (ref "D5") (pin "2") (pinfunction "2_2") (pintype "bidirectional"))
      (node (ref "D6") (pin "2") (pinfunction "2_2") (pintype "bidirectional"))
      (node (ref "D7") (pin "2") (pinfunction "2_2") (pintype "bidirectional"))
      (node (ref "D8") (pin "2") (pinfunction "2_2") (pintype "bidirectional"))
      (node (ref "D9") (pin "2") (pinfunction "2_2") (pintype "bidirectional"))
      (node (ref "FL1") (pin "5") (pinfunction "GND_1_5") (pintype "bidirectional"))
      (node (ref "FL1") (pin "8") (pinfunction "GND_2_8") (pintype "bidirectional"))
      (node (ref "FL2") (pin "13") (pinfunction "EP_13") (pintype "bidirectional"))
      (node (ref "FL3") (pin "13") (pinfunction "EP_13") (pintype "bidirectional"))
      (node (ref "FL4") (pin "13") (pinfunction "EP_13") (pintype "bidirectional"))
      (node (ref "FL5") (pin "13") (pinfunction "EP_13") (pintype "bidirectional"))
      (node (ref "IC1") (pin "1") (pinfunction "GND_1_1") (pintype "bidirectional"))
      (node (ref "IC1") (pin "4") (pinfunction "~{ON}_4") (pintype "bidirectional"))
      (node (ref "IC1") (pin "5") (pinfunction "GND_2_5") (pintype "bidirectional"))
      (node (ref "IC10") (pin "2") (pinfunction "GND_2") (pintype "bidirectional"))
      (node (ref "IC2") (pin "2") (pinfunction "GND_2") (pintype "bidirectional"))
      (node (ref "IC3") (pin "A1") (pinfunction "VSS_1_A1") (pintype "bidirectional"))
      (node (ref "IC3") (pin "A3") (pinfunction "VSSQ_1_A3") (pintype "bidirectional"))
      (node (ref "IC3") (pin "B7") (pinfunction "VSSQ_2_B7") (pintype "bidirectional"))
      (node (ref "IC3") (pin "C3") (pinfunction "VSSQ_3_C3") (pintype "bidirectional"))
      (node (ref "IC3") (pin "D7") (pinfunction "VSSQ_4_D7") (pintype "bidirectional"))
      (node (ref "IC3") (pin "E3") (pinfunction "VSS_2_E3") (pintype "bidirectional"))
      (node (ref "IC3") (pin "J1") (pinfunction "VSS_3_J1") (pintype "bidirectional"))
      (node (ref "IC4") (pin "4") (pinfunction "GND_4") (pintype "bidirectional"))
      (node (ref "IC4") (pin "9") (pinfunction "EP_9") (pintype "bidirectional"))
      (node (ref "IC5") (pin "4") (pinfunction "GND_4") (pintype "bidirectional"))
      (node (ref "IC5") (pin "9") (pinfunction "EP_9") (pintype "bidirectional"))
      (node (ref "IC7") (pin "3") (pinfunction "GND_3") (pintype "bidirectional"))
      (node (ref "IC8") (pin "A1") (pinfunction "VSS_1_A1") (pintype "bidirectional"))
      (node (ref "IC8") (pin "A14") (pinfunction "VSS_2_A14") (pintype "bidirectional"))
      (node (ref "IC8") (pin "B10") (pinfunction "VSS_4_B10") (pintype "bidirectional"))
      (node (ref "IC8") (pin "B5") (pinfunction "VSS_3_B5") (pintype "bidirectional"))
      (node (ref "IC8") (pin "E13") (pinfunction "VSS_6_E13") (pintype "bidirectional"))
      (node (ref "IC8") (pin "E2") (pinfunction "VSS_5_E2") (pintype "bidirectional"))
      (node (ref "IC8") (pin "G7") (pinfunction "VSS_7_G7") (pintype "bidirectional"))
      (node (ref "IC8") (pin "G8") (pinfunction "VSS_8_G8") (pintype "bidirectional"))
      (node (ref "IC8") (pin "H7") (pinfunction "VSS_9_H7") (pintype "bidirectional"))
      (node (ref "IC8") (pin "H8") (pinfunction "VSS_10_H8") (pintype "bidirectional"))
      (node (ref "IC8") (pin "J7") (pinfunction "VSS_11_J7") (pintype "bidirectional"))
      (node (ref "IC8") (pin "J8") (pinfunction "VSS_12_J8") (pintype "bidirectional"))
      (node (ref "IC8") (pin "K13") (pinfunction "VSS_14_K13") (pintype "bidirectional"))
      (node (ref "IC8") (pin "K2") (pinfunction "VSS_13_K2") (pintype "bidirectional"))
      (node (ref "IC8") (pin "K6") (pinfunction "TEST_MODE_K6") (pintype "bidirectional"))
      (node (ref "IC8") (pin "K9") (pinfunction "NGND_KEL0_K9") (pintype "bidirectional"))
      (node (ref "IC8") (pin "L9") (pinfunction "VSS_15_L9") (pintype "bidirectional"))
      (node (ref "IC8") (pin "N1") (pinfunction "DCDC_GND_1_N1") (pintype "bidirectional"))
      (node (ref "IC8") (pin "N2") (pinfunction "DCDC_GND_2_N2") (pintype "bidirectional"))
      (node (ref "IC8") (pin "N5") (pinfunction "VSS_16_N5") (pintype "bidirectional"))
      (node (ref "IC8") (pin "N8") (pinfunction "VSS_17_N8") (pintype "bidirectional"))
      (node (ref "IC8") (pin "P1") (pinfunction "VSS_18_P1") (pintype "bidirectional"))
      (node (ref "IC8") (pin "P14") (pinfunction "VSS_19_P14") (pintype "bidirectional"))
      (node (ref "IC9") (pin "22") (pinfunction "GND_1_22") (pintype "bidirectional"))
      (node (ref "IC9") (pin "25") (pinfunction "GND_2_25") (pintype "bidirectional"))
      (node (ref "J1") (pin "A1_B12") (pinfunction "GND_A1_B12") (pintype "power_in"))
      (node (ref "J1") (pin "B1_A12") (pinfunction "GND_B1_A12") (pintype "power_in"))
      (node (ref "J3") (pin "1") (pinfunction "1_1") (pintype "passive"))
      (node (ref "J4") (pin "19") (pinfunction "19_19") (pintype "bidirectional"))
      (node (ref "J4") (pin "27") (pinfunction "27_27") (pintype "bidirectional"))
      (node (ref "J4") (pin "5") (pinfunction "5_5") (pintype "bidirectional"))
      (node (ref "J5") (pin "CD$2") (pinfunction "CD_POL_CD$2") (pintype "power_in"))
      (node (ref "J5") (pin "G$1") (pinfunction "SHD_G$1") (pintype "power_in"))
      (node (ref "J5") (pin "G$2") (pinfunction "SHD_G$2") (pintype "power_in"))
      (node (ref "J5") (pin "G$3") (pinfunction "SHD_G$3") (pintype "power_in"))
      (node (ref "J5") (pin "G$4") (pinfunction "SHD_G$4") (pintype "power_in"))
      (node (ref "J5") (pin "P$6") (pinfunction "VSS_P$6") (pintype "power_in"))
      (node (ref "J6") (pin "1") (pinfunction "1_1") (pintype "passive"))
      (node (ref "J7") (pin "2") (pinfunction "GND_1_2") (pintype "bidirectional"))
      (node (ref "J7") (pin "3") (pinfunction "GND_2_3") (pintype "bidirectional"))
      (node (ref "J8") (pin "3") (pinfunction "3_3") (pintype "passive"))
      (node (ref "J8") (pin "5") (pinfunction "5_5") (pintype "passive"))
      (node (ref "Q6") (pin "1") (pinfunction "G_1") (pintype "bidirectional"))
      (node (ref "R10") (pin "2") (pinfunction "2_2") (pintype "passive"))
      (node (ref "R11") (pin "2") (pinfunction "2_2") (pintype "passive"))
      (node (ref "R12") (pin "2") (pinfunction "2_2") (pintype "passive"))
      (node (ref "R27") (pin "2") (pinfunction "2_2") (pintype "passive"))
      (node (ref "R37") (pin "2") (pinfunction "2_2") (pintype "passive"))
      (node (ref "R38") (pin "2") (pinfunction "2_2") (pintype "passive"))
      (node (ref "R40") (pin "2") (pinfunction "2_2") (pintype "passive"))
      (node (ref "R41") (pin "2") (pinfunction "2_2") (pintype "passive"))
      (node (ref "R6") (pin "2") (pinfunction "2_2") (pintype "passive"))
      (node (ref "R7") (pin "2") (pinfunction "2_2") (pintype "passive"))
      (node (ref "R8") (pin "1") (pinfunction "1_1") (pintype "passive"))
      (node (ref "R9") (pin "2") (pinfunction "2_2") (pintype "passive"))
      (node (ref "U2") (pin "15") (pinfunction "SYSOFF_15") (pintype "input"))
      (node (ref "U2") (pin "17") (pinfunction "EXP_17") (pintype "power_in"))
      (node (ref "U2") (pin "4") (pinfunction "~{CE}_4") (pintype "input"))
      (node (ref "U2") (pin "6") (pinfunction "EN1_6") (pintype "input"))
      (node (ref "U2") (pin "8") (pinfunction "VSS_8") (pintype "power_in"))
      (node (ref "U3") (pin "1") (pinfunction "GND_1") (pintype "power_in"))
      (node (ref "U3") (pin "12") (pinfunction "GND_12") (pintype "power_in"))
      (node (ref "U3") (pin "19") (pinfunction "GND_19") (pintype "power_in"))
      (node (ref "U3") (pin "21") (pinfunction "GND_21") (pintype "power_in"))
      (node (ref "U3") (pin "29") (pinfunction "GND_29") (pintype "power_in"))
      (node (ref "U3") (pin "32") (pinfunction "GND_(SR_PVSS)_32") (pintype "power_in"))
      (node (ref "U3") (pin "33") (pinfunction "GND_(SR_PVSS)_33") (pintype "power_in"))
      (node (ref "U3") (pin "35") (pinfunction "GND_35") (pintype "power_in"))
      (node (ref "U3") (pin "40") (pinfunction "GND_40") (pintype "power_in"))
      (node (ref "U3") (pin "42") (pinfunction "GND_42") (pintype "power_in"))
      (node (ref "U3") (pin "43") (pinfunction "GND_43") (pintype "power_in"))
      (node (ref "U3") (pin "44") (pinfunction "GND_44") (pintype "power_in"))
      (node (ref "U3") (pin "45") (pinfunction "GND_45") (pintype "power_in"))
      (node (ref "U3") (pin "46") (pinfunction "GND_46") (pintype "power_in"))
      (node (ref "Y2") (pin "2") (pinfunction "NC_1_2") (pintype "bidirectional"))
      (node (ref "Y2") (pin "4") (pinfunction "NC_2_4") (pintype "bidirectional"))
      (node (ref "Y3") (pin "2") (pinfunction "GND_2") (pintype "bidirectional"))
    )
    (net (code "44") (name "INT_I2C_INT") (class "Default")
      (node (ref "IC7") (pin "4") (pinfunction "INT_4") (pintype "bidirectional"))
      (node (ref "IC8") (pin "D11") (pinfunction "GPIO_B1_03_D11") (pintype "bidirectional"))
      (node (ref "R17") (pin "1") (pinfunction "1_1") (pintype "passive"))
    )
    (net (code "45") (name "INT_I2C_SCL") (class "Default")
      (node (ref "IC4") (pin "6") (pinfunction "SCL_6") (pintype "bidirectional"))
      (node (ref "IC7") (pin "1") (pinfunction "SCL_1") (pintype "bidirectional"))
      (node (ref "IC8") (pin "C8") (pinfunction "GPIO_B0_04_C8") (pintype "bidirectional"))
      (node (ref "R15") (pin "1") (pinfunction "1_1") (pintype "passive"))
    )
    (net (code "46") (name "INT_I2C_SDA") (class "Default")
      (node (ref "IC4") (pin "5") (pinfunction "SDA_5") (pintype "bidirectional"))
      (node (ref "IC7") (pin "5") (pinfunction "SDA_5") (pintype "bidirectional"))
      (node (ref "IC8") (pin "B8") (pinfunction "GPIO_B0_05_B8") (pintype "bidirectional"))
      (node (ref "R16") (pin "1") (pinfunction "1_1") (pintype "passive"))
    )
    (net (code "47") (name "JTAG_TCK") (class "Default")
      (node (ref "FL5") (pin "4") (pinfunction "INPUT_4_4") (pintype "bidirectional"))
      (node (ref "IC8") (pin "F12") (pinfunction "GPIO_AD_B0_07_F12") (pintype "bidirectional"))
    )
    (net (code "48") (name "JTAG_TCK_INT") (class "Default")
      (node (ref "FL5") (pin "9") (pinfunction "OUTPUT_4_9") (pintype "bidirectional"))
      (node (ref "J8") (pin "4") (pinfunction "4_4") (pintype "passive"))
    )
    (net (code "49") (name "JTAG_TDI") (class "Default")
      (node (ref "FL5") (pin "2") (pinfunction "INPUT_2_2") (pintype "bidirectional"))
      (node (ref "IC8") (pin "F14") (pinfunction "GPIO_AD_B0_09_F14") (pintype "bidirectional"))
    )
    (net (code "50") (name "JTAG_TDI_INT") (class "Default")
      (node (ref "FL5") (pin "11") (pinfunction "OUTPUT_2_11") (pintype "bidirectional"))
      (node (ref "J8") (pin "8") (pinfunction "8_8") (pintype "passive"))
    )
    (net (code "51") (name "JTAG_TDO") (class "Default")
      (node (ref "FL5") (pin "3") (pinfunction "INPUT_3_3") (pintype "bidirectional"))
      (node (ref "IC8") (pin "G13") (pinfunction "GPIO_AD_B0_10_G13") (pintype "bidirectional"))
    )
    (net (code "52") (name "JTAG_TDO_INT") (class "Default")
      (node (ref "FL5") (pin "10") (pinfunction "OUTPUT_3_10") (pintype "bidirectional"))
      (node (ref "J8") (pin "6") (pinfunction "6_6") (pintype "passive"))
    )
    (net (code "53") (name "JTAG_TMS") (class "Default")
      (node (ref "FL5") (pin "5") (pinfunction "INPUT_5_5") (pintype "bidirectional"))
      (node (ref "IC8") (pin "E14") (pinfunction "GPIO_AD_B0_06_E14") (pintype "bidirectional"))
    )
    (net (code "54") (name "JTAG_TMS_INT") (class "Default")
      (node (ref "FL5") (pin "8") (pinfunction "OUTPUT_5_8") (pintype "bidirectional"))
      (node (ref "J8") (pin "2") (pinfunction "2_2") (pintype "passive"))
    )
    (net (code "55") (name "JTAG_TRSTB") (class "Default")
      (node (ref "FL5") (pin "6") (pinfunction "INPUT_6_6") (pintype "bidirectional"))
      (node (ref "IC8") (pin "G10") (pinfunction "GPIO_AD_B0_11_G10") (pintype "bidirectional"))
    )
    (net (code "56") (name "LED_B") (class "Default")
      (node (ref "IC8") (pin "C14") (pinfunction "GPIO_B1_14_C14") (pintype "bidirectional"))
      (node (ref "R19") (pin "1") (pinfunction "1_1") (pintype "passive"))
      (node (ref "R56") (pin "1") (pinfunction "1_1") (pintype "passive"))
    )
    (net (code "57") (name "LED_CHG") (class "Default")
      (node (ref "D1") (pin "3") (pinfunction "RED_3") (pintype "passive"))
      (node (ref "R1") (pin "2") (pinfunction "2_2") (pintype "passive"))
    )
    (net (code "58") (name "LED_G") (class "Default")
      (node (ref "IC8") (pin "A10") (pinfunction "GPIO_B0_11_A10") (pintype "bidirectional"))
      (node (ref "R20") (pin "1") (pinfunction "1_1") (pintype "passive"))
      (node (ref "R57") (pin "1") (pinfunction "1_1") (pintype "passive"))
    )
    (net (code "59") (name "LED_PGOOD") (class "Default")
      (node (ref "D1") (pin "2") (pinfunction "GREEN_2") (pintype "passive"))
      (node (ref "R4") (pin "2") (pinfunction "2_2") (pintype "passive"))
    )
    (net (code "60") (name "LED_R") (class "Default")
      (node (ref "IC8") (pin "D9") (pinfunction "GPIO_B0_10_D9") (pintype "bidirectional"))
      (node (ref "R21") (pin "1") (pinfunction "1_1") (pintype "passive"))
      (node (ref "R58") (pin "1") (pinfunction "1_1") (pintype "passive"))
    )
    (net (code "61") (name "MDI_LED") (class "Default")
      (node (ref "J3") (pin "8") (pinfunction "8_8") (pintype "passive"))
      (node (ref "R35") (pin "2") (pinfunction "2_2") (pintype "passive"))
    )
    (net (code "62") (name "MDI_RX_N") (class "Default")
      (node (ref "IC9") (pin "3") (pinfunction "RXM_3") (pintype "bidirectional"))
      (node (ref "J3") (pin "7") (pinfunction "7_7") (pintype "passive"))
    )
    (net (code "63") (name "MDI_RX_P") (class "Default")
      (node (ref "IC9") (pin "4") (pinfunction "RXP_4") (pintype "bidirectional"))
      (node (ref "J3") (pin "6") (pinfunction "6_6") (pintype "passive"))
    )
    (net (code "64") (name "MDI_TX_N") (class "Default")
      (node (ref "IC9") (pin "5") (pinfunction "TXM_5") (pintype "bidirectional"))
      (node (ref "J3") (pin "5") (pinfunction "5_5") (pintype "passive"))
    )
    (net (code "65") (name "MDI_TX_P") (class "Default")
      (node (ref "IC9") (pin "6") (pinfunction "TXP_6") (pintype "bidirectional"))
      (node (ref "J3") (pin "4") (pinfunction "4_4") (pintype "passive"))
    )
    (net (code "66") (name "NVCC_PLL") (class "Default")
      (node (ref "C104") (pin "2") (pinfunction "2_2") (pintype "passive"))
      (node (ref "C107") (pin "1") (pinfunction "1_1") (pintype "passive"))
      (node (ref "IC8") (pin "P10") (pinfunction "NVCC_PLL_P10") (pintype "bidirectional"))
    )
    (net (code "67") (name "Net-(ANT1-FEED)") (class "Default")
      (node (ref "ANT1") (pin "1") (pinfunction "FEED_1") (pintype "input"))
      (node (ref "C78") (pin "1") (pinfunction "1_1") (pintype "bidirectional"))
      (node (ref "L7") (pin "1") (pinfunction "1_1") (pintype "passive"))
    )
    (net (code "68") (name "Net-(C110-Pad2)") (class "Default")
      (node (ref "C110") (pin "2") (pinfunction "2_2") (pintype "passive"))
      (node (ref "J1") (pin "S1") (pinfunction "SHELL_GND_S1") (pintype "power_in"))
      (node (ref "J1") (pin "S2") (pinfunction "SHELL_GND_S2") (pintype "power_in"))
      (node (ref "J1") (pin "S3") (pinfunction "SHELL_GND_S3") (pintype "power_in"))
      (node (ref "J1") (pin "S4") (pinfunction "SHELL_GND_S4") (pintype "power_in"))
      (node (ref "R41") (pin "1") (pinfunction "1_1") (pintype "passive"))
    )
    (net (code "69") (name "Net-(CN1-2)") (class "Default")
      (node (ref "C8") (pin "2") (pinfunction "2_2") (pintype "passive"))
      (node (ref "CN1") (pin "1") (pinfunction "2_1") (pintype "passive"))
      (node (ref "D2") (pin "1") (pinfunction "1_1") (pintype "bidirectional"))
      (node (ref "U2") (pin "2") (pinfunction "BAT_2_2") (pintype "bidirectional"))
      (node (ref "U2") (pin "3") (pinfunction "BAT_3_3") (pintype "bidirectional"))
    )
    (net (code "70") (name "Net-(D1-BLUE)") (class "Default")
      (node (ref "D1") (pin "1") (pinfunction "BLUE_1") (pintype "passive"))
      (node (ref "R5") (pin "2") (pinfunction "2_2") (pintype "passive"))
    )
    (net (code "71") (name "Net-(D3-BLUE)") (class "Default")
      (node (ref "D3") (pin "1") (pinfunction "BLUE_1") (pintype "passive"))
      (node (ref "R19") (pin "2") (pinfunction "2_2") (pintype "passive"))
    )
    (net (code "72") (name "Net-(D3-GREEN)") (class "Default")
      (node (ref "D3") (pin "2") (pinfunction "GREEN_2") (pintype "passive"))
      (node (ref "R20") (pin "2") (pinfunction "2_2") (pintype "passive"))
    )
    (net (code "73") (name "Net-(D3-RED)") (class "Default")
      (node (ref "D3") (pin "3") (pinfunction "RED_3") (pintype "passive"))
      (node (ref "R21") (pin "2") (pinfunction "2_2") (pintype "passive"))
    )
    (net (code "74") (name "Net-(FL1-D+_1)") (class "Default")
      (node (ref "FL1") (pin "3") (pinfunction "D+_1_3") (pintype "bidirectional"))
      (node (ref "J1") (pin "A7") (pinfunction "DN1_A7") (pintype "bidirectional"))
      (node (ref "J1") (pin "B7") (pinfunction "DN2_B7") (pintype "bidirectional"))
    )
    (net (code "75") (name "Net-(FL1-D-_1)") (class "Default")
      (node (ref "FL1") (pin "2") (pinfunction "D-_1_2") (pintype "bidirectional"))
      (node (ref "J1") (pin "A6") (pinfunction "DP1_A6") (pintype "bidirectional"))
      (node (ref "J1") (pin "B6") (pinfunction "DP2_B6") (pintype "bidirectional"))
    )
    (net (code "76") (name "Net-(FL1-ID)") (class "Default")
      (node (ref "FL1") (pin "4") (pinfunction "ID_4") (pintype "bidirectional"))
      (node (ref "J1") (pin "A4_B9") (pinfunction "VBUS_A4_B9") (pintype "power_in"))
      (node (ref "J1") (pin "B4_A9") (pinfunction "VBUS_B4_A9") (pintype "power_in"))
      (node (ref "L1") (pin "1") (pinfunction "1_1") (pintype "passive"))
    )
    (net (code "77") (name "Net-(FL2-OUTPUT_1)") (class "Default")
      (node (ref "FL2") (pin "12") (pinfunction "OUTPUT_1_12") (pintype "bidirectional"))
      (node (ref "J2") (pin "8") (pinfunction "8_8") (pintype "passive"))
    )
    (net (code "78") (name "Net-(FL2-OUTPUT_2)") (class "Default")
      (node (ref "FL2") (pin "11") (pinfunction "OUTPUT_2_11") (pintype "bidirectional"))
      (node (ref "J2") (pin "7") (pinfunction "7_7") (pintype "passive"))
    )
    (net (code "79") (name "Net-(FL2-OUTPUT_3)") (class "Default")
      (node (ref "FL2") (pin "10") (pinfunction "OUTPUT_3_10") (pintype "bidirectional"))
      (node (ref "J2") (pin "6") (pinfunction "6_6") (pintype "passive"))
    )
    (net (code "80") (name "Net-(FL2-OUTPUT_4)") (class "Default")
      (node (ref "FL2") (pin "9") (pinfunction "OUTPUT_4_9") (pintype "bidirectional"))
      (node (ref "J2") (pin "5") (pinfunction "5_5") (pintype "passive"))
    )
    (net (code "81") (name "Net-(FL2-OUTPUT_5)") (class "Default")
      (node (ref "FL2") (pin "8") (pinfunction "OUTPUT_5_8") (pintype "bidirectional"))
      (node (ref "J2") (pin "4") (pinfunction "4_4") (pintype "passive"))
    )
    (net (code "82") (name "Net-(FL2-OUTPUT_6)") (class "Default")
      (node (ref "FL2") (pin "7") (pinfunction "OUTPUT_6_7") (pintype "bidirectional"))
      (node (ref "J2") (pin "3") (pinfunction "3_3") (pintype "passive"))
    )
    (net (code "83") (name "Net-(FL4-OUTPUT_1)") (class "Default")
      (node (ref "FL4") (pin "12") (pinfunction "OUTPUT_1_12") (pintype "bidirectional"))
      (node (ref "J2") (pin "2") (pinfunction "2_2") (pintype "passive"))
    )
    (net (code "84") (name "Net-(FL5-OUTPUT_6)") (class "Default")
      (node (ref "FL5") (pin "7") (pinfunction "OUTPUT_6_7") (pintype "bidirectional"))
      (node (ref "J8") (pin "9") (pinfunction "9_9") (pintype "passive"))
    )
    (net (code "85") (name "Net-(IC1-ST)") (class "Default")
      (node (ref "IC1") (pin "8") (pinfunction "ST_8") (pintype "bidirectional"))
      (node (ref "R5") (pin "1") (pinfunction "1_1") (pintype "passive"))
    )
    (net (code "86") (name "Net-(IC1-VIN2)") (class "Default")
      (node (ref "C5") (pin "2") (pinfunction "2_2") (pintype "passive"))
      (node (ref "IC1") (pin "6") (pinfunction "VIN2_6") (pintype "bidirectional"))
      (node (ref "Q6") (pin "2") (pinfunction "S_2") (pintype "bidirectional"))
    )
    (net (code "87") (name "Net-(IC2-EN)") (class "Default")
      (node (ref "IC2") (pin "5") (pinfunction "EN_5") (pintype "bidirectional"))
      (node (ref "Q1") (pin "3") (pinfunction "D_3") (pintype "bidirectional"))
      (node (ref "R3") (pin "1") (pinfunction "1_1") (pintype "passive"))
    )
    (net (code "88") (name "Net-(IC2-FB)") (class "Default")
      (node (ref "IC2") (pin "1") (pinfunction "FB_1") (pintype "bidirectional"))
      (node (ref "R2") (pin "1") (pinfunction "1_1") (pintype "passive"))
      (node (ref "R8") (pin "2") (pinfunction "2_2") (pintype "passive"))
    )
    (net (code "89") (name "Net-(IC2-SW)") (class "Default")
      (node (ref "IC2") (pin "4") (pinfunction "SW_4") (pintype "bidirectional"))
      (node (ref "L2") (pin "1") (pinfunction "1_1") (pintype "passive"))
    )
    (net (code "90") (name "Net-(IC9-LED0_{slash}_ANEN_SPEED)") (class "Default")
      (node (ref "IC9") (pin "23") (pinfunction "LED0_/_ANEN_SPEED_23") (pintype "bidirectional"))
      (node (ref "R35") (pin "1") (pinfunction "1_1") (pintype "passive"))
    )
    (net (code "91") (name "Net-(IC9-REXT)") (class "Default")
      (node (ref "IC9") (pin "9") (pinfunction "REXT_9") (pintype "bidirectional"))
      (node (ref "R38") (pin "1") (pinfunction "1_1") (pintype "passive"))
    )
    (net (code "92") (name "Net-(IC9-VDDA_3.3)") (class "Default")
      (node (ref "C81") (pin "2") (pinfunction "2_2") (pintype "passive"))
      (node (ref "C82") (pin "1") (pinfunction "1_1") (pintype "passive"))
      (node (ref "C85") (pin "1") (pinfunction "1_1") (pintype "passive"))
      (node (ref "IC9") (pin "2") (pinfunction "VDDA_3.3_2") (pintype "bidirectional"))
      (node (ref "L8") (pin "1") (pinfunction "1_1") (pintype "passive"))
    )
    (net (code "93") (name "Net-(IC9-VDD_1.2)") (class "Default")
      (node (ref "C83") (pin "2") (pinfunction "2_2") (pintype "passive"))
      (node (ref "C84") (pin "1") (pinfunction "1_1") (pintype "passive"))
      (node (ref "IC9") (pin "1") (pinfunction "VDD_1.2_1") (pintype "bidirectional"))
    )
    (net (code "94") (name "Net-(J1-CC1)") (class "Default")
      (node (ref "J1") (pin "A5") (pinfunction "CC1_A5") (pintype "bidirectional"))
      (node (ref "R6") (pin "1") (pinfunction "1_1") (pintype "passive"))
    )
    (net (code "95") (name "Net-(J1-CC2)") (class "Default")
      (node (ref "J1") (pin "B5") (pinfunction "CC2_B5") (pintype "bidirectional"))
      (node (ref "R7") (pin "1") (pinfunction "1_1") (pintype "passive"))
    )
    (net (code "96") (name "Net-(J7-SIGNAL)") (class "Default")
      (node (ref "C77") (pin "1") (pinfunction "1_1") (pintype "bidirectional"))
      (node (ref "J7") (pin "1") (pinfunction "SIGNAL_1") (pintype "bidirectional"))
      (node (ref "L7") (pin "2") (pinfunction "2_2") (pintype "passive"))
      (node (ref "U3") (pin "41") (pinfunction "ANT_41") (pintype "passive"))
    )
    (net (code "97") (name "Net-(Q7-D)") (class "Default")
      (node (ref "Q7") (pin "3") (pinfunction "D_3") (pintype "bidirectional"))
      (node (ref "R14") (pin "1") (pinfunction "1_1") (pintype "passive"))
      (node (ref "R4") (pin "1") (pinfunction "1_1") (pintype "passive"))
      (node (ref "U2") (pin "7") (pinfunction "~{PGOOD}_7") (pintype "output"))
    )
    (net (code "98") (name "Net-(S1-COM_1)") (class "Default")
      (node (ref "R42") (pin "2") (pinfunction "2_2") (pintype "passive"))
      (node (ref "S1") (pin "2") (pinfunction "COM_1_2") (pintype "bidirectional"))
      (node (ref "S1") (pin "3") (pinfunction "COM_2_3") (pintype "bidirectional"))
      (node (ref "S1") (pin "4") (pinfunction "COM_3_4") (pintype "bidirectional"))
    )
    (net (code "99") (name "Net-(U2-ILIM)") (class "Default")
      (node (ref "R10") (pin "1") (pinfunction "1_1") (pintype "passive"))
      (node (ref "U2") (pin "12") (pinfunction "ILIM_12") (pintype "input"))
    )
    (net (code "100") (name "Net-(U2-ISET)") (class "Default")
      (node (ref "R12") (pin "1") (pinfunction "1_1") (pintype "passive"))
      (node (ref "U2") (pin "16") (pinfunction "ISET_16") (pintype "bidirectional"))
    )
    (net (code "101") (name "Net-(U2-TMR)") (class "Default")
      (node (ref "R11") (pin "1") (pinfunction "1_1") (pintype "passive"))
      (node (ref "U2") (pin "14") (pinfunction "TMR_14") (pintype "input"))
    )
    (net (code "102") (name "Net-(U2-TS)") (class "Default")
      (node (ref "R9") (pin "1") (pinfunction "1_1") (pintype "passive"))
      (node (ref "U2") (pin "1") (pinfunction "TS_1") (pintype "input"))
    )
    (net (code "103") (name "Net-(U2-~{CHG})") (class "Default")
      (node (ref "R1") (pin "1") (pinfunction "1_1") (pintype "passive"))
      (node (ref "U2") (pin "9") (pinfunction "~{CHG}_9") (pintype "output"))
    )
    (net (code "104") (name "Net-(U3-LPO_IN_(32KHZ))") (class "Default")
      (node (ref "U3") (pin "37") (pinfunction "LPO_IN_(32KHZ)_37") (pintype "input"))
      (node (ref "Y3") (pin "3") (pinfunction "OUTPUT_3") (pintype "bidirectional"))
    )
    (net (code "105") (name "Net-(U3-SR_VLX)") (class "Default")
      (node (ref "L9") (pin "1") (pinfunction "1_1") (pintype "passive"))
      (node (ref "U3") (pin "34") (pinfunction "SR_VLX_34") (pintype "output"))
    )
    (net (code "106") (name "Net-(U3-VIN_LDO)") (class "Default")
      (node (ref "C74") (pin "1") (pinfunction "1_1") (pintype "passive"))
      (node (ref "C91") (pin "2") (pinfunction "2_2") (pintype "passive"))
      (node (ref "L9") (pin "2") (pinfunction "2_2") (pintype "passive"))
      (node (ref "U3") (pin "31") (pinfunction "VIN_LDO_31") (pintype "power_in"))
    )
    (net (code "107") (name "ONOFF") (class "Default")
      (node (ref "IC8") (pin "M6") (pinfunction "ONOFF_M6") (pintype "bidirectional"))
      (node (ref "Q3") (pin "2") (pinfunction "S_2") (pintype "bidirectional"))
    )
    (net (code "108") (name "ON_BATTERY") (class "Default")
      (node (ref "IC8") (pin "P2") (pinfunction "GPIO_SD_B1_04_P2") (pintype "bidirectional"))
      (node (ref "Q7") (pin "2") (pinfunction "S_2") (pintype "bidirectional"))
      (node (ref "R59") (pin "1") (pinfunction "1_1") (pintype "passive"))
    )
    (net (code "109") (name "P0_MOSI") (class "Default")
      (node (ref "FL2") (pin "1") (pinfunction "INPUT_1_1") (pintype "bidirectional"))
      (node (ref "IC8") (pin "H10") (pinfunction "GPIO_AD_B0_01_H10") (pintype "bidirectional"))
    )
    (net (code "110") (name "P1_MISO") (class "Default")
      (node (ref "FL2") (pin "2") (pinfunction "INPUT_2_2") (pintype "bidirectional"))
      (node (ref "IC8") (pin "M11") (pinfunction "GPIO_AD_B0_02_M11") (pintype "bidirectional"))
    )
    (net (code "111") (name "P2_SCLK") (class "Default")
      (node (ref "FL2") (pin "3") (pinfunction "INPUT_3_3") (pintype "bidirectional"))
      (node (ref "IC8") (pin "M14") (pinfunction "GPIO_AD_B0_00_M14") (pintype "bidirectional"))
    )
    (net (code "112") (name "P3_NSS") (class "Default")
      (node (ref "FL2") (pin "4") (pinfunction "INPUT_4_4") (pintype "bidirectional"))
      (node (ref "IC8") (pin "G11") (pinfunction "GPIO_AD_B0_03_G11") (pintype "bidirectional"))
    )
    (net (code "113") (name "P4_SCL") (class "Default")
      (node (ref "FL2") (pin "5") (pinfunction "INPUT_5_5") (pintype "bidirectional"))
      (node (ref "IC8") (pin "K14") (pinfunction "GPIO_AD_B0_12_K14") (pintype "bidirectional"))
    )
    (net (code "114") (name "P5_SDA") (class "Default")
      (node (ref "FL2") (pin "6") (pinfunction "INPUT_6_6") (pintype "bidirectional"))
      (node (ref "IC8") (pin "L14") (pinfunction "GPIO_AD_B0_13_L14") (pintype "bidirectional"))
    )
    (net (code "115") (name "P6_ADC") (class "Default")
      (node (ref "FL4") (pin "1") (pinfunction "INPUT_1_1") (pintype "bidirectional"))
      (node (ref "IC8") (pin "M12") (pinfunction "GPIO_AD_B1_03_M12") (pintype "bidirectional"))
    )
    (net (code "116") (name "P7_PWM") (class "Default")
      (node (ref "FL4") (pin "2") (pinfunction "INPUT_2_2") (pintype "bidirectional"))
      (node (ref "IC8") (pin "A8") (pinfunction "GPIO_B0_06_A8") (pintype "bidirectional"))
    )
    (net (code "117") (name "P7_PWM_INT") (class "Default")
      (node (ref "FL4") (pin "11") (pinfunction "OUTPUT_2_11") (pintype "bidirectional"))
      (node (ref "J6") (pin "3") (pinfunction "3_3") (pintype "passive"))
    )
    (net (code "118") (name "P8_PWM") (class "Default")
      (node (ref "FL4") (pin "3") (pinfunction "INPUT_3_3") (pintype "bidirectional"))
      (node (ref "IC8") (pin "A9") (pinfunction "GPIO_B0_07_A9") (pintype "bidirectional"))
    )
    (net (code "119") (name "P8_PWM_INT") (class "Default")
      (node (ref "FL4") (pin "10") (pinfunction "OUTPUT_3_10") (pintype "bidirectional"))
      (node (ref "J6") (pin "4") (pinfunction "4_4") (pintype "passive"))
    )
    (net (code "120") (name "P9_PWM") (class "Default")
      (node (ref "FL4") (pin "4") (pinfunction "INPUT_4_4") (pintype "bidirectional"))
      (node (ref "IC8") (pin "A11") (pinfunction "GPIO_B1_00_A11") (pintype "bidirectional"))
    )
    (net (code "121") (name "P9_PWM_INT") (class "Default")
      (node (ref "FL4") (pin "9") (pinfunction "OUTPUT_4_9") (pintype "bidirectional"))
      (node (ref "J6") (pin "5") (pinfunction "5_5") (pintype "passive"))
    )
    (net (code "122") (name "P10_PWM") (class "Default")
      (node (ref "FL4") (pin "5") (pinfunction "INPUT_5_5") (pintype "bidirectional"))
      (node (ref "Q4") (pin "3") (pinfunction "D_3") (pintype "bidirectional"))
      (node (ref "R26") (pin "1") (pinfunction "1_1") (pintype "passive"))
    )
    (net (code "123") (name "P10_PWM_INT") (class "Default")
      (node (ref "FL4") (pin "8") (pinfunction "OUTPUT_5_8") (pintype "bidirectional"))
      (node (ref "J6") (pin "6") (pinfunction "6_6") (pintype "passive"))
    )
    (net (code "124") (name "P11_WAKEUP") (class "Default")
      (node (ref "FL4") (pin "6") (pinfunction "INPUT_6_6") (pintype "bidirectional"))
      (node (ref "Q2") (pin "3") (pinfunction "D_3") (pintype "bidirectional"))
      (node (ref "R22") (pin "1") (pinfunction "1_1") (pintype "passive"))
    )
    (net (code "125") (name "P11_WAKEUP_INT") (class "Default")
      (node (ref "FL4") (pin "7") (pinfunction "OUTPUT_6_7") (pintype "bidirectional"))
      (node (ref "J6") (pin "7") (pinfunction "7_7") (pintype "passive"))
    )
    (net (code "126") (name "P12_RST_N") (class "Default")
      (node (ref "C63") (pin "1") (pinfunction "1_1") (pintype "passive"))
      (node (ref "FL5") (pin "1") (pinfunction "INPUT_1_1") (pintype "bidirectional"))
      (node (ref "IC8") (pin "M7") (pinfunction "POR_B_M7") (pintype "bidirectional"))
      (node (ref "R33") (pin "2") (pinfunction "2_2") (pintype "passive"))
    )
    (net (code "127") (name "P12_RST_N_EXT") (class "Default")
      (node (ref "FL5") (pin "12") (pinfunction "OUTPUT_1_12") (pintype "bidirectional"))
      (node (ref "J6") (pin "8") (pinfunction "8_8") (pintype "passive"))
      (node (ref "J8") (pin "10") (pinfunction "10_10") (pintype "passive"))
    )
    (net (code "128") (name "PMIC_ONOFF") (class "Default")
      (node (ref "D8") (pin "1") (pinfunction "1_1") (pintype "bidirectional"))
      (node (ref "J3") (pin "3") (pinfunction "3_3") (pintype "passive"))
      (node (ref "Q3") (pin "3") (pinfunction "D_3") (pintype "bidirectional"))
      (node (ref "R23") (pin "1") (pinfunction "1_1") (pintype "passive"))
    )
    (net (code "129") (name "PMIC_ON_REQ") (class "Default")
      (node (ref "IC8") (pin "K7") (pinfunction "PMIC_ON_REQ_K7") (pintype "bidirectional"))
      (node (ref "Q1") (pin "2") (pinfunction "S_2") (pintype "bidirectional"))
    )
    (net (code "130") (name "PWM_FSIN") (class "Default")
      (node (ref "IC8") (pin "M5") (pinfunction "GPIO_SD_B1_01_M5") (pintype "bidirectional"))
      (node (ref "Q4") (pin "2") (pinfunction "S_2") (pintype "bidirectional"))
      (node (ref "Q5") (pin "2") (pinfunction "S_2") (pintype "bidirectional"))
      (node (ref "R25") (pin "1") (pinfunction "1_1") (pintype "passive"))
    )
    (net (code "131") (name "P_FLASH_CE") (class "Default")
      (node (ref "IC5") (pin "1") (pinfunction "CE#_1") (pintype "bidirectional"))
      (node (ref "IC8") (pin "L3") (pinfunction "GPIO_SD_B1_06_L3") (pintype "bidirectional"))
      (node (ref "R13") (pin "2") (pinfunction "2_2") (pintype "passive"))
    )
    (net (code "132") (name "P_FLASH_IO0") (class "Default")
      (node (ref "IC5") (pin "5") (pinfunction "SI_(IO0)_5") (pintype "bidirectional"))
      (node (ref "IC8") (pin "P3") (pinfunction "GPIO_SD_B1_08_P3") (pintype "bidirectional"))
    )
    (net (code "133") (name "P_FLASH_IO1") (class "Default")
      (node (ref "IC5") (pin "2") (pinfunction "SO_(IO1)_2") (pintype "bidirectional"))
      (node (ref "IC8") (pin "N4") (pinfunction "GPIO_SD_B1_09_N4") (pintype "bidirectional"))
    )
    (net (code "134") (name "P_FLASH_IO2") (class "Default")
      (node (ref "IC5") (pin "3") (pinfunction "WP#_(IO2)_3") (pintype "bidirectional"))
      (node (ref "IC8") (pin "P4") (pinfunction "GPIO_SD_B1_10_P4") (pintype "bidirectional"))
    )
    (net (code "135") (name "P_FLASH_IO3") (class "Default")
      (node (ref "IC5") (pin "7") (pinfunction "HOLD#_(IO3)_7") (pintype "bidirectional"))
      (node (ref "IC8") (pin "P5") (pinfunction "GPIO_SD_B1_11_P5") (pintype "bidirectional"))
    )
    (net (code "136") (name "P_FLASH_SCK") (class "Default")
      (node (ref "IC5") (pin "6") (pinfunction "SCK_6") (pintype "bidirectional"))
      (node (ref "IC8") (pin "L4") (pinfunction "GPIO_SD_B1_07_L4") (pintype "bidirectional"))
    )
    (net (code "137") (name "RAW") (class "Default")
      (node (ref "C1") (pin "2") (pinfunction "2_2") (pintype "passive"))
      (node (ref "C10") (pin "2") (pinfunction "2_2") (pintype "passive"))
      (node (ref "C6") (pin "1") (pinfunction "1_1") (pintype "passive"))
      (node (ref "D5") (pin "1") (pinfunction "1_1") (pintype "bidirectional"))
      (node (ref "IC10") (pin "1") (pinfunction "VIN_1") (pintype "bidirectional"))
      (node (ref "IC10") (pin "3") (pinfunction "CONTROL_3") (pintype "bidirectional"))
      (node (ref "IC2") (pin "3") (pinfunction "VIN_3") (pintype "bidirectional"))
      (node (ref "J3") (pin "2") (pinfunction "2_2") (pintype "passive"))
      (node (ref "R14") (pin "2") (pinfunction "2_2") (pintype "passive"))
      (node (ref "R22") (pin "2") (pinfunction "2_2") (pintype "passive"))
      (node (ref "R23") (pin "2") (pinfunction "2_2") (pintype "passive"))
      (node (ref "R3") (pin "2") (pinfunction "2_2") (pintype "passive"))
      (node (ref "U2") (pin "10") (pinfunction "OUT_10_10") (pintype "output"))
      (node (ref "U2") (pin "11") (pinfunction "OUT_11_11") (pintype "output"))
      (node (ref "U2") (pin "5") (pinfunction "EN2_5") (pintype "input"))
    )
    (net (code "138") (name "RTC_XTALI") (class "Default")
      (node (ref "C80") (pin "1") (pinfunction "1_1") (pintype "passive"))
      (node (ref "IC8") (pin "N9") (pinfunction "RTC_XTALI_N9") (pintype "bidirectional"))
      (node (ref "Y1") (pin "2") (pinfunction "2_2") (pintype "passive"))
    )
    (net (code "139") (name "RTC_XTALO") (class "Default")
      (node (ref "C79") (pin "1") (pinfunction "1_1") (pintype "passive"))
      (node (ref "IC8") (pin "P9") (pinfunction "RTC_XTALO_P9") (pintype "bidirectional"))
      (node (ref "Y1") (pin "1") (pinfunction "1_1") (pintype "passive"))
    )
    (net (code "140") (name "SDRAM_A0") (class "Default")
      (node (ref "IC3") (pin "H7") (pinfunction "A0_H7") (pintype "bidirectional"))
      (node (ref "IC8") (pin "C2") (pinfunction "GPIO_EMC_09_C2") (pintype "bidirectional"))
    )
    (net (code "141") (name "SDRAM_A1") (class "Default")
      (node (ref "IC3") (pin "H8") (pinfunction "A1_H8") (pintype "bidirectional"))
      (node (ref "IC8") (pin "G1") (pinfunction "GPIO_EMC_10_G1") (pintype "bidirectional"))
    )
    (net (code "142") (name "SDRAM_A2") (class "Default")
      (node (ref "IC3") (pin "J8") (pinfunction "A2_J8") (pintype "bidirectional"))
      (node (ref "IC8") (pin "G3") (pinfunction "GPIO_EMC_11_G3") (pintype "bidirectional"))
    )
    (net (code "143") (name "SDRAM_A3") (class "Default")
      (node (ref "IC3") (pin "J7") (pinfunction "A3_J7") (pintype "bidirectional"))
      (node (ref "IC8") (pin "H1") (pinfunction "GPIO_EMC_12_H1") (pintype "bidirectional"))
    )
    (net (code "144") (name "SDRAM_A4") (class "Default")
      (node (ref "IC3") (pin "J3") (pinfunction "A4_J3") (pintype "bidirectional"))
      (node (ref "IC8") (pin "A6") (pinfunction "GPIO_EMC_13_A6") (pintype "bidirectional"))
    )
    (net (code "145") (name "SDRAM_A5") (class "Default")
      (node (ref "IC3") (pin "J2") (pinfunction "A5_J2") (pintype "bidirectional"))
      (node (ref "IC8") (pin "B6") (pinfunction "GPIO_EMC_14_B6") (pintype "bidirectional"))
    )
    (net (code "146") (name "SDRAM_A6") (class "Default")
      (node (ref "IC3") (pin "H3") (pinfunction "A6_H3") (pintype "bidirectional"))
      (node (ref "IC8") (pin "B1") (pinfunction "GPIO_EMC_15_B1") (pintype "bidirectional"))
    )
    (net (code "147") (name "SDRAM_A7") (class "Default")
      (node (ref "IC3") (pin "H2") (pinfunction "A7_H2") (pintype "bidirectional"))
      (node (ref "IC8") (pin "A5") (pinfunction "GPIO_EMC_16_A5") (pintype "bidirectional"))
    )
    (net (code "148") (name "SDRAM_A8") (class "Default")
      (node (ref "IC3") (pin "H1") (pinfunction "A8_H1") (pintype "bidirectional"))
      (node (ref "IC8") (pin "A4") (pinfunction "GPIO_EMC_17_A4") (pintype "bidirectional"))
    )
    (net (code "149") (name "SDRAM_A9") (class "Default")
      (node (ref "IC3") (pin "G3") (pinfunction "A9_G3") (pintype "bidirectional"))
      (node (ref "IC8") (pin "B2") (pinfunction "GPIO_EMC_18_B2") (pintype "bidirectional"))
    )
    (net (code "150") (name "SDRAM_A10") (class "Default")
      (node (ref "IC3") (pin "H9") (pinfunction "A10_H9") (pintype "bidirectional"))
      (node (ref "IC8") (pin "G2") (pinfunction "GPIO_EMC_23_G2") (pintype "bidirectional"))
    )
    (net (code "151") (name "SDRAM_A11") (class "Default")
      (node (ref "IC3") (pin "G2") (pinfunction "A11_G2") (pintype "bidirectional"))
      (node (ref "IC8") (pin "B4") (pinfunction "GPIO_EMC_19_B4") (pintype "bidirectional"))
    )
    (net (code "152") (name "SDRAM_A12") (class "Default")
      (node (ref "IC3") (pin "G1") (pinfunction "A12_G1") (pintype "bidirectional"))
      (node (ref "IC8") (pin "A3") (pinfunction "GPIO_EMC_20_A3") (pintype "bidirectional"))
    )
    (net (code "153") (name "SDRAM_BA0") (class "Default")
      (node (ref "IC3") (pin "G7") (pinfunction "BA0_G7") (pintype "bidirectional"))
      (node (ref "IC8") (pin "C1") (pinfunction "GPIO_EMC_21_C1") (pintype "bidirectional"))
    )
    (net (code "154") (name "SDRAM_BA1") (class "Default")
      (node (ref "IC3") (pin "G8") (pinfunction "BA1_G8") (pintype "bidirectional"))
      (node (ref "IC8") (pin "F1") (pinfunction "GPIO_EMC_22_F1") (pintype "bidirectional"))
    )
    (net (code "155") (name "SDRAM_CAS") (class "Default")
      (node (ref "IC3") (pin "F7") (pinfunction "~{CAS}_F7") (pintype "bidirectional"))
      (node (ref "IC8") (pin "D3") (pinfunction "GPIO_EMC_24_D3") (pintype "bidirectional"))
    )
    (net (code "156") (name "SDRAM_CKE") (class "Default")
      (node (ref "IC3") (pin "F3") (pinfunction "CKE_F3") (pintype "bidirectional"))
      (node (ref "IC8") (pin "A2") (pinfunction "GPIO_EMC_27_A2") (pintype "bidirectional"))
    )
    (net (code "157") (name "SDRAM_CLK") (class "Default")
      (node (ref "IC3") (pin "F2") (pinfunction "CLK_F2") (pintype "bidirectional"))
      (node (ref "IC8") (pin "B3") (pinfunction "GPIO_EMC_26_B3") (pintype "bidirectional"))
    )
    (net (code "158") (name "SDRAM_CS") (class "Default")
      (node (ref "IC3") (pin "G9") (pinfunction "~{CS}_G9") (pintype "bidirectional"))
      (node (ref "IC8") (pin "E1") (pinfunction "GPIO_EMC_29_E1") (pintype "bidirectional"))
      (node (ref "R18") (pin "2") (pinfunction "2_2") (pintype "passive"))
    )
    (net (code "159") (name "SDRAM_DQ0") (class "Default")
      (node (ref "IC3") (pin "A8") (pinfunction "DQ0_A8") (pintype "bidirectional"))
      (node (ref "IC8") (pin "E3") (pinfunction "GPIO_EMC_00_E3") (pintype "bidirectional"))
    )
    (net (code "160") (name "SDRAM_DQ1") (class "Default")
      (node (ref "IC3") (pin "B9") (pinfunction "DQ1_B9") (pintype "bidirectional"))
      (node (ref "IC8") (pin "F3") (pinfunction "GPIO_EMC_01_F3") (pintype "bidirectional"))
    )
    (net (code "161") (name "SDRAM_DQ2") (class "Default")
      (node (ref "IC3") (pin "B8") (pinfunction "DQ2_B8") (pintype "bidirectional"))
      (node (ref "IC8") (pin "F4") (pinfunction "GPIO_EMC_02_F4") (pintype "bidirectional"))
    )
    (net (code "162") (name "SDRAM_DQ3") (class "Default")
      (node (ref "IC3") (pin "C9") (pinfunction "DQ3_C9") (pintype "bidirectional"))
      (node (ref "IC8") (pin "G4") (pinfunction "GPIO_EMC_03_G4") (pintype "bidirectional"))
    )
    (net (code "163") (name "SDRAM_DQ4") (class "Default")
      (node (ref "IC3") (pin "C8") (pinfunction "DQ4_C8") (pintype "bidirectional"))
      (node (ref "IC8") (pin "F2") (pinfunction "GPIO_EMC_04_F2") (pintype "bidirectional"))
    )
    (net (code "164") (name "SDRAM_DQ5") (class "Default")
      (node (ref "IC3") (pin "D9") (pinfunction "DQ5_D9") (pintype "bidirectional"))
      (node (ref "IC8") (pin "G5") (pinfunction "GPIO_EMC_05_G5") (pintype "bidirectional"))
    )
    (net (code "165") (name "SDRAM_DQ6") (class "Default")
      (node (ref "IC3") (pin "D8") (pinfunction "DQ6_D8") (pintype "bidirectional"))
      (node (ref "IC8") (pin "H5") (pinfunction "GPIO_EMC_06_H5") (pintype "bidirectional"))
    )
    (net (code "166") (name "SDRAM_DQ7") (class "Default")
      (node (ref "IC3") (pin "E9") (pinfunction "DQ7_E9") (pintype "bidirectional"))
      (node (ref "IC8") (pin "H4") (pinfunction "GPIO_EMC_07_H4") (pintype "bidirectional"))
    )
    (net (code "167") (name "SDRAM_DQ8") (class "Default")
      (node (ref "IC3") (pin "E1") (pinfunction "DQ8_E1") (pintype "bidirectional"))
      (node (ref "IC8") (pin "C6") (pinfunction "GPIO_EMC_30_C6") (pintype "bidirectional"))
    )
    (net (code "168") (name "SDRAM_DQ9") (class "Default")
      (node (ref "IC3") (pin "D2") (pinfunction "DQ9_D2") (pintype "bidirectional"))
      (node (ref "IC8") (pin "C5") (pinfunction "GPIO_EMC_31_C5") (pintype "bidirectional"))
    )
    (net (code "169") (name "SDRAM_DQ10") (class "Default")
      (node (ref "IC3") (pin "D1") (pinfunction "DQ10_D1") (pintype "bidirectional"))
      (node (ref "IC8") (pin "D5") (pinfunction "GPIO_EMC_32_D5") (pintype "bidirectional"))
    )
    (net (code "170") (name "SDRAM_DQ11") (class "Default")
      (node (ref "IC3") (pin "C2") (pinfunction "DQ11_C2") (pintype "bidirectional"))
      (node (ref "IC8") (pin "C4") (pinfunction "GPIO_EMC_33_C4") (pintype "bidirectional"))
    )
    (net (code "171") (name "SDRAM_DQ12") (class "Default")
      (node (ref "IC3") (pin "C1") (pinfunction "DQ12_C1") (pintype "bidirectional"))
      (node (ref "IC8") (pin "D4") (pinfunction "GPIO_EMC_34_D4") (pintype "bidirectional"))
    )
    (net (code "172") (name "SDRAM_DQ13") (class "Default")
      (node (ref "IC3") (pin "B2") (pinfunction "DQ13_B2") (pintype "bidirectional"))
      (node (ref "IC8") (pin "E5") (pinfunction "GPIO_EMC_35_E5") (pintype "bidirectional"))
    )
    (net (code "173") (name "SDRAM_DQ14") (class "Default")
      (node (ref "IC3") (pin "B1") (pinfunction "DQ14_B1") (pintype "bidirectional"))
      (node (ref "IC8") (pin "C3") (pinfunction "GPIO_EMC_36_C3") (pintype "bidirectional"))
    )
    (net (code "174") (name "SDRAM_DQ15") (class "Default")
      (node (ref "IC3") (pin "A2") (pinfunction "DQ15_A2") (pintype "bidirectional"))
      (node (ref "IC8") (pin "E4") (pinfunction "GPIO_EMC_37_E4") (pintype "bidirectional"))
    )
    (net (code "175") (name "SDRAM_DQMH") (class "Default")
      (node (ref "IC3") (pin "F1") (pinfunction "DQMH_F1") (pintype "bidirectional"))
      (node (ref "IC8") (pin "D6") (pinfunction "GPIO_EMC_38_D6") (pintype "bidirectional"))
    )
    (net (code "176") (name "SDRAM_DQML") (class "Default")
      (node (ref "IC3") (pin "E8") (pinfunction "DQML_E8") (pintype "bidirectional"))
      (node (ref "IC8") (pin "H3") (pinfunction "GPIO_EMC_08_H3") (pintype "bidirectional"))
    )
    (net (code "177") (name "SDRAM_RAS") (class "Default")
      (node (ref "IC3") (pin "F8") (pinfunction "~{RAS}_F8") (pintype "bidirectional"))
      (node (ref "IC8") (pin "D2") (pinfunction "GPIO_EMC_25_D2") (pintype "bidirectional"))
    )
    (net (code "178") (name "SDRAM_WE") (class "Default")
      (node (ref "IC3") (pin "F9") (pinfunction "~{WE}_F9") (pintype "bidirectional"))
      (node (ref "IC8") (pin "D1") (pinfunction "GPIO_EMC_28_D1") (pintype "bidirectional"))
    )
    (net (code "179") (name "SD_CD") (class "Default")
      (node (ref "D9") (pin "1") (pinfunction "1_1") (pintype "bidirectional"))
      (node (ref "IC8") (pin "L11") (pinfunction "GPIO_AD_B1_02_L11") (pintype "bidirectional"))
      (node (ref "J5") (pin "CD$1") (pinfunction "CD_CD$1") (pintype "power_in"))
      (node (ref "R50") (pin "1") (pinfunction "1_1") (pintype "passive"))
    )
    (net (code "180") (name "SD_CLK") (class "Default")
      (node (ref "FL3") (pin "4") (pinfunction "INPUT_4_4") (pintype "bidirectional"))
      (node (ref "IC8") (pin "J3") (pinfunction "GPIO_SD_B0_01_J3") (pintype "bidirectional"))
    )
    (net (code "181") (name "SD_CLK_INT") (class "Default")
      (node (ref "FL3") (pin "9") (pinfunction "OUTPUT_4_9") (pintype "bidirectional"))
      (node (ref "J5") (pin "P$5") (pinfunction "CLK_P$5") (pintype "bidirectional"))
    )
    (net (code "182") (name "SD_CMD") (class "Default")
      (node (ref "FL3") (pin "3") (pinfunction "INPUT_3_3") (pintype "bidirectional"))
      (node (ref "IC8") (pin "J4") (pinfunction "GPIO_SD_B0_00_J4") (pintype "bidirectional"))
      (node (ref "R53") (pin "1") (pinfunction "1_1") (pintype "passive"))
    )
    (net (code "183") (name "SD_CMD_INT") (class "Default")
      (node (ref "FL3") (pin "10") (pinfunction "OUTPUT_3_10") (pintype "bidirectional"))
      (node (ref "J5") (pin "P$3") (pinfunction "CMD_P$3") (pintype "bidirectional"))
    )
    (net (code "184") (name "SD_DAT0") (class "Default")
      (node (ref "FL3") (pin "5") (pinfunction "INPUT_5_5") (pintype "bidirectional"))
      (node (ref "IC8") (pin "J1") (pinfunction "GPIO_SD_B0_02_J1") (pintype "bidirectional"))
      (node (ref "R52") (pin "1") (pinfunction "1_1") (pintype "passive"))
    )
    (net (code "185") (name "SD_DAT0_INT") (class "Default")
      (node (ref "FL3") (pin "8") (pinfunction "OUTPUT_5_8") (pintype "bidirectional"))
      (node (ref "J5") (pin "P$7") (pinfunction "DAT0_P$7") (pintype "bidirectional"))
    )
    (net (code "186") (name "SD_DAT1") (class "Default")
      (node (ref "FL3") (pin "6") (pinfunction "INPUT_6_6") (pintype "bidirectional"))
      (node (ref "IC8") (pin "K1") (pinfunction "GPIO_SD_B0_03_K1") (pintype "bidirectional"))
      (node (ref "R51") (pin "1") (pinfunction "1_1") (pintype "passive"))
    )
    (net (code "187") (name "SD_DAT1_INT") (class "Default")
      (node (ref "FL3") (pin "7") (pinfunction "OUTPUT_6_7") (pintype "bidirectional"))
      (node (ref "J5") (pin "P$8") (pinfunction "DAT1_P$8") (pintype "bidirectional"))
    )
    (net (code "188") (name "SD_DAT2") (class "Default")
      (node (ref "FL3") (pin "1") (pinfunction "INPUT_1_1") (pintype "bidirectional"))
      (node (ref "IC8") (pin "H2") (pinfunction "GPIO_SD_B0_04_H2") (pintype "bidirectional"))
      (node (ref "R55") (pin "1") (pinfunction "1_1") (pintype "passive"))
    )
    (net (code "189") (name "SD_DAT2_INT") (class "Default")
      (node (ref "FL3") (pin "12") (pinfunction "OUTPUT_1_12") (pintype "bidirectional"))
      (node (ref "J5") (pin "P$1") (pinfunction "DAT2_P$1") (pintype "bidirectional"))
    )
    (net (code "190") (name "SD_DAT3") (class "Default")
      (node (ref "FL3") (pin "2") (pinfunction "INPUT_2_2") (pintype "bidirectional"))
      (node (ref "IC8") (pin "J2") (pinfunction "GPIO_SD_B0_05_J2") (pintype "bidirectional"))
      (node (ref "R54") (pin "1") (pinfunction "1_1") (pintype "passive"))
    )
    (net (code "191") (name "SD_DAT3_INT") (class "Default")
      (node (ref "FL3") (pin "11") (pinfunction "OUTPUT_2_11") (pintype "bidirectional"))
      (node (ref "J5") (pin "P$2") (pinfunction "DAT3/CD_P$2") (pintype "bidirectional"))
    )
    (net (code "192") (name "USB_D_N") (class "Default")
      (node (ref "FL1") (pin "6") (pinfunction "D+_2_6") (pintype "bidirectional"))
      (node (ref "IC8") (pin "M8") (pinfunction "USB_OTG1_DN_M8") (pintype "bidirectional"))
    )
    (net (code "193") (name "USB_D_P") (class "Default")
      (node (ref "FL1") (pin "7") (pinfunction "D-_2_7") (pintype "bidirectional"))
      (node (ref "IC8") (pin "L8") (pinfunction "USB_OTG1_DP_L8") (pintype "bidirectional"))
    )
    (net (code "194") (name "VBUS") (class "Default")
      (node (ref "C3") (pin "2") (pinfunction "2_2") (pintype "passive"))
      (node (ref "C88") (pin "1") (pinfunction "1_1") (pintype "passive"))
      (node (ref "C95") (pin "2") (pinfunction "2_2") (pintype "passive"))
      (node (ref "FL1") (pin "1") (pinfunction "VBUS_1") (pintype "bidirectional"))
      (node (ref "IC1") (pin "3") (pinfunction "VIN1_3") (pintype "bidirectional"))
      (node (ref "IC8") (pin "N6") (pinfunction "USB_OTG1_VBUS_N6") (pintype "bidirectional"))
      (node (ref "L1") (pin "2") (pinfunction "2_2") (pintype "passive"))
    )
    (net (code "195") (name "VCC") (class "Default")
      (node (ref "C108") (pin "2") (pinfunction "2_2") (pintype "passive"))
      (node (ref "C109") (pin "1") (pinfunction "1_1") (pintype "passive"))
      (node (ref "C11") (pin "2") (pinfunction "2_2") (pintype "passive"))
      (node (ref "C111") (pin "1") (pinfunction "1_1") (pintype "passive"))
      (node (ref "C12") (pin "1") (pinfunction "1_1") (pintype "passive"))
      (node (ref "C13") (pin "1") (pinfunction "1_1") (pintype "passive"))
      (node (ref "C14") (pin "1") (pinfunction "1_1") (pintype "passive"))
      (node (ref "C15") (pin "1") (pinfunction "1_1") (pintype "passive"))
      (node (ref "C16") (pin "1") (pinfunction "1_1") (pintype "passive"))
      (node (ref "C17") (pin "2") (pinfunction "2_2") (pintype "passive"))
      (node (ref "C18") (pin "2") (pinfunction "2_2") (pintype "passive"))
      (node (ref "C19") (pin "1") (pinfunction "1_1") (pintype "passive"))
      (node (ref "C20") (pin "1") (pinfunction "1_1") (pintype "passive"))
      (node (ref "C21") (pin "2") (pinfunction "2_2") (pintype "passive"))
      (node (ref "C22") (pin "1") (pinfunction "1_1") (pintype "passive"))
      (node (ref "C23") (pin "2") (pinfunction "2_2") (pintype "passive"))
      (node (ref "C26") (pin "1") (pinfunction "1_1") (pintype "passive"))
      (node (ref "C27") (pin "2") (pinfunction "2_2") (pintype "passive"))
      (node (ref "C28") (pin "1") (pinfunction "1_1") (pintype "passive"))
      (node (ref "C29") (pin "1") (pinfunction "1_1") (pintype "passive"))
      (node (ref "C30") (pin "1") (pinfunction "1_1") (pintype "passive"))
      (node (ref "C31") (pin "2") (pinfunction "2_2") (pintype "passive"))
      (node (ref "C32") (pin "1") (pinfunction "1_1") (pintype "passive"))
      (node (ref "C33") (pin "2") (pinfunction "2_2") (pintype "passive"))
      (node (ref "C35") (pin "2") (pinfunction "2_2") (pintype "passive"))
      (node (ref "C36") (pin "1") (pinfunction "1_1") (pintype "passive"))
      (node (ref "C37") (pin "1") (pinfunction "1_1") (pintype "passive"))
      (node (ref "C39") (pin "2") (pinfunction "2_2") (pintype "passive"))
      (node (ref "C40") (pin "2") (pinfunction "2_2") (pintype "passive"))
      (node (ref "C41") (pin "2") (pinfunction "2_2") (pintype "passive"))
      (node (ref "C42") (pin "2") (pinfunction "2_2") (pintype "passive"))
      (node (ref "C43") (pin "1") (pinfunction "1_1") (pintype "passive"))
      (node (ref "C44") (pin "2") (pinfunction "2_2") (pintype "passive"))
      (node (ref "C50") (pin "1") (pinfunction "1_1") (pintype "passive"))
      (node (ref "C53") (pin "1") (pinfunction "1_1") (pintype "passive"))
      (node (ref "C54") (pin "1") (pinfunction "1_1") (pintype "passive"))
      (node (ref "C55") (pin "1") (pinfunction "1_1") (pintype "passive"))
      (node (ref "C56") (pin "1") (pinfunction "1_1") (pintype "passive"))
      (node (ref "C57") (pin "2") (pinfunction "2_2") (pintype "passive"))
      (node (ref "C58") (pin "2") (pinfunction "2_2") (pintype "passive"))
      (node (ref "C64") (pin "1") (pinfunction "1_1") (pintype "passive"))
      (node (ref "C66") (pin "2") (pinfunction "2_2") (pintype "passive"))
      (node (ref "C67") (pin "1") (pinfunction "1_1") (pintype "passive"))
      (node (ref "C68") (pin "2") (pinfunction "2_2") (pintype "passive"))
      (node (ref "C7") (pin "1") (pinfunction "1_1") (pintype "passive"))
      (node (ref "C75") (pin "1") (pinfunction "1_1") (pintype "passive"))
      (node (ref "C76") (pin "1") (pinfunction "1_1") (pintype "passive"))
      (node (ref "C86") (pin "2") (pinfunction "2_2") (pintype "passive"))
      (node (ref "C89") (pin "1") (pinfunction "1_1") (pintype "passive"))
      (node (ref "C90") (pin "2") (pinfunction "2_2") (pintype "passive"))
      (node (ref "C92") (pin "2") (pinfunction "2_2") (pintype "passive"))
      (node (ref "C93") (pin "2") (pinfunction "2_2") (pintype "passive"))
      (node (ref "C96") (pin "1") (pinfunction "1_1") (pintype "passive"))
      (node (ref "C99") (pin "2") (pinfunction "2_2") (pintype "passive"))
      (node (ref "D10") (pin "1") (pinfunction "1_1") (pintype "bidirectional"))
      (node (ref "D3") (pin "4") (pinfunction "ANODE_4") (pintype "passive"))
      (node (ref "D4") (pin "1") (pinfunction "1_1") (pintype "bidirectional"))
      (node (ref "D6") (pin "1") (pinfunction "1_1") (pintype "bidirectional"))
      (node (ref "IC2") (pin "6") (pinfunction "OUT_6") (pintype "bidirectional"))
      (node (ref "IC3") (pin "A7") (pinfunction "VDDQ_1_A7") (pintype "bidirectional"))
      (node (ref "IC3") (pin "A9") (pinfunction "VDD_1_A9") (pintype "bidirectional"))
      (node (ref "IC3") (pin "B3") (pinfunction "VDDQ_2_B3") (pintype "bidirectional"))
      (node (ref "IC3") (pin "C7") (pinfunction "VDDQ_3_C7") (pintype "bidirectional"))
      (node (ref "IC3") (pin "D3") (pinfunction "VDDQ_4_D3") (pintype "bidirectional"))
      (node (ref "IC3") (pin "E7") (pinfunction "VDD_2_E7") (pintype "bidirectional"))
      (node (ref "IC3") (pin "J9") (pinfunction "VDD_3_J9") (pintype "bidirectional"))
      (node (ref "IC4") (pin "8") (pinfunction "VCC_8") (pintype "bidirectional"))
      (node (ref "IC5") (pin "8") (pinfunction "VCC_8") (pintype "bidirectional"))
      (node (ref "IC7") (pin "6") (pinfunction "VDD_6") (pintype "bidirectional"))
      (node (ref "IC8") (pin "E6") (pinfunction "NVCC_EMC_1_E6") (pintype "bidirectional"))
      (node (ref "IC8") (pin "E9") (pinfunction "NVCC_GPIO_1_E9") (pintype "bidirectional"))
      (node (ref "IC8") (pin "F10") (pinfunction "NVCC_GPIO_2_F10") (pintype "bidirectional"))
      (node (ref "IC8") (pin "F5") (pinfunction "NVCC_EMC_2_F5") (pintype "bidirectional"))
      (node (ref "IC8") (pin "J10") (pinfunction "NVCC_GPIO_3_J10") (pintype "bidirectional"))
      (node (ref "IC8") (pin "J6") (pinfunction "NVCC_SD0_J6") (pintype "bidirectional"))
      (node (ref "IC8") (pin "K4") (pinfunction "DCDC_IN_Q_K4") (pintype "bidirectional"))
      (node (ref "IC8") (pin "K5") (pinfunction "NVCC_SD1_K5") (pintype "bidirectional"))
      (node (ref "IC8") (pin "L1") (pinfunction "DCDC_IN_1_L1") (pintype "bidirectional"))
      (node (ref "IC8") (pin "L2") (pinfunction "DCDC_IN_2_L2") (pintype "bidirectional"))
      (node (ref "IC8") (pin "P12") (pinfunction "VDD_HIGH_IN_P12") (pintype "bidirectional"))
      (node (ref "IC9") (pin "14") (pinfunction "VDDIO_14") (pintype "bidirectional"))
      (node (ref "J2") (pin "1") (pinfunction "1_1") (pintype "passive"))
      (node (ref "J4") (pin "10") (pinfunction "10_10") (pintype "bidirectional"))
      (node (ref "J4") (pin "2") (pinfunction "2_2") (pintype "bidirectional"))
      (node (ref "J4") (pin "20") (pinfunction "20_20") (pintype "bidirectional"))
      (node (ref "J4") (pin "30") (pinfunction "30_30") (pintype "bidirectional"))
      (node (ref "J4") (pin "36") (pinfunction "36_36") (pintype "bidirectional"))
      (node (ref "J5") (pin "P$4") (pinfunction "VDD_P$4") (pintype "power_in"))
      (node (ref "J8") (pin "1") (pinfunction "1_1") (pintype "passive"))
      (node (ref "L2") (pin "2") (pinfunction "2_2") (pintype "passive"))
      (node (ref "L4") (pin "2") (pinfunction "2_2") (pintype "passive"))
      (node (ref "L6") (pin "2") (pinfunction "2_2") (pintype "passive"))
      (node (ref "L8") (pin "2") (pinfunction "2_2") (pintype "passive"))
      (node (ref "Q4") (pin "1") (pinfunction "G_1") (pintype "bidirectional"))
      (node (ref "Q5") (pin "1") (pinfunction "G_1") (pintype "bidirectional"))
      (node (ref "Q7") (pin "1") (pinfunction "G_1") (pintype "bidirectional"))
      (node (ref "R13") (pin "1") (pinfunction "1_1") (pintype "passive"))
      (node (ref "R15") (pin "2") (pinfunction "2_2") (pintype "passive"))
      (node (ref "R16") (pin "2") (pinfunction "2_2") (pintype "passive"))
      (node (ref "R17") (pin "2") (pinfunction "2_2") (pintype "passive"))
      (node (ref "R18") (pin "1") (pinfunction "1_1") (pintype "passive"))
      (node (ref "R2") (pin "2") (pinfunction "2_2") (pintype "passive"))
      (node (ref "R24") (pin "2") (pinfunction "2_2") (pintype "passive"))
      (node (ref "R25") (pin "2") (pinfunction "2_2") (pintype "passive"))
      (node (ref "R26") (pin "2") (pinfunction "2_2") (pintype "passive"))
      (node (ref "R28") (pin "2") (pinfunction "2_2") (pintype "passive"))
      (node (ref "R29") (pin "2") (pinfunction "2_2") (pintype "passive"))
      (node (ref "R30") (pin "2") (pinfunction "2_2") (pintype "passive"))
      (node (ref "R31") (pin "2") (pinfunction "2_2") (pintype "passive"))
      (node (ref "R32") (pin "2") (pinfunction "2_2") (pintype "passive"))
      (node (ref "R33") (pin "1") (pinfunction "1_1") (pintype "passive"))
      (node (ref "R34") (pin "2") (pinfunction "2_2") (pintype "passive"))
      (node (ref "R36") (pin "2") (pinfunction "2_2") (pintype "passive"))
      (node (ref "R39") (pin "2") (pinfunction "2_2") (pintype "passive"))
      (node (ref "R42") (pin "1") (pinfunction "1_1") (pintype "passive"))
      (node (ref "R43") (pin "2") (pinfunction "2_2") (pintype "passive"))
      (node (ref "R44") (pin "2") (pinfunction "2_2") (pintype "passive"))
      (node (ref "R45") (pin "2") (pinfunction "2_2") (pintype "passive"))
      (node (ref "R46") (pin "2") (pinfunction "2_2") (pintype "passive"))
      (node (ref "R47") (pin "2") (pinfunction "2_2") (pintype "passive"))
      (node (ref "R48") (pin "2") (pinfunction "2_2") (pintype "passive"))
      (node (ref "R49") (pin "2") (pinfunction "2_2") (pintype "passive"))
      (node (ref "R50") (pin "2") (pinfunction "2_2") (pintype "passive"))
      (node (ref "R51") (pin "2") (pinfunction "2_2") (pintype "passive"))
      (node (ref "R52") (pin "2") (pinfunction "2_2") (pintype "passive"))
      (node (ref "R53") (pin "2") (pinfunction "2_2") (pintype "passive"))
      (node (ref "R54") (pin "2") (pinfunction "2_2") (pintype "passive"))
      (node (ref "R55") (pin "2") (pinfunction "2_2") (pintype "passive"))
      (node (ref "R56") (pin "2") (pinfunction "2_2") (pintype "passive"))
      (node (ref "R57") (pin "2") (pinfunction "2_2") (pintype "passive"))
      (node (ref "R58") (pin "2") (pinfunction "2_2") (pintype "passive"))
      (node (ref "R59") (pin "2") (pinfunction "2_2") (pintype "passive"))
      (node (ref "U3") (pin "30") (pinfunction "VBAT_30") (pintype "power_in"))
      (node (ref "U3") (pin "36") (pinfunction "VIO_36") (pintype "power_in"))
      (node (ref "Y3") (pin "1") (pinfunction "TRI-STATE_1") (pintype "bidirectional"))
      (node (ref "Y3") (pin "4") (pinfunction "VDD_4") (pintype "bidirectional"))
    )
    (net (code "196") (name "VCC_SOC") (class "Default")
      (node (ref "C100") (pin "2") (pinfunction "2_2") (pintype "passive"))
      (node (ref "C103") (pin "2") (pinfunction "2_2") (pintype "passive"))
      (node (ref "C34") (pin "1") (pinfunction "1_1") (pintype "passive"))
      (node (ref "C38") (pin "1") (pinfunction "1_1") (pintype "passive"))
      (node (ref "C45") (pin "1") (pinfunction "1_1") (pintype "passive"))
      (node (ref "C46") (pin "2") (pinfunction "2_2") (pintype "passive"))
      (node (ref "C47") (pin "1") (pinfunction "1_1") (pintype "passive"))
      (node (ref "C48") (pin "1") (pinfunction "1_1") (pintype "passive"))
      (node (ref "C49") (pin "2") (pinfunction "2_2") (pintype "passive"))
      (node (ref "C87") (pin "2") (pinfunction "2_2") (pintype "passive"))
      (node (ref "C94") (pin "2") (pinfunction "2_2") (pintype "passive"))
      (node (ref "C97") (pin "2") (pinfunction "2_2") (pintype "passive"))
      (node (ref "C98") (pin "2") (pinfunction "2_2") (pintype "passive"))
      (node (ref "IC8") (pin "F6") (pinfunction "VDD_SOC_IN_1_F6") (pintype "bidirectional"))
      (node (ref "IC8") (pin "F7") (pinfunction "VDD_SOC_IN_2_F7") (pintype "bidirectional"))
      (node (ref "IC8") (pin "F8") (pinfunction "VDD_SOC_IN_3_F8") (pintype "bidirectional"))
      (node (ref "IC8") (pin "F9") (pinfunction "VDD_SOC_IN_4_F9") (pintype "bidirectional"))
      (node (ref "IC8") (pin "G6") (pinfunction "VDD_SOC_IN_5_G6") (pintype "bidirectional"))
      (node (ref "IC8") (pin "G9") (pinfunction "VDD_SOC_IN_6_G9") (pintype "bidirectional"))
      (node (ref "IC8") (pin "H6") (pinfunction "VDD_SOC_IN_7_H6") (pintype "bidirectional"))
      (node (ref "IC8") (pin "H9") (pinfunction "VDD_SOC_IN_8_H9") (pintype "bidirectional"))
      (node (ref "IC8") (pin "J5") (pinfunction "DCDC_SENSE_J5") (pintype "bidirectional"))
      (node (ref "IC8") (pin "J9") (pinfunction "VDD_SOC_IN_9_J9") (pintype "bidirectional"))
      (node (ref "L5") (pin "1") (pinfunction "1_1") (pintype "passive"))
    )
    (net (code "197") (name "VDDA") (class "Default")
      (node (ref "C51") (pin "1") (pinfunction "1_1") (pintype "passive"))
      (node (ref "C52") (pin "2") (pinfunction "2_2") (pintype "passive"))
      (node (ref "J4") (pin "4") (pinfunction "4_4") (pintype "bidirectional"))
      (node (ref "L4") (pin "1") (pinfunction "1_1") (pintype "passive"))
    )
    (net (code "198") (name "VDDA_ADC_3P3") (class "Default")
      (node (ref "C59") (pin "1") (pinfunction "1_1") (pintype "passive"))
      (node (ref "C60") (pin "2") (pinfunction "2_2") (pintype "passive"))
      (node (ref "C61") (pin "2") (pinfunction "2_2") (pintype "passive"))
      (node (ref "IC8") (pin "N14") (pinfunction "VDDA_ADC_3P3_N14") (pintype "bidirectional"))
      (node (ref "L6") (pin "1") (pinfunction "1_1") (pintype "passive"))
    )
    (net (code "199") (name "VDD_HIGH_CAP") (class "Default")
      (node (ref "C101") (pin "2") (pinfunction "2_2") (pintype "passive"))
      (node (ref "C102") (pin "1") (pinfunction "1_1") (pintype "passive"))
      (node (ref "IC8") (pin "P8") (pinfunction "VDD_HIGH_CAP_P8") (pintype "bidirectional"))
    )
    (net (code "200") (name "VDD_SNVS") (class "Default")
      (node (ref "C2") (pin "2") (pinfunction "2_2") (pintype "passive"))
      (node (ref "C69") (pin "1") (pinfunction "1_1") (pintype "passive"))
      (node (ref "IC10") (pin "5") (pinfunction "VOUT_5") (pintype "bidirectional"))
      (node (ref "IC8") (pin "M9") (pinfunction "VDD_SNVS_IN_M9") (pintype "bidirectional"))
      (node (ref "Q1") (pin "1") (pinfunction "G_1") (pintype "bidirectional"))
      (node (ref "Q2") (pin "1") (pinfunction "G_1") (pintype "bidirectional"))
      (node (ref "Q3") (pin "1") (pinfunction "G_1") (pintype "bidirectional"))
    )
    (net (code "201") (name "VDD_SNVS_CAP") (class "Default")
      (node (ref "C70") (pin "1") (pinfunction "1_1") (pintype "passive"))
      (node (ref "IC8") (pin "M10") (pinfunction "VDD_SNVS_CAP_M10") (pintype "bidirectional"))
    )
    (net (code "202") (name "VDD_USB_CAP") (class "Default")
      (node (ref "C71") (pin "1") (pinfunction "1_1") (pintype "passive"))
      (node (ref "C72") (pin "2") (pinfunction "2_2") (pintype "passive"))
      (node (ref "C73") (pin "2") (pinfunction "2_2") (pintype "passive"))
      (node (ref "IC8") (pin "K8") (pinfunction "VDD_USB_CAP_K8") (pintype "bidirectional"))
    )
    (net (code "203") (name "VIN") (class "Default")
      (node (ref "D7") (pin "1") (pinfunction "1_1") (pintype "bidirectional"))
      (node (ref "J6") (pin "2") (pinfunction "2_2") (pintype "passive"))
      (node (ref "Q6") (pin "3") (pinfunction "D_3") (pintype "bidirectional"))
    )
    (net (code "204") (name "V_BATT") (class "Default")
      (node (ref "C4") (pin "2") (pinfunction "2_2") (pintype "passive"))
      (node (ref "C9") (pin "2") (pinfunction "2_2") (pintype "passive"))
      (node (ref "D1") (pin "4") (pinfunction "ANODE_4") (pintype "passive"))
      (node (ref "IC1") (pin "2") (pinfunction "VOUT_1_2") (pintype "bidirectional"))
      (node (ref "IC1") (pin "7") (pinfunction "VOUT_2_7") (pintype "bidirectional"))
      (node (ref "U2") (pin "13") (pinfunction "IN_13") (pintype "input"))
    )
    (net (code "205") (name "WAKEUP") (class "Default")
      (node (ref "IC8") (pin "L6") (pinfunction "WAKEUP_L6") (pintype "bidirectional"))
      (node (ref "Q2") (pin "2") (pinfunction "S_2") (pintype "bidirectional"))
    )
    (net (code "206") (name "WIFI_CLK") (class "Default")
      (node (ref "IC8") (pin "M13") (pinfunction "GPIO_AD_B1_09_M13") (pintype "bidirectional"))
      (node (ref "U3") (pin "20") (pinfunction "SDIO_CLK_20") (pintype "input"))
    )
    (net (code "207") (name "WIFI_CMD") (class "Default")
      (node (ref "IC8") (pin "H13") (pinfunction "GPIO_AD_B1_08_H13") (pintype "bidirectional"))
      (node (ref "R49") (pin "1") (pinfunction "1_1") (pintype "passive"))
      (node (ref "U3") (pin "22") (pinfunction "SDIO_CMD_22") (pintype "bidirectional"))
    )
    (net (code "208") (name "WIFI_D0") (class "Default")
      (node (ref "IC8") (pin "M4") (pinfunction "GPIO_SD_B1_03_M4") (pintype "bidirectional"))
      (node (ref "R48") (pin "1") (pinfunction "1_1") (pintype "passive"))
      (node (ref "U3") (pin "24") (pinfunction "SDIO_DATA_0_24") (pintype "bidirectional"))
    )
    (net (code "209") (name "WIFI_D1") (class "Default")
      (node (ref "IC8") (pin "M3") (pinfunction "GPIO_SD_B1_02_M3") (pintype "bidirectional"))
      (node (ref "R47") (pin "1") (pinfunction "1_1") (pintype "passive"))
      (node (ref "U3") (pin "26") (pinfunction "SDIO_DATA_1_26") (pintype "bidirectional"))
    )
    (net (code "210") (name "WIFI_D2") (class "Default")
      (node (ref "IC8") (pin "J12") (pinfunction "GPIO_AD_B1_06_J12") (pintype "bidirectional"))
      (node (ref "R46") (pin "1") (pinfunction "1_1") (pintype "passive"))
      (node (ref "U3") (pin "23") (pinfunction "SDIO_DATA_2_23") (pintype "bidirectional"))
    )
    (net (code "211") (name "WIFI_D3") (class "Default")
      (node (ref "IC8") (pin "K10") (pinfunction "GPIO_AD_B1_07_K10") (pintype "bidirectional"))
      (node (ref "R45") (pin "1") (pinfunction "1_1") (pintype "passive"))
      (node (ref "U3") (pin "25") (pinfunction "SDIO_DATA_3_25") (pintype "bidirectional"))
    )
    (net (code "212") (name "WL_H_WAKE") (class "Default")
      (node (ref "IC8") (pin "E11") (pinfunction "GPIO_B0_15_E11") (pintype "bidirectional"))
      (node (ref "R43") (pin "1") (pinfunction "1_1") (pintype "passive"))
      (node (ref "U3") (pin "27") (pinfunction "WL_GPIO_0_HOST_WAKE_27") (pintype "bidirectional"))
    )
    (net (code "213") (name "WL_REG_ON") (class "Default")
      (node (ref "IC8") (pin "E10") (pinfunction "GPIO_B0_14_E10") (pintype "bidirectional"))
      (node (ref "U3") (pin "28") (pinfunction "WL_REG_ON_28") (pintype "input"))
    )
    (net (code "214") (name "XTALI") (class "Default")
      (node (ref "C106") (pin "1") (pinfunction "1_1") (pintype "passive"))
      (node (ref "IC8") (pin "P11") (pinfunction "XTALI_P11") (pintype "bidirectional"))
      (node (ref "R40") (pin "1") (pinfunction "1_1") (pintype "passive"))
      (node (ref "Y2") (pin "3") (pinfunction "CRYSTAL_2_3") (pintype "bidirectional"))
    )
    (net (code "215") (name "XTALO") (class "Default")
      (node (ref "C105") (pin "1") (pinfunction "1_1") (pintype "passive"))
      (node (ref "IC8") (pin "N11") (pinfunction "XTALO_N11") (pintype "bidirectional"))
      (node (ref "Y2") (pin "1") (pinfunction "CRYSTAL_1_1") (pintype "bidirectional"))
    )
    (net (code "216") (name "unconnected-(ANT1-NC-Pad2)") (class "Default")
      (node (ref "ANT1") (pin "2") (pinfunction "NC_2") (pintype "no_connect"))
    )
    (net (code "217") (name "unconnected-(FL1-Pad9)") (class "Default")
      (node (ref "FL1") (pin "9") (pinfunction "9_9") (pintype "bidirectional"))
    )
    (net (code "218") (name "unconnected-(FL1-Pad10)") (class "Default")
      (node (ref "FL1") (pin "10") (pinfunction "10_10") (pintype "bidirectional"))
    )
    (net (code "219") (name "unconnected-(FL1-Pad11)") (class "Default")
      (node (ref "FL1") (pin "11") (pinfunction "11_11") (pintype "bidirectional"))
    )
    (net (code "220") (name "unconnected-(FL1-Pad12)") (class "Default")
      (node (ref "FL1") (pin "12") (pinfunction "12_12") (pintype "bidirectional"))
    )
    (net (code "221") (name "unconnected-(H1-MOUNT-PadB2,8)") (class "Default")
      (node (ref "H1") (pin "B2,8") (pinfunction "MOUNT_B2,8") (pintype "passive"))
    )
    (net (code "222") (name "unconnected-(H2-MOUNT-PadB2,8)") (class "Default")
      (node (ref "H2") (pin "B2,8") (pinfunction "MOUNT_B2,8") (pintype "passive"))
    )
    (net (code "223") (name "unconnected-(IC3-NC-PadE2)") (class "Default")
      (node (ref "IC3") (pin "E2") (pinfunction "NC_E2") (pintype "no_connect"))
    )
    (net (code "224") (name "unconnected-(IC4-NC_1-Pad1)") (class "Default")
      (node (ref "IC4") (pin "1") (pinfunction "NC_1_1") (pintype "bidirectional"))
    )
    (net (code "225") (name "unconnected-(IC4-NC_2-Pad2)") (class "Default")
      (node (ref "IC4") (pin "2") (pinfunction "NC_2_2") (pintype "bidirectional"))
    )
    (net (code "226") (name "unconnected-(IC4-NC_3-Pad3)") (class "Default")
      (node (ref "IC4") (pin "3") (pinfunction "NC_3_3") (pintype "bidirectional"))
    )
    (net (code "227") (name "unconnected-(IC4-NC_4-Pad7)") (class "Default")
      (node (ref "IC4") (pin "7") (pinfunction "NC_4_7") (pintype "bidirectional"))
    )
    (net (code "228") (name "unconnected-(IC7-NC-Pad2)") (class "Default")
      (node (ref "IC7") (pin "2") (pinfunction "NC_2") (pintype "no_connect"))
    )
    (net (code "229") (name "unconnected-(IC8-CCM_CLK1_N-PadP13)") (class "Default")
      (node (ref "IC8") (pin "P13") (pinfunction "CCM_CLK1_N_P13") (pintype "bidirectional"))
    )
    (net (code "230") (name "unconnected-(IC8-CCM_CLK1_P-PadN13)") (class "Default")
      (node (ref "IC8") (pin "N13") (pinfunction "CCM_CLK1_P_N13") (pintype "bidirectional"))
    )
    (net (code "231") (name "unconnected-(IC8-GPANAIO-PadN10)") (class "Default")
      (node (ref "IC8") (pin "N10") (pinfunction "GPANAIO_N10") (pintype "bidirectional"))
    )
    (net (code "232") (name "unconnected-(IC8-GPIO_EMC_39-PadB7)") (class "Default")
      (node (ref "IC8") (pin "B7") (pinfunction "GPIO_EMC_39_B7") (pintype "bidirectional"))
    )
    (net (code "233") (name "unconnected-(IC8-GPIO_SD_B1_05-PadN3)") (class "Default")
      (node (ref "IC8") (pin "N3") (pinfunction "GPIO_SD_B1_05_N3") (pintype "bidirectional"))
    )
    (net (code "234") (name "unconnected-(IC8-PMIC_STBY_REQ-PadL7)") (class "Default")
      (node (ref "IC8") (pin "L7") (pinfunction "PMIC_STBY_REQ_L7") (pintype "bidirectional"))
    )
    (net (code "235") (name "unconnected-(IC8-USB_OTG1_CHD_B-PadN12)") (class "Default")
      (node (ref "IC8") (pin "N12") (pinfunction "USB_OTG1_CHD_B_N12") (pintype "bidirectional"))
    )
    (net (code "236") (name "unconnected-(IC8-USB_OTG2_DN-PadN7)") (class "Default")
      (node (ref "IC8") (pin "N7") (pinfunction "USB_OTG2_DN_N7") (pintype "bidirectional"))
    )
    (net (code "237") (name "unconnected-(IC8-USB_OTG2_DP-PadP7)") (class "Default")
      (node (ref "IC8") (pin "P7") (pinfunction "USB_OTG2_DP_P7") (pintype "bidirectional"))
    )
    (net (code "238") (name "unconnected-(IC8-USB_OTG2_VBUS-PadP6)") (class "Default")
      (node (ref "IC8") (pin "P6") (pinfunction "USB_OTG2_VBUS_P6") (pintype "bidirectional"))
    )
    (net (code "239") (name "unconnected-(IC9-REF_CLK-Pad16)") (class "Default")
      (node (ref "IC9") (pin "16") (pinfunction "REF_CLK_16") (pintype "bidirectional"))
    )
    (net (code "240") (name "unconnected-(IC9-XO-Pad7)") (class "Default")
      (node (ref "IC9") (pin "7") (pinfunction "XO_7") (pintype "bidirectional"))
    )
    (net (code "241") (name "unconnected-(IC10-NC-Pad4)") (class "Default")
      (node (ref "IC10") (pin "4") (pinfunction "NC_4") (pintype "no_connect"))
    )
    (net (code "242") (name "unconnected-(J1-SBU1-PadA8)") (class "Default")
      (node (ref "J1") (pin "A8") (pinfunction "SBU1_A8") (pintype "bidirectional"))
    )
    (net (code "243") (name "unconnected-(J1-SBU2-PadB8)") (class "Default")
      (node (ref "J1") (pin "B8") (pinfunction "SBU2_B8") (pintype "bidirectional"))
    )
    (net (code "244") (name "unconnected-(J4-Pad1)") (class "Default")
      (node (ref "J4") (pin "1") (pinfunction "1_1") (pintype "bidirectional"))
    )
    (net (code "245") (name "unconnected-(J4-Pad3)") (class "Default")
      (node (ref "J4") (pin "3") (pinfunction "3_3") (pintype "bidirectional"))
    )
    (net (code "246") (name "unconnected-(J4-Pad6)") (class "Default")
      (node (ref "J4") (pin "6") (pinfunction "6_6") (pintype "bidirectional"))
    )
    (net (code "247") (name "unconnected-(J4-Pad7)") (class "Default")
      (node (ref "J4") (pin "7") (pinfunction "7_7") (pintype "bidirectional"))
    )
    (net (code "248") (name "unconnected-(J4-Pad8)") (class "Default")
      (node (ref "J4") (pin "8") (pinfunction "8_8") (pintype "bidirectional"))
    )
    (net (code "249") (name "unconnected-(J4-Pad9)") (class "Default")
      (node (ref "J4") (pin "9") (pinfunction "9_9") (pintype "bidirectional"))
    )
    (net (code "250") (name "unconnected-(J8-Pad7)") (class "Default")
      (node (ref "J8") (pin "7") (pinfunction "7_7") (pintype "passive"))
    )
    (net (code "251") (name "unconnected-(U3-BT_GPIO_3-Pad6)") (class "Default")
      (node (ref "U3") (pin "6") (pinfunction "BT_GPIO_3_6") (pintype "bidirectional"))
    )
    (net (code "252") (name "unconnected-(U3-BT_GPIO_4-Pad7)") (class "Default")
      (node (ref "U3") (pin "7") (pinfunction "BT_GPIO_4_7") (pintype "bidirectional"))
    )
    (net (code "253") (name "unconnected-(U3-BT_GPIO_5-Pad13)") (class "Default")
      (node (ref "U3") (pin "13") (pinfunction "BT_GPIO_5_13") (pintype "bidirectional"))
    )
    (net (code "254") (name "unconnected-(U3-BT_I2S_DO-Pad16)") (class "Default")
      (node (ref "U3") (pin "16") (pinfunction "BT_I2S_DO_16") (pintype "bidirectional"))
    )
    (net (code "255") (name "unconnected-(U3-BT_PCM_CLK-Pad11)") (class "Default")
      (node (ref "U3") (pin "11") (pinfunction "BT_PCM_CLK_11") (pintype "bidirectional"))
    )
    (net (code "256") (name "unconnected-(U3-BT_PCM_IN-Pad9)") (class "Default")
      (node (ref "U3") (pin "9") (pinfunction "BT_PCM_IN_9") (pintype "input"))
    )
    (net (code "257") (name "unconnected-(U3-BT_PCM_OUT-Pad10)") (class "Default")
      (node (ref "U3") (pin "10") (pinfunction "BT_PCM_OUT_10") (pintype "output"))
    )
    (net (code "258") (name "unconnected-(U3-BT_PCM_SYNC-Pad8)") (class "Default")
      (node (ref "U3") (pin "8") (pinfunction "BT_PCM_SYNC_8") (pintype "bidirectional"))
    )
    (net (code "259") (name "unconnected-(U3-WL_GPIO_1-Pad18)") (class "Default")
      (node (ref "U3") (pin "18") (pinfunction "WL_GPIO_1_18") (pintype "bidirectional"))
    )
    (net (code "260") (name "unconnected-(U3-WL_GPIO_2-Pad17)") (class "Default")
      (node (ref "U3") (pin "17") (pinfunction "WL_GPIO_2_17") (pintype "bidirectional"))
    )
    (net (code "261") (name "unconnected-(U3-WL_GPIO_4-Pad15)") (class "Default")
      (node (ref "U3") (pin "15") (pinfunction "WL_GPIO_4_15") (pintype "bidirectional"))
    )
  )
)
